# SPI_Test.net
KiCad netlist of a schematic drawn in EAGLE
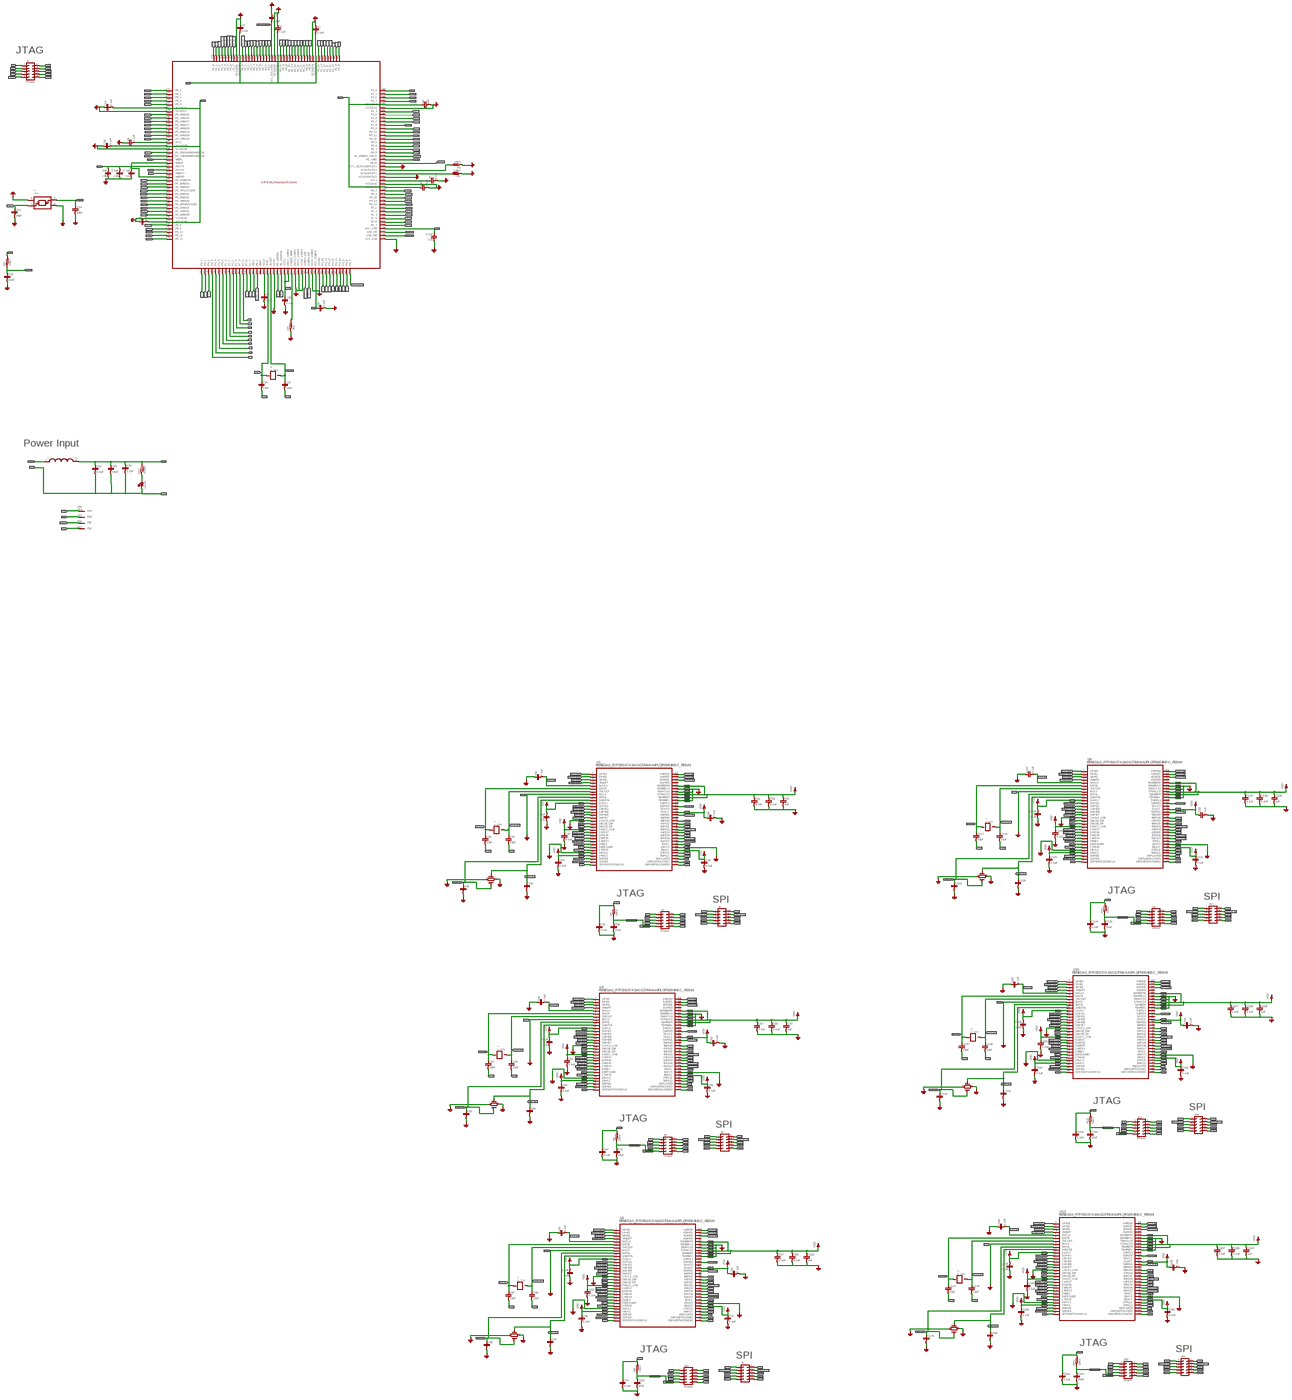
[diagram p0: schematic, sheet 1, overview]
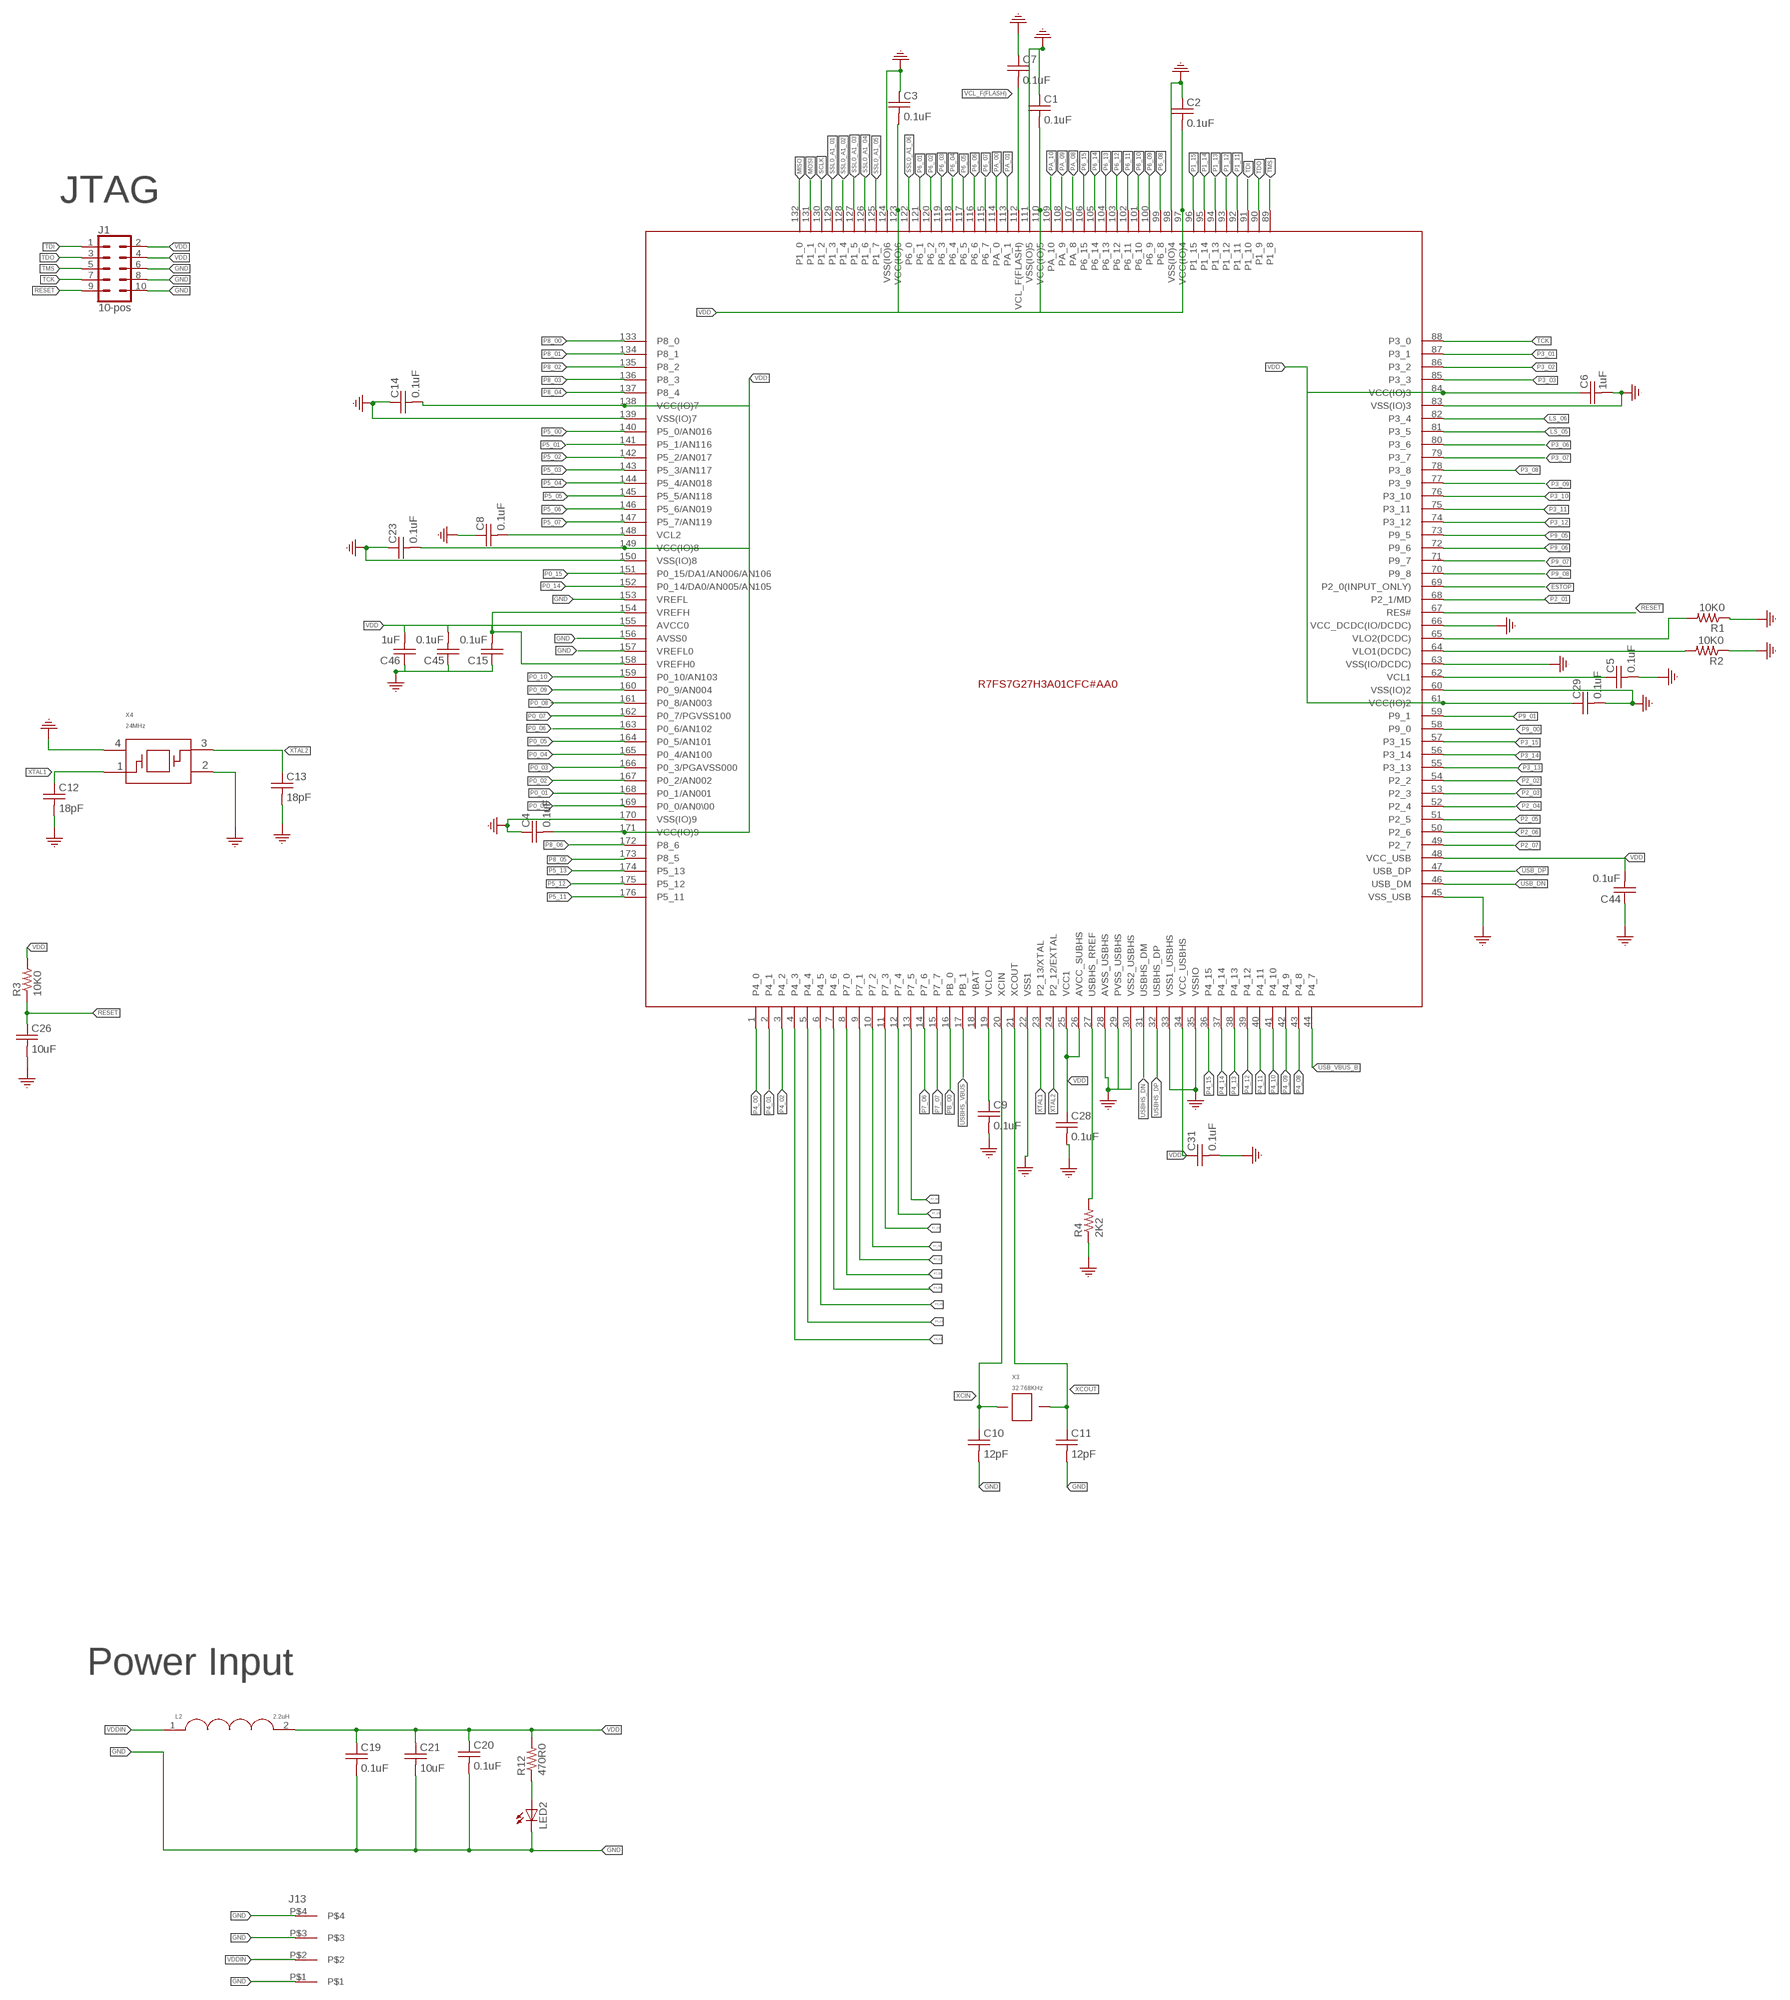
[diagram p1: schematic, sheet 1, part 1 of 5]
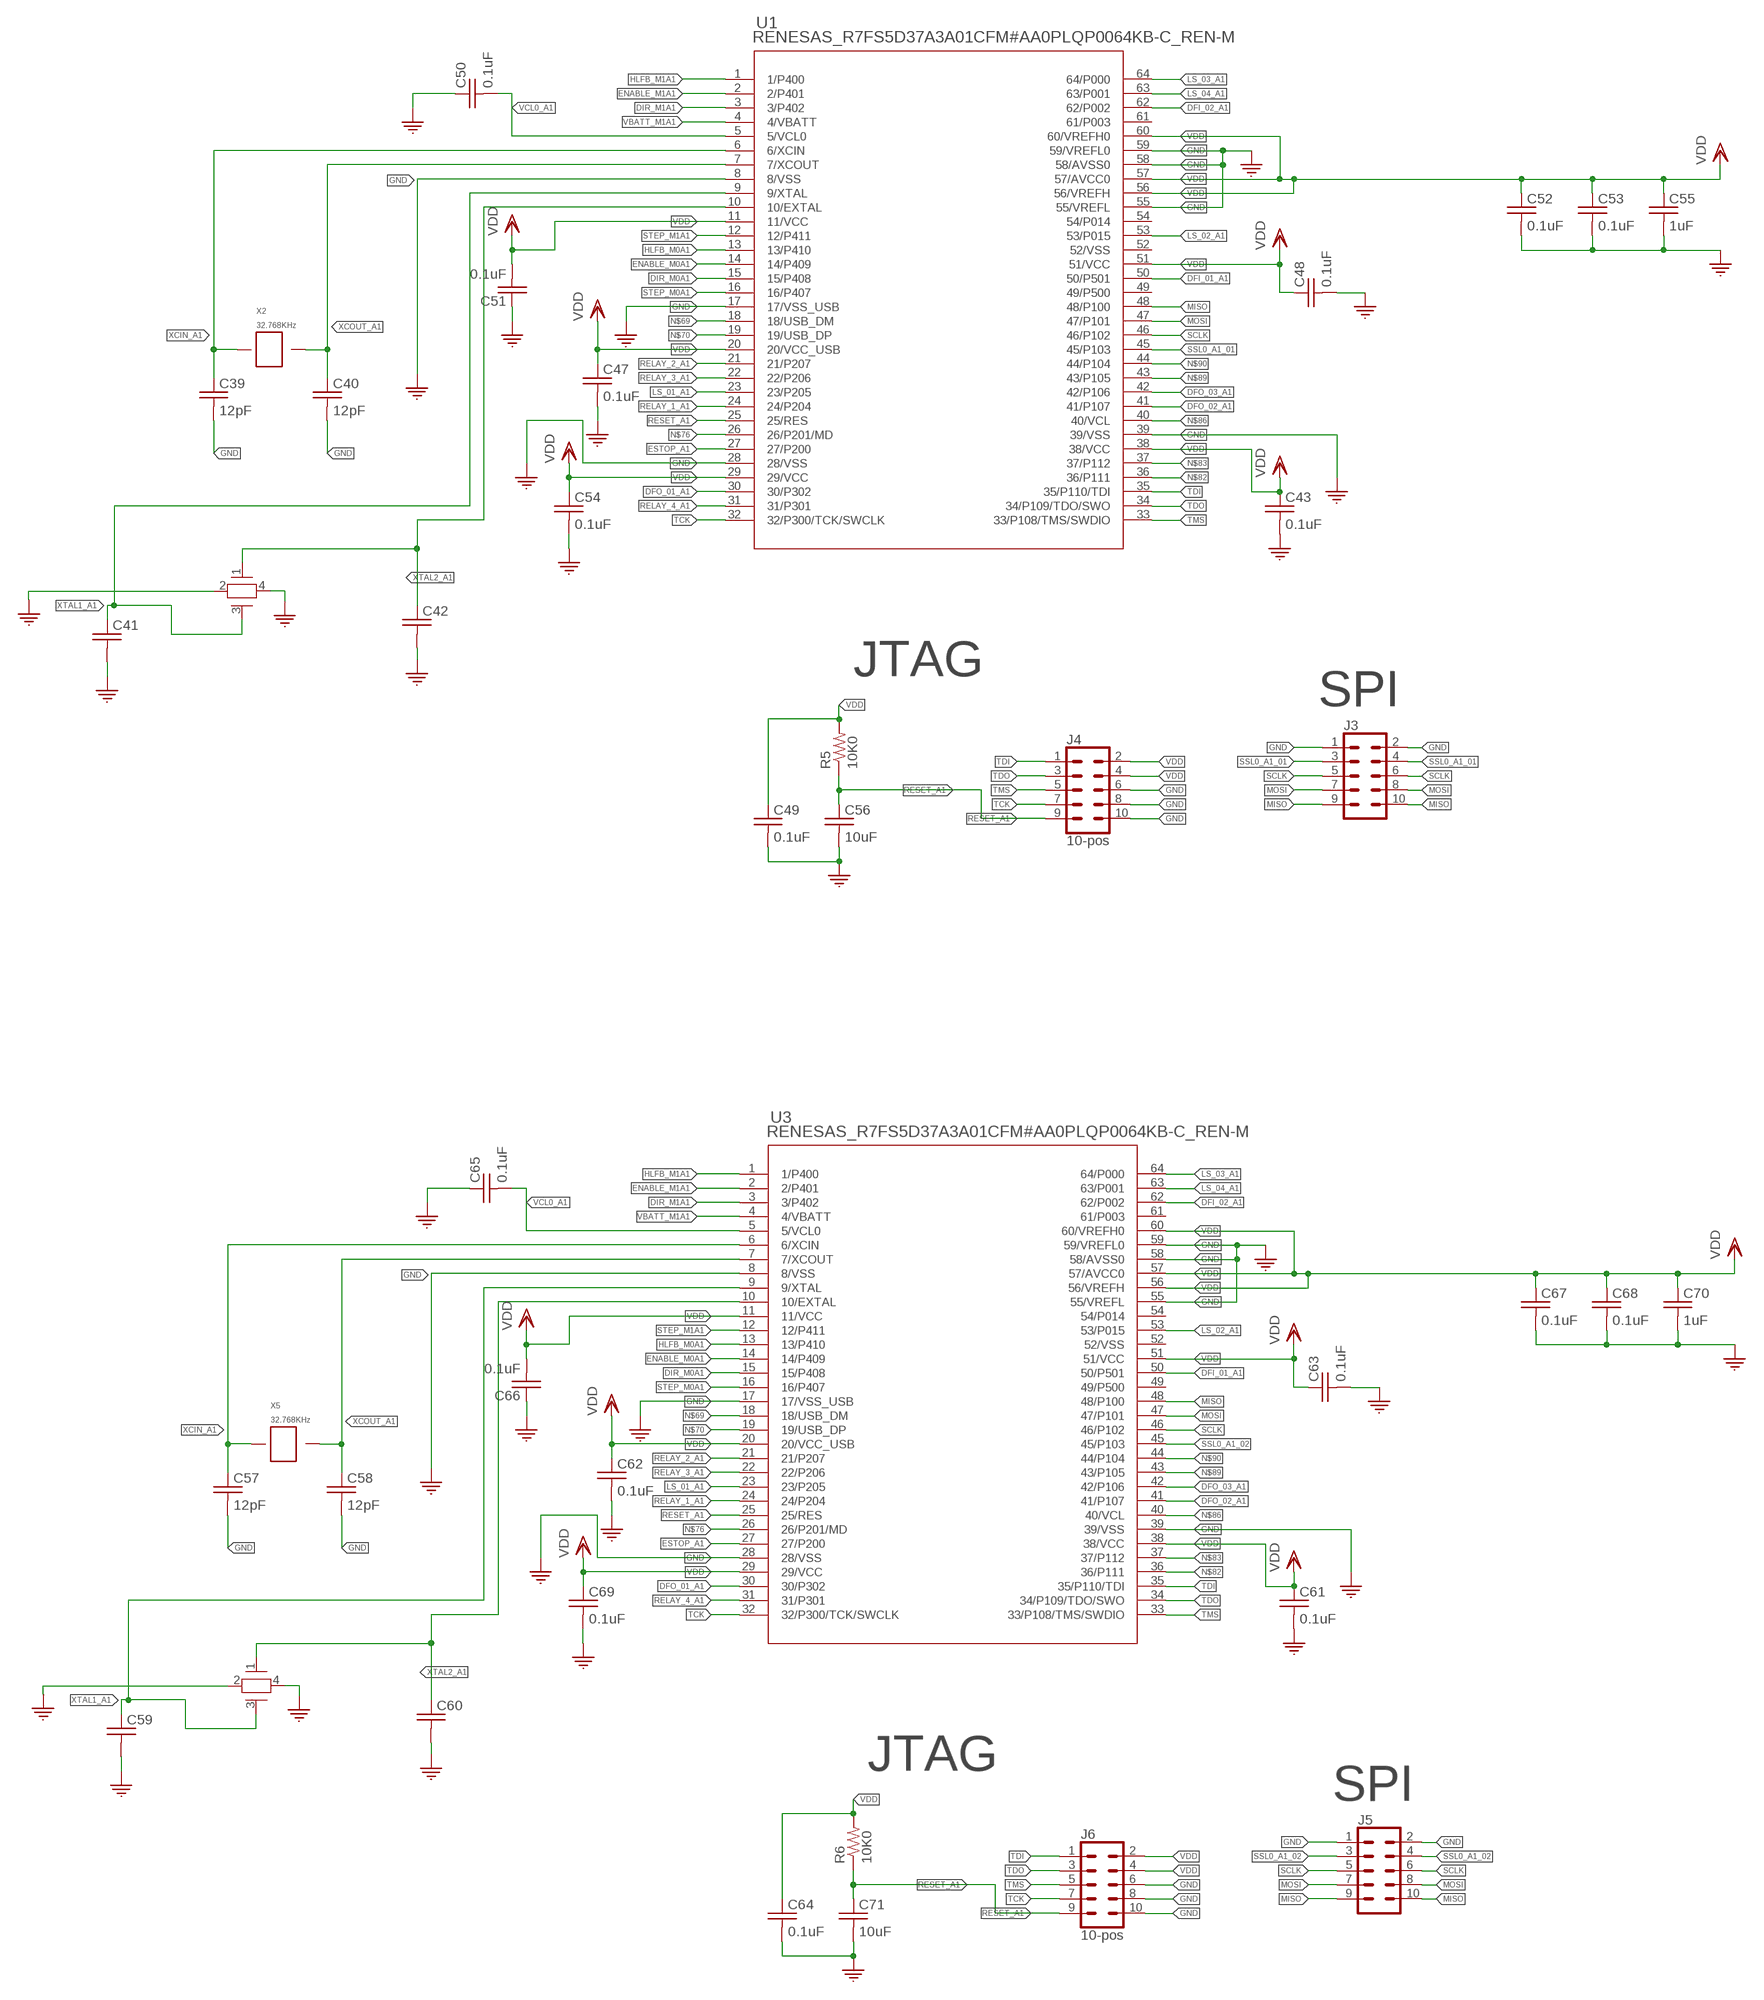
[diagram p2: schematic, sheet 1, part 2 of 5]
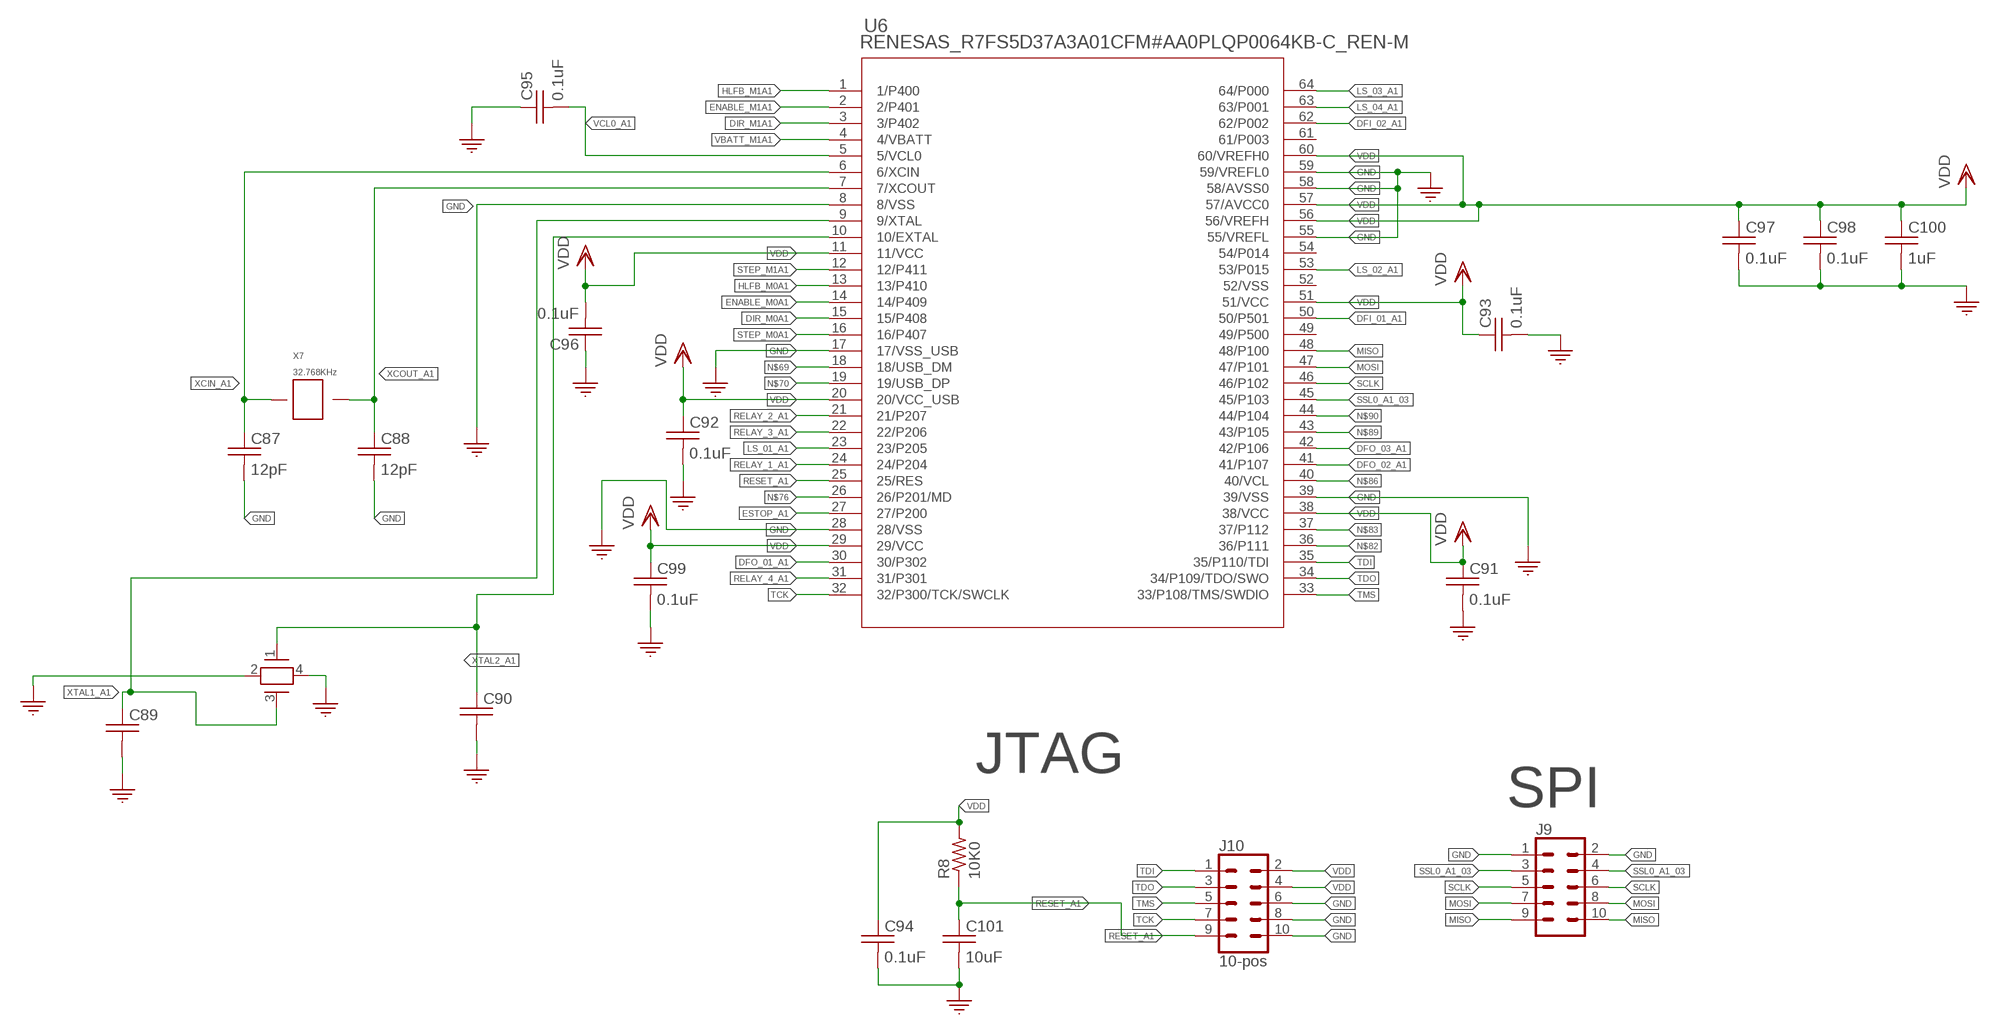
[diagram p3: schematic, sheet 1, part 3 of 5]
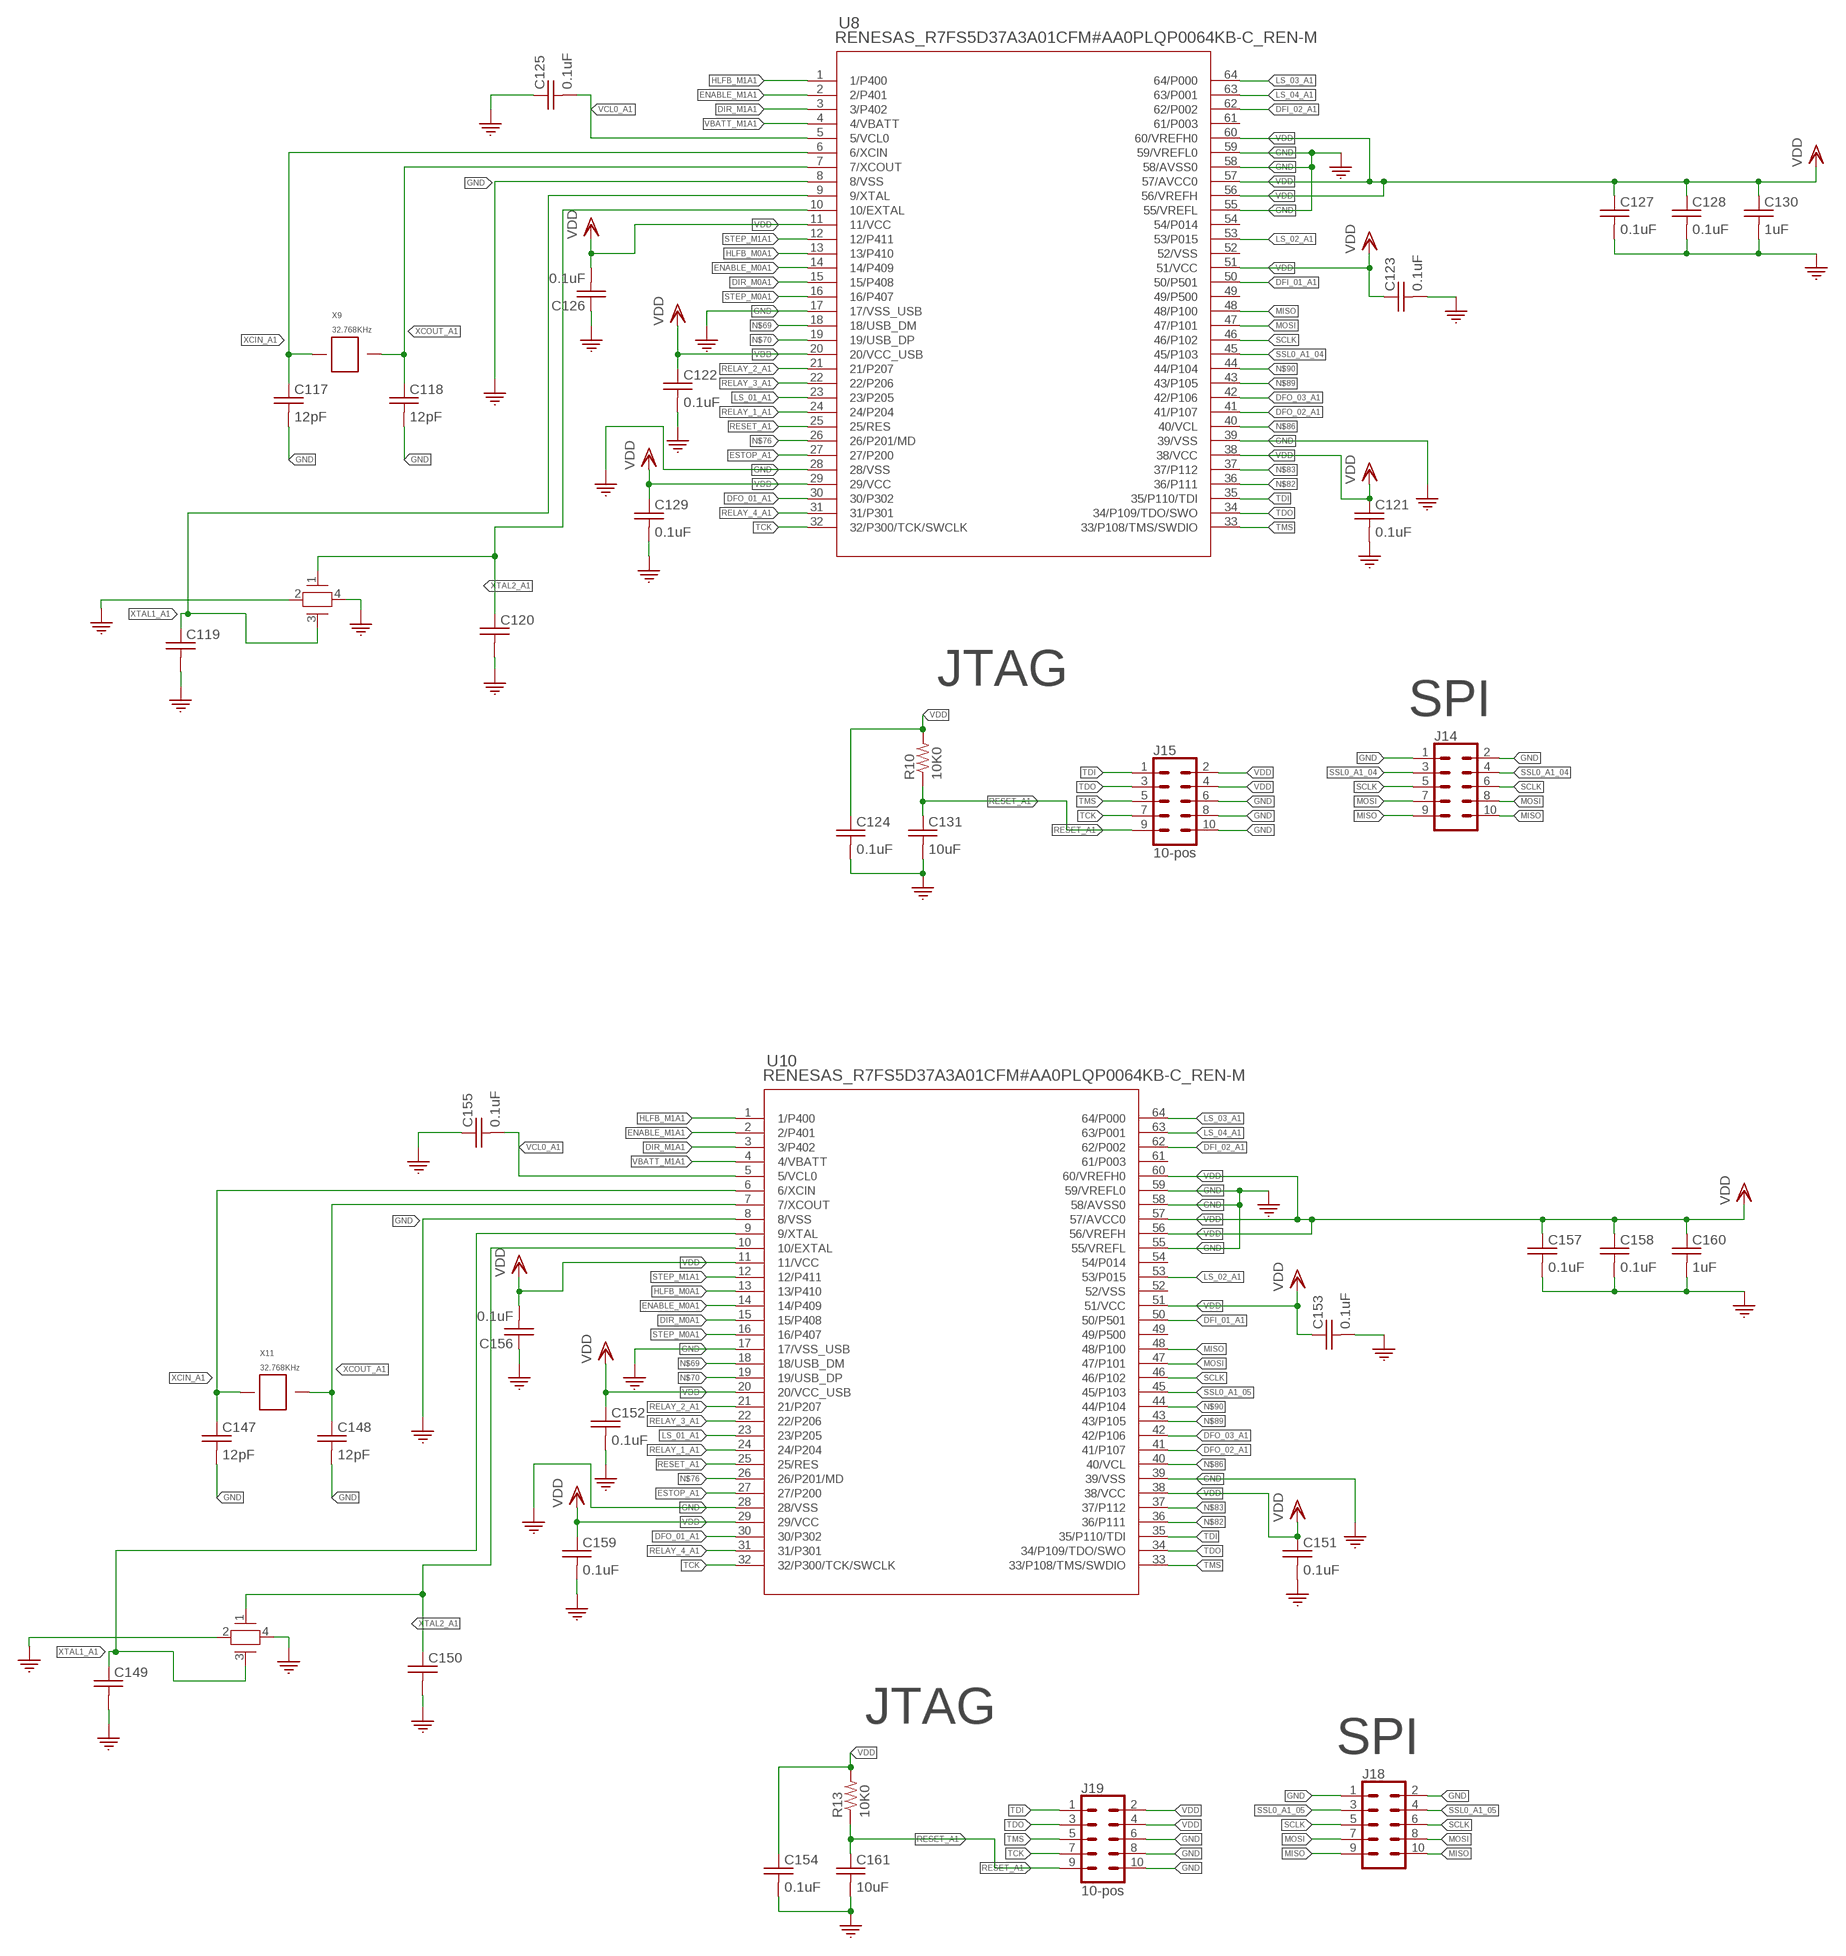
[diagram p4: schematic, sheet 1, part 4 of 5]
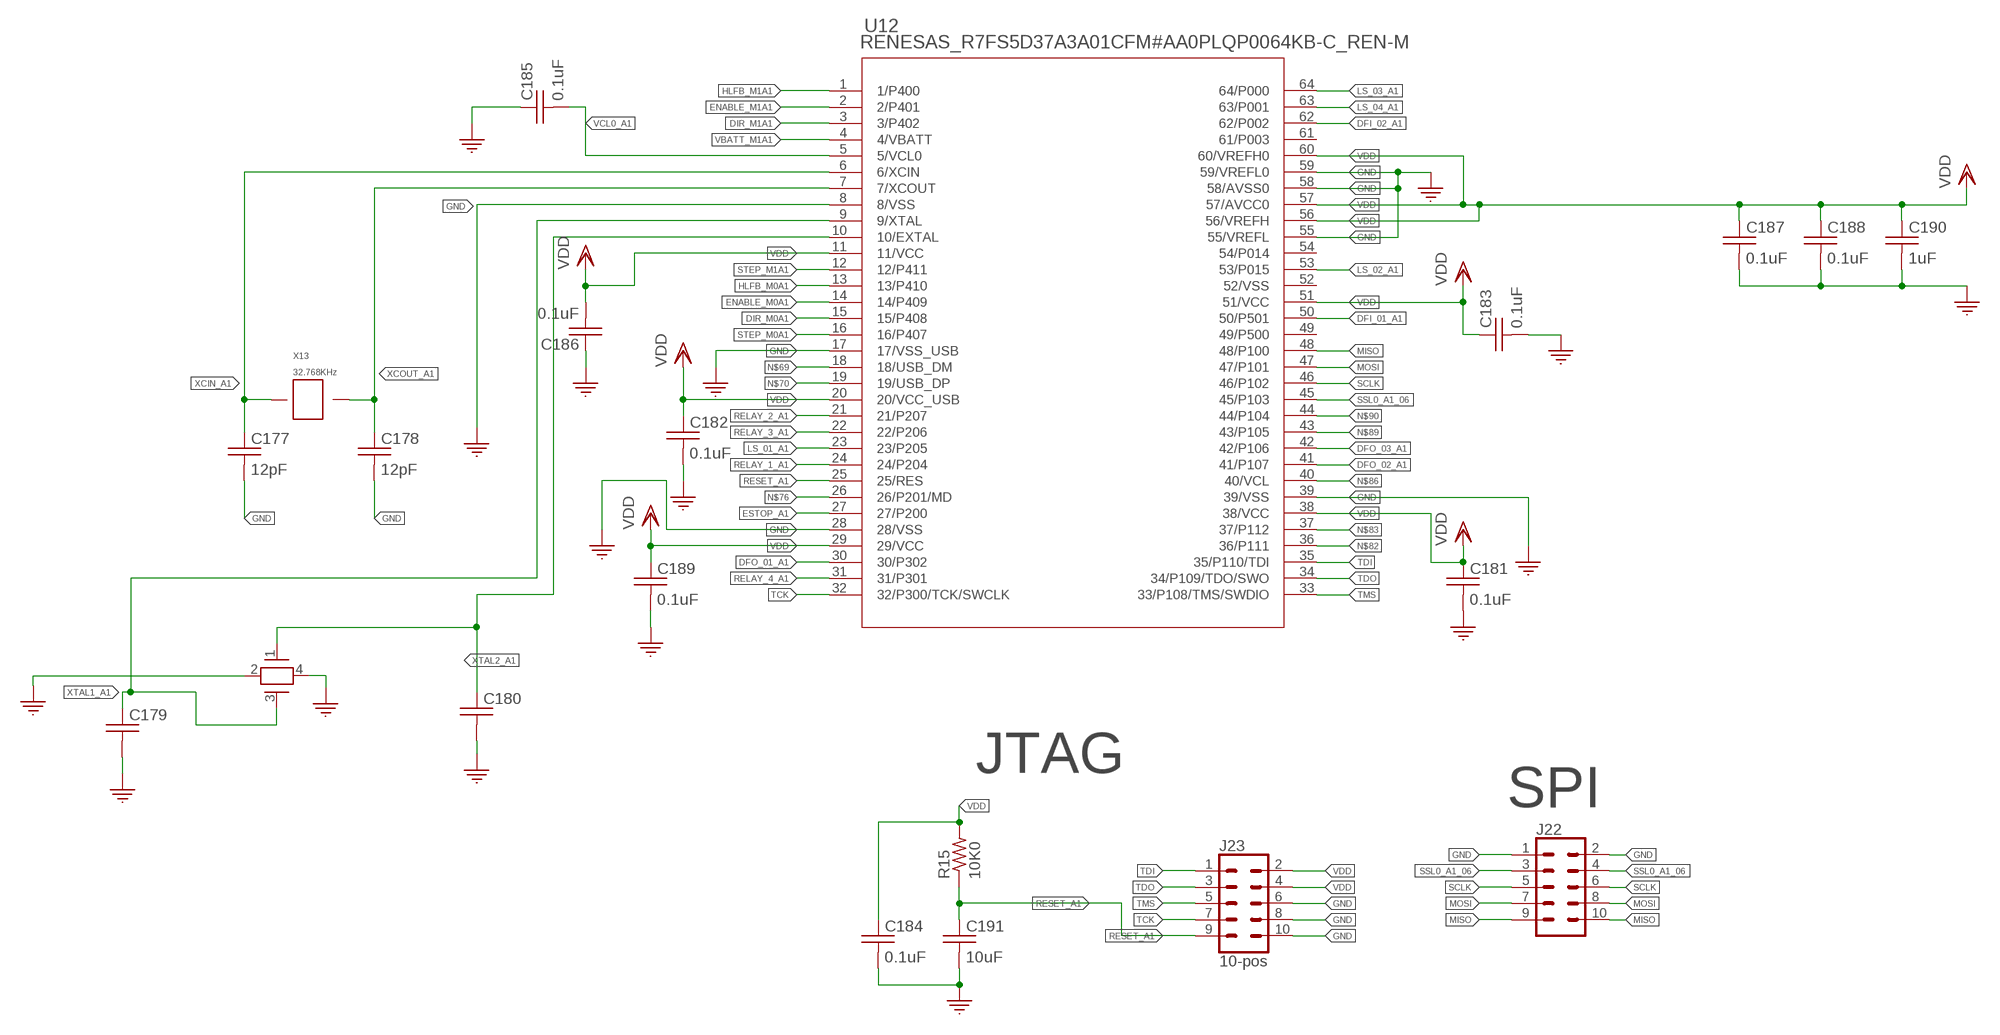
[diagram p5: schematic, sheet 1, part 5 of 5]

(export (version "E")
  (design (tool "Eeschema 10.0.6"))
  (components
    (comp (ref "C1")
      (value "0.1uF")
      (footprint "eagle-import:0402")
      (fields (field (name "PARTNO") "CL05F104ZO5NNNC"))
      (libsource (lib "eagle-import") (part "C_0402_0.1UF"))
    )
    (comp (ref "C2")
      (value "0.1uF")
      (footprint "eagle-import:0402")
      (fields (field (name "PARTNO") "CL05F104ZO5NNNC"))
      (libsource (lib "eagle-import") (part "C_0402_0.1UF"))
    )
    (comp (ref "C3")
      (value "0.1uF")
      (footprint "eagle-import:0402")
      (fields (field (name "PARTNO") "CL05F104ZO5NNNC"))
      (libsource (lib "eagle-import") (part "C_0402_0.1UF"))
    )
    (comp (ref "C4")
      (value "0.1uF")
      (footprint "eagle-import:0402")
      (fields (field (name "PARTNO") "CL05F104ZO5NNNC"))
      (libsource (lib "eagle-import") (part "C_0402_0.1UF"))
    )
    (comp (ref "C5")
      (value "0.1uF")
      (footprint "eagle-import:0402")
      (fields (field (name "PARTNO") "CL05F104ZO5NNNC"))
      (libsource (lib "eagle-import") (part "C_0402_0.1UF"))
    )
    (comp (ref "C6")
      (value "1uF")
      (footprint "eagle-import:0402")
      (fields (field (name "PARTNO") "CL05A105KO5NNNC"))
      (libsource (lib "eagle-import") (part "C_0402_1UF"))
    )
    (comp (ref "C7")
      (value "0.1uF")
      (footprint "eagle-import:0402")
      (fields (field (name "PARTNO") "CL05F104ZO5NNNC"))
      (libsource (lib "eagle-import") (part "C_0402_0.1UF"))
    )
    (comp (ref "C8")
      (value "0.1uF")
      (footprint "eagle-import:0402")
      (fields (field (name "PARTNO") "CL05F104ZO5NNNC"))
      (libsource (lib "eagle-import") (part "C_0402_0.1UF"))
    )
    (comp (ref "C9")
      (value "0.1uF")
      (footprint "eagle-import:0402")
      (fields (field (name "PARTNO") "CL05F104ZO5NNNC"))
      (libsource (lib "eagle-import") (part "C_0402_0.1UF"))
    )
    (comp (ref "C10")
      (value "12pF")
      (footprint "eagle-import:0402")
      (fields (field (name "PARTNO") "CL05C120JB5NNNC"))
      (libsource (lib "eagle-import") (part "C_0402_12PF"))
    )
    (comp (ref "C11")
      (value "12pF")
      (footprint "eagle-import:0402")
      (fields (field (name "PARTNO") "CL05C120JB5NNNC"))
      (libsource (lib "eagle-import") (part "C_0402_12PF"))
    )
    (comp (ref "C12")
      (value "18pF")
      (footprint "eagle-import:0402")
      (fields (field (name "PARTNO") "UMK105CG180JV-F"))
      (libsource (lib "eagle-import") (part "C_0402_18PF"))
    )
    (comp (ref "C13")
      (value "18pF")
      (footprint "eagle-import:0402")
      (fields (field (name "PARTNO") "UMK105CG180JV-F"))
      (libsource (lib "eagle-import") (part "C_0402_18PF"))
    )
    (comp (ref "C14")
      (value "0.1uF")
      (footprint "eagle-import:0402")
      (fields (field (name "PARTNO") "CL05F104ZO5NNNC"))
      (libsource (lib "eagle-import") (part "C_0402_0.1UF"))
    )
    (comp (ref "C15")
      (value "0.1uF")
      (footprint "eagle-import:0402")
      (fields (field (name "PARTNO") "CL05F104ZO5NNNC"))
      (libsource (lib "eagle-import") (part "C_0402_0.1UF"))
    )
    (comp (ref "C19")
      (value "0.1uF")
      (footprint "eagle-import:0402")
      (fields (field (name "PARTNO") "CL05F104ZO5NNNC"))
      (libsource (lib "eagle-import") (part "C_0402_0.1UF"))
    )
    (comp (ref "C20")
      (value "0.1uF")
      (footprint "eagle-import:0402")
      (fields (field (name "PARTNO") "CL05F104ZO5NNNC"))
      (libsource (lib "eagle-import") (part "C_0402_0.1UF"))
    )
    (comp (ref "C21")
      (value "10uF")
      (footprint "eagle-import:0402")
      (fields (field (name "PARTNO") "CL05A106MP8NUB8"))
      (libsource (lib "eagle-import") (part "C_0402_10UF"))
    )
    (comp (ref "C23")
      (value "0.1uF")
      (footprint "eagle-import:0402")
      (fields (field (name "PARTNO") "CL05F104ZO5NNNC"))
      (libsource (lib "eagle-import") (part "C_0402_0.1UF"))
    )
    (comp (ref "C26")
      (value "10uF")
      (footprint "eagle-import:0402")
      (fields (field (name "PARTNO") "CL05A106MP8NUB8"))
      (libsource (lib "eagle-import") (part "C_0402_10UF"))
    )
    (comp (ref "C28")
      (value "0.1uF")
      (footprint "eagle-import:0402")
      (fields (field (name "PARTNO") "CL05F104ZO5NNNC"))
      (libsource (lib "eagle-import") (part "C_0402_0.1UF"))
    )
    (comp (ref "C29")
      (value "0.1uF")
      (footprint "eagle-import:0402")
      (fields (field (name "PARTNO") "CL05F104ZO5NNNC"))
      (libsource (lib "eagle-import") (part "C_0402_0.1UF"))
    )
    (comp (ref "C31")
      (value "0.1uF")
      (footprint "eagle-import:0402")
      (fields (field (name "PARTNO") "CL05F104ZO5NNNC"))
      (libsource (lib "eagle-import") (part "C_0402_0.1UF"))
    )
    (comp (ref "C39")
      (value "12pF")
      (footprint "eagle-import:0402")
      (fields (field (name "PARTNO") "CL05C120JB5NNNC"))
      (libsource (lib "eagle-import") (part "C_0402_12PF"))
    )
    (comp (ref "C40")
      (value "12pF")
      (footprint "eagle-import:0402")
      (fields (field (name "PARTNO") "CL05C120JB5NNNC"))
      (libsource (lib "eagle-import") (part "C_0402_12PF"))
    )
    (comp (ref "C41")
      (value "10pF")
      (footprint "eagle-import:0402")
      (fields (field (name "PARTNO") "CC0402JRNPO9BN100"))
      (libsource (lib "eagle-import") (part "C_0402_10PF"))
    )
    (comp (ref "C42")
      (value "10pF")
      (footprint "eagle-import:0402")
      (fields (field (name "PARTNO") "CC0402JRNPO9BN100"))
      (libsource (lib "eagle-import") (part "C_0402_10PF"))
    )
    (comp (ref "C43")
      (value "0.1uF")
      (footprint "eagle-import:0402")
      (fields (field (name "PARTNO") "CL05F104ZO5NNNC"))
      (libsource (lib "eagle-import") (part "C_0402_0.1UF"))
    )
    (comp (ref "C44")
      (value "0.1uF")
      (footprint "eagle-import:0402")
      (fields (field (name "PARTNO") "CL05F104ZO5NNNC"))
      (libsource (lib "eagle-import") (part "C_0402_0.1UF"))
    )
    (comp (ref "C45")
      (value "0.1uF")
      (footprint "eagle-import:0402")
      (fields (field (name "PARTNO") "CL05F104ZO5NNNC"))
      (libsource (lib "eagle-import") (part "C_0402_0.1UF"))
    )
    (comp (ref "C46")
      (value "1uF")
      (footprint "eagle-import:0402")
      (fields (field (name "PARTNO") "CL05A105KO5NNNC"))
      (libsource (lib "eagle-import") (part "C_0402_1UF"))
    )
    (comp (ref "C47")
      (value "0.1uF")
      (footprint "eagle-import:0402")
      (fields (field (name "PARTNO") "CL05F104ZO5NNNC"))
      (libsource (lib "eagle-import") (part "C_0402_0.1UF"))
    )
    (comp (ref "C48")
      (value "0.1uF")
      (footprint "eagle-import:0402")
      (fields (field (name "PARTNO") "CL05F104ZO5NNNC"))
      (libsource (lib "eagle-import") (part "C_0402_0.1UF"))
    )
    (comp (ref "C49")
      (value "0.1uF")
      (footprint "eagle-import:0402")
      (fields (field (name "PARTNO") "CL05F104ZO5NNNC"))
      (libsource (lib "eagle-import") (part "C_0402_0.1UF"))
    )
    (comp (ref "C50")
      (value "0.1uF")
      (footprint "eagle-import:0402")
      (fields (field (name "PARTNO") "CL05F104ZO5NNNC"))
      (libsource (lib "eagle-import") (part "C_0402_0.1UF"))
    )
    (comp (ref "C51")
      (value "0.1uF")
      (footprint "eagle-import:0402")
      (fields (field (name "PARTNO") "CL05F104ZO5NNNC"))
      (libsource (lib "eagle-import") (part "C_0402_0.1UF"))
    )
    (comp (ref "C52")
      (value "0.1uF")
      (footprint "eagle-import:0402")
      (fields (field (name "PARTNO") "CL05F104ZO5NNNC"))
      (libsource (lib "eagle-import") (part "C_0402_0.1UF"))
    )
    (comp (ref "C53")
      (value "0.1uF")
      (footprint "eagle-import:0402")
      (fields (field (name "PARTNO") "CL05F104ZO5NNNC"))
      (libsource (lib "eagle-import") (part "C_0402_0.1UF"))
    )
    (comp (ref "C54")
      (value "0.1uF")
      (footprint "eagle-import:0402")
      (fields (field (name "PARTNO") "CL05F104ZO5NNNC"))
      (libsource (lib "eagle-import") (part "C_0402_0.1UF"))
    )
    (comp (ref "C55")
      (value "1uF")
      (footprint "eagle-import:0402")
      (fields (field (name "PARTNO") "CL05A105KO5NNNC"))
      (libsource (lib "eagle-import") (part "C_0402_1UF"))
    )
    (comp (ref "C56")
      (value "10uF")
      (footprint "eagle-import:0402")
      (fields (field (name "PARTNO") "CL05A106MP8NUB8"))
      (libsource (lib "eagle-import") (part "C_0402_10UF"))
    )
    (comp (ref "C57")
      (value "12pF")
      (footprint "eagle-import:0402")
      (fields (field (name "PARTNO") "CL05C120JB5NNNC"))
      (libsource (lib "eagle-import") (part "C_0402_12PF"))
    )
    (comp (ref "C58")
      (value "12pF")
      (footprint "eagle-import:0402")
      (fields (field (name "PARTNO") "CL05C120JB5NNNC"))
      (libsource (lib "eagle-import") (part "C_0402_12PF"))
    )
    (comp (ref "C59")
      (value "10pF")
      (footprint "eagle-import:0402")
      (fields (field (name "PARTNO") "CC0402JRNPO9BN100"))
      (libsource (lib "eagle-import") (part "C_0402_10PF"))
    )
    (comp (ref "C60")
      (value "10pF")
      (footprint "eagle-import:0402")
      (fields (field (name "PARTNO") "CC0402JRNPO9BN100"))
      (libsource (lib "eagle-import") (part "C_0402_10PF"))
    )
    (comp (ref "C61")
      (value "0.1uF")
      (footprint "eagle-import:0402")
      (fields (field (name "PARTNO") "CL05F104ZO5NNNC"))
      (libsource (lib "eagle-import") (part "C_0402_0.1UF"))
    )
    (comp (ref "C62")
      (value "0.1uF")
      (footprint "eagle-import:0402")
      (fields (field (name "PARTNO") "CL05F104ZO5NNNC"))
      (libsource (lib "eagle-import") (part "C_0402_0.1UF"))
    )
    (comp (ref "C63")
      (value "0.1uF")
      (footprint "eagle-import:0402")
      (fields (field (name "PARTNO") "CL05F104ZO5NNNC"))
      (libsource (lib "eagle-import") (part "C_0402_0.1UF"))
    )
    (comp (ref "C64")
      (value "0.1uF")
      (footprint "eagle-import:0402")
      (fields (field (name "PARTNO") "CL05F104ZO5NNNC"))
      (libsource (lib "eagle-import") (part "C_0402_0.1UF"))
    )
    (comp (ref "C65")
      (value "0.1uF")
      (footprint "eagle-import:0402")
      (fields (field (name "PARTNO") "CL05F104ZO5NNNC"))
      (libsource (lib "eagle-import") (part "C_0402_0.1UF"))
    )
    (comp (ref "C66")
      (value "0.1uF")
      (footprint "eagle-import:0402")
      (fields (field (name "PARTNO") "CL05F104ZO5NNNC"))
      (libsource (lib "eagle-import") (part "C_0402_0.1UF"))
    )
    (comp (ref "C67")
      (value "0.1uF")
      (footprint "eagle-import:0402")
      (fields (field (name "PARTNO") "CL05F104ZO5NNNC"))
      (libsource (lib "eagle-import") (part "C_0402_0.1UF"))
    )
    (comp (ref "C68")
      (value "0.1uF")
      (footprint "eagle-import:0402")
      (fields (field (name "PARTNO") "CL05F104ZO5NNNC"))
      (libsource (lib "eagle-import") (part "C_0402_0.1UF"))
    )
    (comp (ref "C69")
      (value "0.1uF")
      (footprint "eagle-import:0402")
      (fields (field (name "PARTNO") "CL05F104ZO5NNNC"))
      (libsource (lib "eagle-import") (part "C_0402_0.1UF"))
    )
    (comp (ref "C70")
      (value "1uF")
      (footprint "eagle-import:0402")
      (fields (field (name "PARTNO") "CL05A105KO5NNNC"))
      (libsource (lib "eagle-import") (part "C_0402_1UF"))
    )
    (comp (ref "C71")
      (value "10uF")
      (footprint "eagle-import:0402")
      (fields (field (name "PARTNO") "CL05A106MP8NUB8"))
      (libsource (lib "eagle-import") (part "C_0402_10UF"))
    )
    (comp (ref "C87")
      (value "12pF")
      (footprint "eagle-import:0402")
      (fields (field (name "PARTNO") "CL05C120JB5NNNC"))
      (libsource (lib "eagle-import") (part "C_0402_12PF"))
    )
    (comp (ref "C88")
      (value "12pF")
      (footprint "eagle-import:0402")
      (fields (field (name "PARTNO") "CL05C120JB5NNNC"))
      (libsource (lib "eagle-import") (part "C_0402_12PF"))
    )
    (comp (ref "C89")
      (value "10pF")
      (footprint "eagle-import:0402")
      (fields (field (name "PARTNO") "CC0402JRNPO9BN100"))
      (libsource (lib "eagle-import") (part "C_0402_10PF"))
    )
    (comp (ref "C90")
      (value "10pF")
      (footprint "eagle-import:0402")
      (fields (field (name "PARTNO") "CC0402JRNPO9BN100"))
      (libsource (lib "eagle-import") (part "C_0402_10PF"))
    )
    (comp (ref "C91")
      (value "0.1uF")
      (footprint "eagle-import:0402")
      (fields (field (name "PARTNO") "CL05F104ZO5NNNC"))
      (libsource (lib "eagle-import") (part "C_0402_0.1UF"))
    )
    (comp (ref "C92")
      (value "0.1uF")
      (footprint "eagle-import:0402")
      (fields (field (name "PARTNO") "CL05F104ZO5NNNC"))
      (libsource (lib "eagle-import") (part "C_0402_0.1UF"))
    )
    (comp (ref "C93")
      (value "0.1uF")
      (footprint "eagle-import:0402")
      (fields (field (name "PARTNO") "CL05F104ZO5NNNC"))
      (libsource (lib "eagle-import") (part "C_0402_0.1UF"))
    )
    (comp (ref "C94")
      (value "0.1uF")
      (footprint "eagle-import:0402")
      (fields (field (name "PARTNO") "CL05F104ZO5NNNC"))
      (libsource (lib "eagle-import") (part "C_0402_0.1UF"))
    )
    (comp (ref "C95")
      (value "0.1uF")
      (footprint "eagle-import:0402")
      (fields (field (name "PARTNO") "CL05F104ZO5NNNC"))
      (libsource (lib "eagle-import") (part "C_0402_0.1UF"))
    )
    (comp (ref "C96")
      (value "0.1uF")
      (footprint "eagle-import:0402")
      (fields (field (name "PARTNO") "CL05F104ZO5NNNC"))
      (libsource (lib "eagle-import") (part "C_0402_0.1UF"))
    )
    (comp (ref "C97")
      (value "0.1uF")
      (footprint "eagle-import:0402")
      (fields (field (name "PARTNO") "CL05F104ZO5NNNC"))
      (libsource (lib "eagle-import") (part "C_0402_0.1UF"))
    )
    (comp (ref "C98")
      (value "0.1uF")
      (footprint "eagle-import:0402")
      (fields (field (name "PARTNO") "CL05F104ZO5NNNC"))
      (libsource (lib "eagle-import") (part "C_0402_0.1UF"))
    )
    (comp (ref "C99")
      (value "0.1uF")
      (footprint "eagle-import:0402")
      (fields (field (name "PARTNO") "CL05F104ZO5NNNC"))
      (libsource (lib "eagle-import") (part "C_0402_0.1UF"))
    )
    (comp (ref "C100")
      (value "1uF")
      (footprint "eagle-import:0402")
      (fields (field (name "PARTNO") "CL05A105KO5NNNC"))
      (libsource (lib "eagle-import") (part "C_0402_1UF"))
    )
    (comp (ref "C101")
      (value "10uF")
      (footprint "eagle-import:0402")
      (fields (field (name "PARTNO") "CL05A106MP8NUB8"))
      (libsource (lib "eagle-import") (part "C_0402_10UF"))
    )
    (comp (ref "C117")
      (value "12pF")
      (footprint "eagle-import:0402")
      (fields (field (name "PARTNO") "CL05C120JB5NNNC"))
      (libsource (lib "eagle-import") (part "C_0402_12PF"))
    )
    (comp (ref "C118")
      (value "12pF")
      (footprint "eagle-import:0402")
      (fields (field (name "PARTNO") "CL05C120JB5NNNC"))
      (libsource (lib "eagle-import") (part "C_0402_12PF"))
    )
    (comp (ref "C119")
      (value "10pF")
      (footprint "eagle-import:0402")
      (fields (field (name "PARTNO") "CC0402JRNPO9BN100"))
      (libsource (lib "eagle-import") (part "C_0402_10PF"))
    )
    (comp (ref "C120")
      (value "10pF")
      (footprint "eagle-import:0402")
      (fields (field (name "PARTNO") "CC0402JRNPO9BN100"))
      (libsource (lib "eagle-import") (part "C_0402_10PF"))
    )
    (comp (ref "C121")
      (value "0.1uF")
      (footprint "eagle-import:0402")
      (fields (field (name "PARTNO") "CL05F104ZO5NNNC"))
      (libsource (lib "eagle-import") (part "C_0402_0.1UF"))
    )
    (comp (ref "C122")
      (value "0.1uF")
      (footprint "eagle-import:0402")
      (fields (field (name "PARTNO") "CL05F104ZO5NNNC"))
      (libsource (lib "eagle-import") (part "C_0402_0.1UF"))
    )
    (comp (ref "C123")
      (value "0.1uF")
      (footprint "eagle-import:0402")
      (fields (field (name "PARTNO") "CL05F104ZO5NNNC"))
      (libsource (lib "eagle-import") (part "C_0402_0.1UF"))
    )
    (comp (ref "C124")
      (value "0.1uF")
      (footprint "eagle-import:0402")
      (fields (field (name "PARTNO") "CL05F104ZO5NNNC"))
      (libsource (lib "eagle-import") (part "C_0402_0.1UF"))
    )
    (comp (ref "C125")
      (value "0.1uF")
      (footprint "eagle-import:0402")
      (fields (field (name "PARTNO") "CL05F104ZO5NNNC"))
      (libsource (lib "eagle-import") (part "C_0402_0.1UF"))
    )
    (comp (ref "C126")
      (value "0.1uF")
      (footprint "eagle-import:0402")
      (fields (field (name "PARTNO") "CL05F104ZO5NNNC"))
      (libsource (lib "eagle-import") (part "C_0402_0.1UF"))
    )
    (comp (ref "C127")
      (value "0.1uF")
      (footprint "eagle-import:0402")
      (fields (field (name "PARTNO") "CL05F104ZO5NNNC"))
      (libsource (lib "eagle-import") (part "C_0402_0.1UF"))
    )
    (comp (ref "C128")
      (value "0.1uF")
      (footprint "eagle-import:0402")
      (fields (field (name "PARTNO") "CL05F104ZO5NNNC"))
      (libsource (lib "eagle-import") (part "C_0402_0.1UF"))
    )
    (comp (ref "C129")
      (value "0.1uF")
      (footprint "eagle-import:0402")
      (fields (field (name "PARTNO") "CL05F104ZO5NNNC"))
      (libsource (lib "eagle-import") (part "C_0402_0.1UF"))
    )
    (comp (ref "C130")
      (value "1uF")
      (footprint "eagle-import:0402")
      (fields (field (name "PARTNO") "CL05A105KO5NNNC"))
      (libsource (lib "eagle-import") (part "C_0402_1UF"))
    )
    (comp (ref "C131")
      (value "10uF")
      (footprint "eagle-import:0402")
      (fields (field (name "PARTNO") "CL05A106MP8NUB8"))
      (libsource (lib "eagle-import") (part "C_0402_10UF"))
    )
    (comp (ref "C147")
      (value "12pF")
      (footprint "eagle-import:0402")
      (fields (field (name "PARTNO") "CL05C120JB5NNNC"))
      (libsource (lib "eagle-import") (part "C_0402_12PF"))
    )
    (comp (ref "C148")
      (value "12pF")
      (footprint "eagle-import:0402")
      (fields (field (name "PARTNO") "CL05C120JB5NNNC"))
      (libsource (lib "eagle-import") (part "C_0402_12PF"))
    )
    (comp (ref "C149")
      (value "10pF")
      (footprint "eagle-import:0402")
      (fields (field (name "PARTNO") "CC0402JRNPO9BN100"))
      (libsource (lib "eagle-import") (part "C_0402_10PF"))
    )
    (comp (ref "C150")
      (value "10pF")
      (footprint "eagle-import:0402")
      (fields (field (name "PARTNO") "CC0402JRNPO9BN100"))
      (libsource (lib "eagle-import") (part "C_0402_10PF"))
    )
    (comp (ref "C151")
      (value "0.1uF")
      (footprint "eagle-import:0402")
      (fields (field (name "PARTNO") "CL05F104ZO5NNNC"))
      (libsource (lib "eagle-import") (part "C_0402_0.1UF"))
    )
    (comp (ref "C152")
      (value "0.1uF")
      (footprint "eagle-import:0402")
      (fields (field (name "PARTNO") "CL05F104ZO5NNNC"))
      (libsource (lib "eagle-import") (part "C_0402_0.1UF"))
    )
    (comp (ref "C153")
      (value "0.1uF")
      (footprint "eagle-import:0402")
      (fields (field (name "PARTNO") "CL05F104ZO5NNNC"))
      (libsource (lib "eagle-import") (part "C_0402_0.1UF"))
    )
    (comp (ref "C154")
      (value "0.1uF")
      (footprint "eagle-import:0402")
      (fields (field (name "PARTNO") "CL05F104ZO5NNNC"))
      (libsource (lib "eagle-import") (part "C_0402_0.1UF"))
    )
    (comp (ref "C155")
      (value "0.1uF")
      (footprint "eagle-import:0402")
      (fields (field (name "PARTNO") "CL05F104ZO5NNNC"))
      (libsource (lib "eagle-import") (part "C_0402_0.1UF"))
    )
    (comp (ref "C156")
      (value "0.1uF")
      (footprint "eagle-import:0402")
      (fields (field (name "PARTNO") "CL05F104ZO5NNNC"))
      (libsource (lib "eagle-import") (part "C_0402_0.1UF"))
    )
    (comp (ref "C157")
      (value "0.1uF")
      (footprint "eagle-import:0402")
      (fields (field (name "PARTNO") "CL05F104ZO5NNNC"))
      (libsource (lib "eagle-import") (part "C_0402_0.1UF"))
    )
    (comp (ref "C158")
      (value "0.1uF")
      (footprint "eagle-import:0402")
      (fields (field (name "PARTNO") "CL05F104ZO5NNNC"))
      (libsource (lib "eagle-import") (part "C_0402_0.1UF"))
    )
    (comp (ref "C159")
      (value "0.1uF")
      (footprint "eagle-import:0402")
      (fields (field (name "PARTNO") "CL05F104ZO5NNNC"))
      (libsource (lib "eagle-import") (part "C_0402_0.1UF"))
    )
    (comp (ref "C160")
      (value "1uF")
      (footprint "eagle-import:0402")
      (fields (field (name "PARTNO") "CL05A105KO5NNNC"))
      (libsource (lib "eagle-import") (part "C_0402_1UF"))
    )
    (comp (ref "C161")
      (value "10uF")
      (footprint "eagle-import:0402")
      (fields (field (name "PARTNO") "CL05A106MP8NUB8"))
      (libsource (lib "eagle-import") (part "C_0402_10UF"))
    )
    (comp (ref "C177")
      (value "12pF")
      (footprint "eagle-import:0402")
      (fields (field (name "PARTNO") "CL05C120JB5NNNC"))
      (libsource (lib "eagle-import") (part "C_0402_12PF"))
    )
    (comp (ref "C178")
      (value "12pF")
      (footprint "eagle-import:0402")
      (fields (field (name "PARTNO") "CL05C120JB5NNNC"))
      (libsource (lib "eagle-import") (part "C_0402_12PF"))
    )
    (comp (ref "C179")
      (value "10pF")
      (footprint "eagle-import:0402")
      (fields (field (name "PARTNO") "CC0402JRNPO9BN100"))
      (libsource (lib "eagle-import") (part "C_0402_10PF"))
    )
    (comp (ref "C180")
      (value "10pF")
      (footprint "eagle-import:0402")
      (fields (field (name "PARTNO") "CC0402JRNPO9BN100"))
      (libsource (lib "eagle-import") (part "C_0402_10PF"))
    )
    (comp (ref "C181")
      (value "0.1uF")
      (footprint "eagle-import:0402")
      (fields (field (name "PARTNO") "CL05F104ZO5NNNC"))
      (libsource (lib "eagle-import") (part "C_0402_0.1UF"))
    )
    (comp (ref "C182")
      (value "0.1uF")
      (footprint "eagle-import:0402")
      (fields (field (name "PARTNO") "CL05F104ZO5NNNC"))
      (libsource (lib "eagle-import") (part "C_0402_0.1UF"))
    )
    (comp (ref "C183")
      (value "0.1uF")
      (footprint "eagle-import:0402")
      (fields (field (name "PARTNO") "CL05F104ZO5NNNC"))
      (libsource (lib "eagle-import") (part "C_0402_0.1UF"))
    )
    (comp (ref "C184")
      (value "0.1uF")
      (footprint "eagle-import:0402")
      (fields (field (name "PARTNO") "CL05F104ZO5NNNC"))
      (libsource (lib "eagle-import") (part "C_0402_0.1UF"))
    )
    (comp (ref "C185")
      (value "0.1uF")
      (footprint "eagle-import:0402")
      (fields (field (name "PARTNO") "CL05F104ZO5NNNC"))
      (libsource (lib "eagle-import") (part "C_0402_0.1UF"))
    )
    (comp (ref "C186")
      (value "0.1uF")
      (footprint "eagle-import:0402")
      (fields (field (name "PARTNO") "CL05F104ZO5NNNC"))
      (libsource (lib "eagle-import") (part "C_0402_0.1UF"))
    )
    (comp (ref "C187")
      (value "0.1uF")
      (footprint "eagle-import:0402")
      (fields (field (name "PARTNO") "CL05F104ZO5NNNC"))
      (libsource (lib "eagle-import") (part "C_0402_0.1UF"))
    )
    (comp (ref "C188")
      (value "0.1uF")
      (footprint "eagle-import:0402")
      (fields (field (name "PARTNO") "CL05F104ZO5NNNC"))
      (libsource (lib "eagle-import") (part "C_0402_0.1UF"))
    )
    (comp (ref "C189")
      (value "0.1uF")
      (footprint "eagle-import:0402")
      (fields (field (name "PARTNO") "CL05F104ZO5NNNC"))
      (libsource (lib "eagle-import") (part "C_0402_0.1UF"))
    )
    (comp (ref "C190")
      (value "1uF")
      (footprint "eagle-import:0402")
      (fields (field (name "PARTNO") "CL05A105KO5NNNC"))
      (libsource (lib "eagle-import") (part "C_0402_1UF"))
    )
    (comp (ref "C191")
      (value "10uF")
      (footprint "eagle-import:0402")
      (fields (field (name "PARTNO") "CL05A106MP8NUB8"))
      (libsource (lib "eagle-import") (part "C_0402_10UF"))
    )
    (comp (ref "J1")
      (value "10-pos")
      (footprint "eagle-import:2X5")
      (fields (field (name "PARTNO") "PH2RA-10-UA"))
      (libsource (lib "eagle-import") (part "CONN_05X2_RAPTH"))
    )
    (comp (ref "J3")
      (value "CONN_05X2PTH")
      (footprint "eagle-import:2X5")
      (libsource (lib "eagle-import") (part "CONN_05X2PTH"))
    )
    (comp (ref "J4")
      (value "10-pos")
      (footprint "eagle-import:2X5")
      (fields (field (name "PARTNO") "PH2RA-10-UA"))
      (libsource (lib "eagle-import") (part "CONN_05X2_RAPTH"))
    )
    (comp (ref "J5")
      (value "CONN_05X2PTH")
      (footprint "eagle-import:2X5")
      (libsource (lib "eagle-import") (part "CONN_05X2PTH"))
    )
    (comp (ref "J6")
      (value "10-pos")
      (footprint "eagle-import:2X5")
      (fields (field (name "PARTNO") "PH2RA-10-UA"))
      (libsource (lib "eagle-import") (part "CONN_05X2_RAPTH"))
    )
    (comp (ref "J9")
      (value "CONN_05X2PTH")
      (footprint "eagle-import:2X5")
      (libsource (lib "eagle-import") (part "CONN_05X2PTH"))
    )
    (comp (ref "J10")
      (value "10-pos")
      (footprint "eagle-import:2X5")
      (fields (field (name "PARTNO") "PH2RA-10-UA"))
      (libsource (lib "eagle-import") (part "CONN_05X2_RAPTH"))
    )
    (comp (ref "J13")
      (value "4-pos")
      (footprint "eagle-import:1X4_3.81MM_PITCH")
      (fields (field (name "PARTNO") "691322310004"))
      (libsource (lib "eagle-import") (part "3.81MM_1_X_4_RT_ANGLE_PLUG_HEADER"))
    )
    (comp (ref "J14")
      (value "CONN_05X2PTH")
      (footprint "eagle-import:2X5")
      (libsource (lib "eagle-import") (part "CONN_05X2PTH"))
    )
    (comp (ref "J15")
      (value "10-pos")
      (footprint "eagle-import:2X5")
      (fields (field (name "PARTNO") "PH2RA-10-UA"))
      (libsource (lib "eagle-import") (part "CONN_05X2_RAPTH"))
    )
    (comp (ref "J18")
      (value "CONN_05X2PTH")
      (footprint "eagle-import:2X5")
      (libsource (lib "eagle-import") (part "CONN_05X2PTH"))
    )
    (comp (ref "J19")
      (value "10-pos")
      (footprint "eagle-import:2X5")
      (fields (field (name "PARTNO") "PH2RA-10-UA"))
      (libsource (lib "eagle-import") (part "CONN_05X2_RAPTH"))
    )
    (comp (ref "J22")
      (value "CONN_05X2PTH")
      (footprint "eagle-import:2X5")
      (libsource (lib "eagle-import") (part "CONN_05X2PTH"))
    )
    (comp (ref "J23")
      (value "10-pos")
      (footprint "eagle-import:2X5")
      (fields (field (name "PARTNO") "PH2RA-10-UA"))
      (libsource (lib "eagle-import") (part "CONN_05X2_RAPTH"))
    )
    (comp (ref "L2")
      (value "2.2uH")
      (footprint "eagle-import:1008")
      (fields (field (name "PARTNO") "LQM2HPN2R2MG0L"))
      (libsource (lib "eagle-import") (part "INDUCTOR_1008_2.2_MH_1.3A"))
    )
    (comp (ref "LED2")
      (value "Green")
      (footprint "eagle-import:0805")
      (fields (field (name "PARTNO") "LG R971-KN-1"))
      (libsource (lib "eagle-import") (part "LED_0805_GREEN"))
    )
    (comp (ref "R1")
      (value "10K0")
      (footprint "eagle-import:0402")
      (fields (field (name "PARTNO") "RMCF0402JT10K0"))
      (libsource (lib "eagle-import") (part "R_0402_10K0"))
    )
    (comp (ref "R2")
      (value "10K0")
      (footprint "eagle-import:0402")
      (fields (field (name "PARTNO") "RMCF0402JT10K0"))
      (libsource (lib "eagle-import") (part "R_0402_10K0"))
    )
    (comp (ref "R3")
      (value "10K0")
      (footprint "eagle-import:0402")
      (fields (field (name "PARTNO") "RMCF0402JT10K0"))
      (libsource (lib "eagle-import") (part "R_0402_10K0"))
    )
    (comp (ref "R4")
      (value "2K2")
      (footprint "eagle-import:0402")
      (fields (field (name "PARTNO") "RMCF0402JT2K20"))
      (libsource (lib "eagle-import") (part "R_0402_2K2"))
    )
    (comp (ref "R5")
      (value "10K0")
      (footprint "eagle-import:0402")
      (fields (field (name "PARTNO") "RMCF0402JT10K0"))
      (libsource (lib "eagle-import") (part "R_0402_10K0"))
    )
    (comp (ref "R6")
      (value "10K0")
      (footprint "eagle-import:0402")
      (fields (field (name "PARTNO") "RMCF0402JT10K0"))
      (libsource (lib "eagle-import") (part "R_0402_10K0"))
    )
    (comp (ref "R8")
      (value "10K0")
      (footprint "eagle-import:0402")
      (fields (field (name "PARTNO") "RMCF0402JT10K0"))
      (libsource (lib "eagle-import") (part "R_0402_10K0"))
    )
    (comp (ref "R10")
      (value "10K0")
      (footprint "eagle-import:0402")
      (fields (field (name "PARTNO") "RMCF0402JT10K0"))
      (libsource (lib "eagle-import") (part "R_0402_10K0"))
    )
    (comp (ref "R12")
      (value "470R0")
      (footprint "eagle-import:0402")
      (fields (field (name "PARTNO") "RMCF0402JT470R"))
      (libsource (lib "eagle-import") (part "R_0402_470R0"))
    )
    (comp (ref "R13")
      (value "10K0")
      (footprint "eagle-import:0402")
      (fields (field (name "PARTNO") "RMCF0402JT10K0"))
      (libsource (lib "eagle-import") (part "R_0402_10K0"))
    )
    (comp (ref "R15")
      (value "10K0")
      (footprint "eagle-import:0402")
      (fields (field (name "PARTNO") "RMCF0402JT10K0"))
      (libsource (lib "eagle-import") (part "R_0402_10K0"))
    )
    (comp (ref "U1")
      (value "RENESAS_R7FS5D37A3A01CFM#AA0PLQP0064KB-C_REN-M")
      (footprint "eagle-import:PLQP0064KB-C_REN-M")
      (fields
        (field (name "PARTNO") "R7FS3A37A3A01CFM#AA0")
        (field (name "COPYRIGHT") "Copyright (C) 2023 Ultra Librarian. All rights reserved.")
      )
      (libsource (lib "eagle-import") (part "RENESAS_R7FS5D37A3A01CFM#AA0PLQP0064KB-C_REN-M"))
    )
    (comp (ref "U2")
      (value "S7G2LQFP176")
      (footprint "eagle-import:LQFP176_24X24")
      (fields (field (name "PARTNO") "R7FS7G27H3A01CFC#AA0"))
      (libsource (lib "eagle-import") (part "RENESAS_S7G2_X_176"))
    )
    (comp (ref "U3")
      (value "RENESAS_R7FS5D37A3A01CFM#AA0PLQP0064KB-C_REN-M")
      (footprint "eagle-import:PLQP0064KB-C_REN-M")
      (fields
        (field (name "PARTNO") "R7FS3A37A3A01CFM#AA0")
        (field (name "COPYRIGHT") "Copyright (C) 2023 Ultra Librarian. All rights reserved.")
      )
      (libsource (lib "eagle-import") (part "RENESAS_R7FS5D37A3A01CFM#AA0PLQP0064KB-C_REN-M"))
    )
    (comp (ref "U6")
      (value "RENESAS_R7FS5D37A3A01CFM#AA0PLQP0064KB-C_REN-M")
      (footprint "eagle-import:PLQP0064KB-C_REN-M")
      (fields
        (field (name "PARTNO") "R7FS3A37A3A01CFM#AA0")
        (field (name "COPYRIGHT") "Copyright (C) 2023 Ultra Librarian. All rights reserved.")
      )
      (libsource (lib "eagle-import") (part "RENESAS_R7FS5D37A3A01CFM#AA0PLQP0064KB-C_REN-M"))
    )
    (comp (ref "U8")
      (value "RENESAS_R7FS5D37A3A01CFM#AA0PLQP0064KB-C_REN-M")
      (footprint "eagle-import:PLQP0064KB-C_REN-M")
      (fields
        (field (name "PARTNO") "R7FS3A37A3A01CFM#AA0")
        (field (name "COPYRIGHT") "Copyright (C) 2023 Ultra Librarian. All rights reserved.")
      )
      (libsource (lib "eagle-import") (part "RENESAS_R7FS5D37A3A01CFM#AA0PLQP0064KB-C_REN-M"))
    )
    (comp (ref "U10")
      (value "RENESAS_R7FS5D37A3A01CFM#AA0PLQP0064KB-C_REN-M")
      (footprint "eagle-import:PLQP0064KB-C_REN-M")
      (fields
        (field (name "PARTNO") "R7FS3A37A3A01CFM#AA0")
        (field (name "COPYRIGHT") "Copyright (C) 2023 Ultra Librarian. All rights reserved.")
      )
      (libsource (lib "eagle-import") (part "RENESAS_R7FS5D37A3A01CFM#AA0PLQP0064KB-C_REN-M"))
    )
    (comp (ref "U12")
      (value "RENESAS_R7FS5D37A3A01CFM#AA0PLQP0064KB-C_REN-M")
      (footprint "eagle-import:PLQP0064KB-C_REN-M")
      (fields
        (field (name "PARTNO") "R7FS3A37A3A01CFM#AA0")
        (field (name "COPYRIGHT") "Copyright (C) 2023 Ultra Librarian. All rights reserved.")
      )
      (libsource (lib "eagle-import") (part "RENESAS_R7FS5D37A3A01CFM#AA0PLQP0064KB-C_REN-M"))
    )
    (comp (ref "X2")
      (value "32.768KHz")
      (footprint "eagle-import:SMD_X_2_PADS")
      (fields (field (name "PARTNO") "ABS07-32.768KHZ-T"))
      (libsource (lib "eagle-import") (part "XTAL_32.768KHZ"))
    )
    (comp (ref "X3")
      (value "32.768KHz")
      (footprint "eagle-import:SMD_X_2_PADS")
      (fields (field (name "PARTNO") "ABS07-32.768KHZ-T"))
      (libsource (lib "eagle-import") (part "XTAL_32.768KHZ"))
    )
    (comp (ref "X4")
      (value "24MHz")
      (footprint "eagle-import:SMD_3225")
      (fields (field (name "PARTNO") "FA-238 24.0000MB-C3 "))
      (libsource (lib "eagle-import") (part "XTAL_24_MHZ"))
    )
    (comp (ref "X5")
      (value "32.768KHz")
      (footprint "eagle-import:SMD_X_2_PADS")
      (fields (field (name "PARTNO") "ABS07-32.768KHZ-T"))
      (libsource (lib "eagle-import") (part "XTAL_32.768KHZ"))
    )
    (comp (ref "X7")
      (value "32.768KHz")
      (footprint "eagle-import:SMD_X_2_PADS")
      (fields (field (name "PARTNO") "ABS07-32.768KHZ-T"))
      (libsource (lib "eagle-import") (part "XTAL_32.768KHZ"))
    )
    (comp (ref "X9")
      (value "32.768KHz")
      (footprint "eagle-import:SMD_X_2_PADS")
      (fields (field (name "PARTNO") "ABS07-32.768KHZ-T"))
      (libsource (lib "eagle-import") (part "XTAL_32.768KHZ"))
    )
    (comp (ref "X11")
      (value "32.768KHz")
      (footprint "eagle-import:SMD_X_2_PADS")
      (fields (field (name "PARTNO") "ABS07-32.768KHZ-T"))
      (libsource (lib "eagle-import") (part "XTAL_32.768KHZ"))
    )
    (comp (ref "X13")
      (value "32.768KHz")
      (footprint "eagle-import:SMD_X_2_PADS")
      (fields (field (name "PARTNO") "ABS07-32.768KHZ-T"))
      (libsource (lib "eagle-import") (part "XTAL_32.768KHZ"))
    )
    (comp (ref "Y1")
      (value "XTAL_12MHZ_ABM8G-12.000MHZ-B4Y-T")
      (footprint "eagle-import:CRYSTAL_ABM8G_ABR")
      (fields
        (field (name "PARTNO") "ABM8G-12.000MHZ-B4Y-T")
        (field (name "COPYRIGHT") "Copyright (C) 2023 Ultra Librarian. All rights reserved.")
      )
      (libsource (lib "eagle-import") (part "XTAL_12MHZ_ABM8G-12.000MHZ-B4Y-T"))
    )
    (comp (ref "Y3")
      (value "XTAL_12MHZ_ABM8G-12.000MHZ-B4Y-T")
      (footprint "eagle-import:CRYSTAL_ABM8G_ABR")
      (fields
        (field (name "PARTNO") "ABM8G-12.000MHZ-B4Y-T")
        (field (name "COPYRIGHT") "Copyright (C) 2023 Ultra Librarian. All rights reserved.")
      )
      (libsource (lib "eagle-import") (part "XTAL_12MHZ_ABM8G-12.000MHZ-B4Y-T"))
    )
    (comp (ref "Y5")
      (value "XTAL_12MHZ_ABM8G-12.000MHZ-B4Y-T")
      (footprint "eagle-import:CRYSTAL_ABM8G_ABR")
      (fields
        (field (name "PARTNO") "ABM8G-12.000MHZ-B4Y-T")
        (field (name "COPYRIGHT") "Copyright (C) 2023 Ultra Librarian. All rights reserved.")
      )
      (libsource (lib "eagle-import") (part "XTAL_12MHZ_ABM8G-12.000MHZ-B4Y-T"))
    )
    (comp (ref "Y7")
      (value "XTAL_12MHZ_ABM8G-12.000MHZ-B4Y-T")
      (footprint "eagle-import:CRYSTAL_ABM8G_ABR")
      (fields
        (field (name "PARTNO") "ABM8G-12.000MHZ-B4Y-T")
        (field (name "COPYRIGHT") "Copyright (C) 2023 Ultra Librarian. All rights reserved.")
      )
      (libsource (lib "eagle-import") (part "XTAL_12MHZ_ABM8G-12.000MHZ-B4Y-T"))
    )
    (comp (ref "Y9")
      (value "XTAL_12MHZ_ABM8G-12.000MHZ-B4Y-T")
      (footprint "eagle-import:CRYSTAL_ABM8G_ABR")
      (fields
        (field (name "PARTNO") "ABM8G-12.000MHZ-B4Y-T")
        (field (name "COPYRIGHT") "Copyright (C) 2023 Ultra Librarian. All rights reserved.")
      )
      (libsource (lib "eagle-import") (part "XTAL_12MHZ_ABM8G-12.000MHZ-B4Y-T"))
    )
    (comp (ref "Y11")
      (value "XTAL_12MHZ_ABM8G-12.000MHZ-B4Y-T")
      (footprint "eagle-import:CRYSTAL_ABM8G_ABR")
      (fields
        (field (name "PARTNO") "ABM8G-12.000MHZ-B4Y-T")
        (field (name "COPYRIGHT") "Copyright (C) 2023 Ultra Librarian. All rights reserved.")
      )
      (libsource (lib "eagle-import") (part "XTAL_12MHZ_ABM8G-12.000MHZ-B4Y-T"))
    )
  )
  (nets
    (net (code "1") (name "DFI_01_A1") (class "Default")
      (node (ref "U1") (pin "50") (pinfunction "50/P501_50") (pintype "bidirectional"))
      (node (ref "U10") (pin "50") (pinfunction "50/P501_50") (pintype "bidirectional"))
      (node (ref "U12") (pin "50") (pinfunction "50/P501_50") (pintype "bidirectional"))
      (node (ref "U3") (pin "50") (pinfunction "50/P501_50") (pintype "bidirectional"))
      (node (ref "U6") (pin "50") (pinfunction "50/P501_50") (pintype "bidirectional"))
      (node (ref "U8") (pin "50") (pinfunction "50/P501_50") (pintype "bidirectional"))
    )
    (net (code "2") (name "DFI_02_A1") (class "Default")
      (node (ref "U1") (pin "62") (pinfunction "62/P002_62") (pintype "bidirectional"))
      (node (ref "U10") (pin "62") (pinfunction "62/P002_62") (pintype "bidirectional"))
      (node (ref "U12") (pin "62") (pinfunction "62/P002_62") (pintype "bidirectional"))
      (node (ref "U3") (pin "62") (pinfunction "62/P002_62") (pintype "bidirectional"))
      (node (ref "U6") (pin "62") (pinfunction "62/P002_62") (pintype "bidirectional"))
      (node (ref "U8") (pin "62") (pinfunction "62/P002_62") (pintype "bidirectional"))
    )
    (net (code "3") (name "DFO_01_A1") (class "Default")
      (node (ref "U1") (pin "30") (pinfunction "30/P302_30") (pintype "bidirectional"))
      (node (ref "U10") (pin "30") (pinfunction "30/P302_30") (pintype "bidirectional"))
      (node (ref "U12") (pin "30") (pinfunction "30/P302_30") (pintype "bidirectional"))
      (node (ref "U3") (pin "30") (pinfunction "30/P302_30") (pintype "bidirectional"))
      (node (ref "U6") (pin "30") (pinfunction "30/P302_30") (pintype "bidirectional"))
      (node (ref "U8") (pin "30") (pinfunction "30/P302_30") (pintype "bidirectional"))
    )
    (net (code "4") (name "DFO_02_A1") (class "Default")
      (node (ref "U1") (pin "41") (pinfunction "41/P107_41") (pintype "bidirectional"))
      (node (ref "U10") (pin "41") (pinfunction "41/P107_41") (pintype "bidirectional"))
      (node (ref "U12") (pin "41") (pinfunction "41/P107_41") (pintype "bidirectional"))
      (node (ref "U3") (pin "41") (pinfunction "41/P107_41") (pintype "bidirectional"))
      (node (ref "U6") (pin "41") (pinfunction "41/P107_41") (pintype "bidirectional"))
      (node (ref "U8") (pin "41") (pinfunction "41/P107_41") (pintype "bidirectional"))
    )
    (net (code "5") (name "DFO_03_A1") (class "Default")
      (node (ref "U1") (pin "42") (pinfunction "42/P106_42") (pintype "bidirectional"))
      (node (ref "U10") (pin "42") (pinfunction "42/P106_42") (pintype "bidirectional"))
      (node (ref "U12") (pin "42") (pinfunction "42/P106_42") (pintype "bidirectional"))
      (node (ref "U3") (pin "42") (pinfunction "42/P106_42") (pintype "bidirectional"))
      (node (ref "U6") (pin "42") (pinfunction "42/P106_42") (pintype "bidirectional"))
      (node (ref "U8") (pin "42") (pinfunction "42/P106_42") (pintype "bidirectional"))
    )
    (net (code "6") (name "DIR_M0A1") (class "Default")
      (node (ref "U1") (pin "15") (pinfunction "15/P408_15") (pintype "bidirectional"))
      (node (ref "U10") (pin "15") (pinfunction "15/P408_15") (pintype "bidirectional"))
      (node (ref "U12") (pin "15") (pinfunction "15/P408_15") (pintype "bidirectional"))
      (node (ref "U3") (pin "15") (pinfunction "15/P408_15") (pintype "bidirectional"))
      (node (ref "U6") (pin "15") (pinfunction "15/P408_15") (pintype "bidirectional"))
      (node (ref "U8") (pin "15") (pinfunction "15/P408_15") (pintype "bidirectional"))
    )
    (net (code "7") (name "DIR_M1A1") (class "Default")
      (node (ref "U1") (pin "3") (pinfunction "3/P402_3") (pintype "bidirectional"))
      (node (ref "U10") (pin "3") (pinfunction "3/P402_3") (pintype "bidirectional"))
      (node (ref "U12") (pin "3") (pinfunction "3/P402_3") (pintype "bidirectional"))
      (node (ref "U3") (pin "3") (pinfunction "3/P402_3") (pintype "bidirectional"))
      (node (ref "U6") (pin "3") (pinfunction "3/P402_3") (pintype "bidirectional"))
      (node (ref "U8") (pin "3") (pinfunction "3/P402_3") (pintype "bidirectional"))
    )
    (net (code "8") (name "ENABLE_M0A1") (class "Default")
      (node (ref "U1") (pin "14") (pinfunction "14/P409_14") (pintype "bidirectional"))
      (node (ref "U10") (pin "14") (pinfunction "14/P409_14") (pintype "bidirectional"))
      (node (ref "U12") (pin "14") (pinfunction "14/P409_14") (pintype "bidirectional"))
      (node (ref "U3") (pin "14") (pinfunction "14/P409_14") (pintype "bidirectional"))
      (node (ref "U6") (pin "14") (pinfunction "14/P409_14") (pintype "bidirectional"))
      (node (ref "U8") (pin "14") (pinfunction "14/P409_14") (pintype "bidirectional"))
    )
    (net (code "9") (name "ENABLE_M1A1") (class "Default")
      (node (ref "U1") (pin "2") (pinfunction "2/P401_2") (pintype "bidirectional"))
      (node (ref "U10") (pin "2") (pinfunction "2/P401_2") (pintype "bidirectional"))
      (node (ref "U12") (pin "2") (pinfunction "2/P401_2") (pintype "bidirectional"))
      (node (ref "U3") (pin "2") (pinfunction "2/P401_2") (pintype "bidirectional"))
      (node (ref "U6") (pin "2") (pinfunction "2/P401_2") (pintype "bidirectional"))
      (node (ref "U8") (pin "2") (pinfunction "2/P401_2") (pintype "bidirectional"))
    )
    (net (code "10") (name "ESTOP") (class "Default")
      (node (ref "U2") (pin "69") (pinfunction "P2_0(INPUT_ONLY)_69") (pintype "bidirectional"))
    )
    (net (code "11") (name "ESTOP_A1") (class "Default")
      (node (ref "U1") (pin "27") (pinfunction "27/P200_27") (pintype "bidirectional"))
      (node (ref "U10") (pin "27") (pinfunction "27/P200_27") (pintype "bidirectional"))
      (node (ref "U12") (pin "27") (pinfunction "27/P200_27") (pintype "bidirectional"))
      (node (ref "U3") (pin "27") (pinfunction "27/P200_27") (pintype "bidirectional"))
      (node (ref "U6") (pin "27") (pinfunction "27/P200_27") (pintype "bidirectional"))
      (node (ref "U8") (pin "27") (pinfunction "27/P200_27") (pintype "bidirectional"))
    )
    (net (code "12") (name "GND") (class "Default")
      (node (ref "C1") (pin "P$1") (pinfunction "1_P$1") (pintype "passive"))
      (node (ref "C10") (pin "P$2") (pinfunction "2_P$2") (pintype "passive"))
      (node (ref "C100") (pin "P$2") (pinfunction "2_P$2") (pintype "passive"))
      (node (ref "C101") (pin "P$2") (pinfunction "2_P$2") (pintype "passive"))
      (node (ref "C11") (pin "P$2") (pinfunction "2_P$2") (pintype "passive"))
      (node (ref "C117") (pin "P$2") (pinfunction "2_P$2") (pintype "passive"))
      (node (ref "C118") (pin "P$2") (pinfunction "2_P$2") (pintype "passive"))
      (node (ref "C119") (pin "P$2") (pinfunction "2_P$2") (pintype "passive"))
      (node (ref "C12") (pin "P$2") (pinfunction "2_P$2") (pintype "passive"))
      (node (ref "C120") (pin "P$2") (pinfunction "2_P$2") (pintype "passive"))
      (node (ref "C121") (pin "P$2") (pinfunction "2_P$2") (pintype "passive"))
      (node (ref "C122") (pin "P$2") (pinfunction "2_P$2") (pintype "passive"))
      (node (ref "C123") (pin "P$2") (pinfunction "2_P$2") (pintype "passive"))
      (node (ref "C124") (pin "P$2") (pinfunction "2_P$2") (pintype "passive"))
      (node (ref "C125") (pin "P$1") (pinfunction "1_P$1") (pintype "passive"))
      (node (ref "C126") (pin "P$1") (pinfunction "1_P$1") (pintype "passive"))
      (node (ref "C127") (pin "P$2") (pinfunction "2_P$2") (pintype "passive"))
      (node (ref "C128") (pin "P$2") (pinfunction "2_P$2") (pintype "passive"))
      (node (ref "C129") (pin "P$2") (pinfunction "2_P$2") (pintype "passive"))
      (node (ref "C13") (pin "P$2") (pinfunction "2_P$2") (pintype "passive"))
      (node (ref "C130") (pin "P$2") (pinfunction "2_P$2") (pintype "passive"))
      (node (ref "C131") (pin "P$2") (pinfunction "2_P$2") (pintype "passive"))
      (node (ref "C14") (pin "P$1") (pinfunction "1_P$1") (pintype "passive"))
      (node (ref "C147") (pin "P$2") (pinfunction "2_P$2") (pintype "passive"))
      (node (ref "C148") (pin "P$2") (pinfunction "2_P$2") (pintype "passive"))
      (node (ref "C149") (pin "P$2") (pinfunction "2_P$2") (pintype "passive"))
      (node (ref "C15") (pin "P$1") (pinfunction "1_P$1") (pintype "passive"))
      (node (ref "C150") (pin "P$2") (pinfunction "2_P$2") (pintype "passive"))
      (node (ref "C151") (pin "P$2") (pinfunction "2_P$2") (pintype "passive"))
      (node (ref "C152") (pin "P$2") (pinfunction "2_P$2") (pintype "passive"))
      (node (ref "C153") (pin "P$2") (pinfunction "2_P$2") (pintype "passive"))
      (node (ref "C154") (pin "P$2") (pinfunction "2_P$2") (pintype "passive"))
      (node (ref "C155") (pin "P$1") (pinfunction "1_P$1") (pintype "passive"))
      (node (ref "C156") (pin "P$1") (pinfunction "1_P$1") (pintype "passive"))
      (node (ref "C157") (pin "P$2") (pinfunction "2_P$2") (pintype "passive"))
      (node (ref "C158") (pin "P$2") (pinfunction "2_P$2") (pintype "passive"))
      (node (ref "C159") (pin "P$2") (pinfunction "2_P$2") (pintype "passive"))
      (node (ref "C160") (pin "P$2") (pinfunction "2_P$2") (pintype "passive"))
      (node (ref "C161") (pin "P$2") (pinfunction "2_P$2") (pintype "passive"))
      (node (ref "C177") (pin "P$2") (pinfunction "2_P$2") (pintype "passive"))
      (node (ref "C178") (pin "P$2") (pinfunction "2_P$2") (pintype "passive"))
      (node (ref "C179") (pin "P$2") (pinfunction "2_P$2") (pintype "passive"))
      (node (ref "C180") (pin "P$2") (pinfunction "2_P$2") (pintype "passive"))
      (node (ref "C181") (pin "P$2") (pinfunction "2_P$2") (pintype "passive"))
      (node (ref "C182") (pin "P$2") (pinfunction "2_P$2") (pintype "passive"))
      (node (ref "C183") (pin "P$2") (pinfunction "2_P$2") (pintype "passive"))
      (node (ref "C184") (pin "P$2") (pinfunction "2_P$2") (pintype "passive"))
      (node (ref "C185") (pin "P$1") (pinfunction "1_P$1") (pintype "passive"))
      (node (ref "C186") (pin "P$1") (pinfunction "1_P$1") (pintype "passive"))
      (node (ref "C187") (pin "P$2") (pinfunction "2_P$2") (pintype "passive"))
      (node (ref "C188") (pin "P$2") (pinfunction "2_P$2") (pintype "passive"))
      (node (ref "C189") (pin "P$2") (pinfunction "2_P$2") (pintype "passive"))
      (node (ref "C19") (pin "P$2") (pinfunction "2_P$2") (pintype "passive"))
      (node (ref "C190") (pin "P$2") (pinfunction "2_P$2") (pintype "passive"))
      (node (ref "C191") (pin "P$2") (pinfunction "2_P$2") (pintype "passive"))
      (node (ref "C2") (pin "P$1") (pinfunction "1_P$1") (pintype "passive"))
      (node (ref "C20") (pin "P$2") (pinfunction "2_P$2") (pintype "passive"))
      (node (ref "C21") (pin "P$2") (pinfunction "2_P$2") (pintype "passive"))
      (node (ref "C23") (pin "P$1") (pinfunction "1_P$1") (pintype "passive"))
      (node (ref "C26") (pin "P$2") (pinfunction "2_P$2") (pintype "passive"))
      (node (ref "C28") (pin "P$2") (pinfunction "2_P$2") (pintype "passive"))
      (node (ref "C29") (pin "P$2") (pinfunction "2_P$2") (pintype "passive"))
      (node (ref "C3") (pin "P$1") (pinfunction "1_P$1") (pintype "passive"))
      (node (ref "C31") (pin "P$2") (pinfunction "2_P$2") (pintype "passive"))
      (node (ref "C39") (pin "P$2") (pinfunction "2_P$2") (pintype "passive"))
      (node (ref "C4") (pin "P$1") (pinfunction "1_P$1") (pintype "passive"))
      (node (ref "C40") (pin "P$2") (pinfunction "2_P$2") (pintype "passive"))
      (node (ref "C41") (pin "P$2") (pinfunction "2_P$2") (pintype "passive"))
      (node (ref "C42") (pin "P$2") (pinfunction "2_P$2") (pintype "passive"))
      (node (ref "C43") (pin "P$2") (pinfunction "2_P$2") (pintype "passive"))
      (node (ref "C44") (pin "P$1") (pinfunction "1_P$1") (pintype "passive"))
      (node (ref "C45") (pin "P$1") (pinfunction "1_P$1") (pintype "passive"))
      (node (ref "C46") (pin "P$1") (pinfunction "1_P$1") (pintype "passive"))
      (node (ref "C47") (pin "P$2") (pinfunction "2_P$2") (pintype "passive"))
      (node (ref "C48") (pin "P$2") (pinfunction "2_P$2") (pintype "passive"))
      (node (ref "C49") (pin "P$2") (pinfunction "2_P$2") (pintype "passive"))
      (node (ref "C5") (pin "P$2") (pinfunction "2_P$2") (pintype "passive"))
      (node (ref "C50") (pin "P$1") (pinfunction "1_P$1") (pintype "passive"))
      (node (ref "C51") (pin "P$1") (pinfunction "1_P$1") (pintype "passive"))
      (node (ref "C52") (pin "P$2") (pinfunction "2_P$2") (pintype "passive"))
      (node (ref "C53") (pin "P$2") (pinfunction "2_P$2") (pintype "passive"))
      (node (ref "C54") (pin "P$2") (pinfunction "2_P$2") (pintype "passive"))
      (node (ref "C55") (pin "P$2") (pinfunction "2_P$2") (pintype "passive"))
      (node (ref "C56") (pin "P$2") (pinfunction "2_P$2") (pintype "passive"))
      (node (ref "C57") (pin "P$2") (pinfunction "2_P$2") (pintype "passive"))
      (node (ref "C58") (pin "P$2") (pinfunction "2_P$2") (pintype "passive"))
      (node (ref "C59") (pin "P$2") (pinfunction "2_P$2") (pintype "passive"))
      (node (ref "C6") (pin "P$2") (pinfunction "2_P$2") (pintype "passive"))
      (node (ref "C60") (pin "P$2") (pinfunction "2_P$2") (pintype "passive"))
      (node (ref "C61") (pin "P$2") (pinfunction "2_P$2") (pintype "passive"))
      (node (ref "C62") (pin "P$2") (pinfunction "2_P$2") (pintype "passive"))
      (node (ref "C63") (pin "P$2") (pinfunction "2_P$2") (pintype "passive"))
      (node (ref "C64") (pin "P$2") (pinfunction "2_P$2") (pintype "passive"))
      (node (ref "C65") (pin "P$1") (pinfunction "1_P$1") (pintype "passive"))
      (node (ref "C66") (pin "P$1") (pinfunction "1_P$1") (pintype "passive"))
      (node (ref "C67") (pin "P$2") (pinfunction "2_P$2") (pintype "passive"))
      (node (ref "C68") (pin "P$2") (pinfunction "2_P$2") (pintype "passive"))
      (node (ref "C69") (pin "P$2") (pinfunction "2_P$2") (pintype "passive"))
      (node (ref "C7") (pin "P$1") (pinfunction "1_P$1") (pintype "passive"))
      (node (ref "C70") (pin "P$2") (pinfunction "2_P$2") (pintype "passive"))
      (node (ref "C71") (pin "P$2") (pinfunction "2_P$2") (pintype "passive"))
      (node (ref "C8") (pin "P$1") (pinfunction "1_P$1") (pintype "passive"))
      (node (ref "C87") (pin "P$2") (pinfunction "2_P$2") (pintype "passive"))
      (node (ref "C88") (pin "P$2") (pinfunction "2_P$2") (pintype "passive"))
      (node (ref "C89") (pin "P$2") (pinfunction "2_P$2") (pintype "passive"))
      (node (ref "C9") (pin "P$2") (pinfunction "2_P$2") (pintype "passive"))
      (node (ref "C90") (pin "P$2") (pinfunction "2_P$2") (pintype "passive"))
      (node (ref "C91") (pin "P$2") (pinfunction "2_P$2") (pintype "passive"))
      (node (ref "C92") (pin "P$2") (pinfunction "2_P$2") (pintype "passive"))
      (node (ref "C93") (pin "P$2") (pinfunction "2_P$2") (pintype "passive"))
      (node (ref "C94") (pin "P$2") (pinfunction "2_P$2") (pintype "passive"))
      (node (ref "C95") (pin "P$1") (pinfunction "1_P$1") (pintype "passive"))
      (node (ref "C96") (pin "P$1") (pinfunction "1_P$1") (pintype "passive"))
      (node (ref "C97") (pin "P$2") (pinfunction "2_P$2") (pintype "passive"))
      (node (ref "C98") (pin "P$2") (pinfunction "2_P$2") (pintype "passive"))
      (node (ref "C99") (pin "P$2") (pinfunction "2_P$2") (pintype "passive"))
      (node (ref "J1") (pin "10") (pinfunction "10_10") (pintype "passive"))
      (node (ref "J1") (pin "6") (pinfunction "6_6") (pintype "passive"))
      (node (ref "J1") (pin "8") (pinfunction "8_8") (pintype "passive"))
      (node (ref "J10") (pin "10") (pinfunction "10_10") (pintype "passive"))
      (node (ref "J10") (pin "6") (pinfunction "6_6") (pintype "passive"))
      (node (ref "J10") (pin "8") (pinfunction "8_8") (pintype "passive"))
      (node (ref "J13") (pin "P$1") (pinfunction "P$1_P$1") (pintype "bidirectional"))
      (node (ref "J13") (pin "P$3") (pinfunction "P$3_P$3") (pintype "bidirectional"))
      (node (ref "J13") (pin "P$4") (pinfunction "P$4_P$4") (pintype "bidirectional"))
      (node (ref "J14") (pin "1") (pinfunction "1_1") (pintype "passive"))
      (node (ref "J14") (pin "2") (pinfunction "2_2") (pintype "passive"))
      (node (ref "J15") (pin "10") (pinfunction "10_10") (pintype "passive"))
      (node (ref "J15") (pin "6") (pinfunction "6_6") (pintype "passive"))
      (node (ref "J15") (pin "8") (pinfunction "8_8") (pintype "passive"))
      (node (ref "J18") (pin "1") (pinfunction "1_1") (pintype "passive"))
      (node (ref "J18") (pin "2") (pinfunction "2_2") (pintype "passive"))
      (node (ref "J19") (pin "10") (pinfunction "10_10") (pintype "passive"))
      (node (ref "J19") (pin "6") (pinfunction "6_6") (pintype "passive"))
      (node (ref "J19") (pin "8") (pinfunction "8_8") (pintype "passive"))
      (node (ref "J22") (pin "1") (pinfunction "1_1") (pintype "passive"))
      (node (ref "J22") (pin "2") (pinfunction "2_2") (pintype "passive"))
      (node (ref "J23") (pin "10") (pinfunction "10_10") (pintype "passive"))
      (node (ref "J23") (pin "6") (pinfunction "6_6") (pintype "passive"))
      (node (ref "J23") (pin "8") (pinfunction "8_8") (pintype "passive"))
      (node (ref "J3") (pin "1") (pinfunction "1_1") (pintype "passive"))
      (node (ref "J3") (pin "2") (pinfunction "2_2") (pintype "passive"))
      (node (ref "J4") (pin "10") (pinfunction "10_10") (pintype "passive"))
      (node (ref "J4") (pin "6") (pinfunction "6_6") (pintype "passive"))
      (node (ref "J4") (pin "8") (pinfunction "8_8") (pintype "passive"))
      (node (ref "J5") (pin "1") (pinfunction "1_1") (pintype "passive"))
      (node (ref "J5") (pin "2") (pinfunction "2_2") (pintype "passive"))
      (node (ref "J6") (pin "10") (pinfunction "10_10") (pintype "passive"))
      (node (ref "J6") (pin "6") (pinfunction "6_6") (pintype "passive"))
      (node (ref "J6") (pin "8") (pinfunction "8_8") (pintype "passive"))
      (node (ref "J9") (pin "1") (pinfunction "1_1") (pintype "passive"))
      (node (ref "J9") (pin "2") (pinfunction "2_2") (pintype "passive"))
      (node (ref "LED2") (pin "2") (pinfunction "C_2") (pintype "passive"))
      (node (ref "R1") (pin "P$1") (pinfunction "1_P$1") (pintype "passive"))
      (node (ref "R2") (pin "P$1") (pinfunction "1_P$1") (pintype "passive"))
      (node (ref "R4") (pin "P$1") (pinfunction "1_P$1") (pintype "passive"))
      (node (ref "U1") (pin "17") (pinfunction "17/VSS_USB_17") (pintype "power_in"))
      (node (ref "U1") (pin "28") (pinfunction "28/VSS_28") (pintype "bidirectional"))
      (node (ref "U1") (pin "39") (pinfunction "39/VSS_39") (pintype "power_in"))
      (node (ref "U1") (pin "55") (pinfunction "55/VREFL_55") (pintype "bidirectional"))
      (node (ref "U1") (pin "58") (pinfunction "58/AVSS0_58") (pintype "bidirectional"))
      (node (ref "U1") (pin "59") (pinfunction "59/VREFL0_59") (pintype "bidirectional"))
      (node (ref "U1") (pin "8") (pinfunction "8/VSS_8") (pintype "power_in"))
      (node (ref "U10") (pin "17") (pinfunction "17/VSS_USB_17") (pintype "power_in"))
      (node (ref "U10") (pin "28") (pinfunction "28/VSS_28") (pintype "bidirectional"))
      (node (ref "U10") (pin "39") (pinfunction "39/VSS_39") (pintype "power_in"))
      (node (ref "U10") (pin "55") (pinfunction "55/VREFL_55") (pintype "bidirectional"))
      (node (ref "U10") (pin "58") (pinfunction "58/AVSS0_58") (pintype "bidirectional"))
      (node (ref "U10") (pin "59") (pinfunction "59/VREFL0_59") (pintype "bidirectional"))
      (node (ref "U10") (pin "8") (pinfunction "8/VSS_8") (pintype "power_in"))
      (node (ref "U12") (pin "17") (pinfunction "17/VSS_USB_17") (pintype "power_in"))
      (node (ref "U12") (pin "28") (pinfunction "28/VSS_28") (pintype "bidirectional"))
      (node (ref "U12") (pin "39") (pinfunction "39/VSS_39") (pintype "power_in"))
      (node (ref "U12") (pin "55") (pinfunction "55/VREFL_55") (pintype "bidirectional"))
      (node (ref "U12") (pin "58") (pinfunction "58/AVSS0_58") (pintype "bidirectional"))
      (node (ref "U12") (pin "59") (pinfunction "59/VREFL0_59") (pintype "bidirectional"))
      (node (ref "U12") (pin "8") (pinfunction "8/VSS_8") (pintype "power_in"))
      (node (ref "U2") (pin "111") (pinfunction "VSS(IO)5_111") (pintype "bidirectional"))
      (node (ref "U2") (pin "124") (pinfunction "VSS(IO)6_124") (pintype "bidirectional"))
      (node (ref "U2") (pin "139") (pinfunction "VSS(IO)7_139") (pintype "bidirectional"))
      (node (ref "U2") (pin "150") (pinfunction "VSS(IO)8_150") (pintype "bidirectional"))
      (node (ref "U2") (pin "153") (pinfunction "VREFL_153") (pintype "bidirectional"))
      (node (ref "U2") (pin "156") (pinfunction "AVSS0_156") (pintype "bidirectional"))
      (node (ref "U2") (pin "157") (pinfunction "VREFL0_157") (pintype "bidirectional"))
      (node (ref "U2") (pin "170") (pinfunction "VSS(IO)9_170") (pintype "bidirectional"))
      (node (ref "U2") (pin "22") (pinfunction "VSS1_22") (pintype "bidirectional"))
      (node (ref "U2") (pin "28") (pinfunction "AVSS_USBHS_28") (pintype "bidirectional"))
      (node (ref "U2") (pin "29") (pinfunction "PVSS_USBHS_29") (pintype "bidirectional"))
      (node (ref "U2") (pin "30") (pinfunction "VSS2_USBHS_30") (pintype "bidirectional"))
      (node (ref "U2") (pin "33") (pinfunction "VSS1_USBHS_33") (pintype "bidirectional"))
      (node (ref "U2") (pin "35") (pinfunction "VSSIO_35") (pintype "bidirectional"))
      (node (ref "U2") (pin "45") (pinfunction "VSS_USB_45") (pintype "bidirectional"))
      (node (ref "U2") (pin "60") (pinfunction "VSS(IO)2_60") (pintype "bidirectional"))
      (node (ref "U2") (pin "63") (pinfunction "VSS(IO/DCDC)_63") (pintype "bidirectional"))
      (node (ref "U2") (pin "66") (pinfunction "VCC_DCDC(IO/DCDC)_66") (pintype "bidirectional"))
      (node (ref "U2") (pin "83") (pinfunction "VSS(IO)3_83") (pintype "bidirectional"))
      (node (ref "U2") (pin "98") (pinfunction "VSS(IO)4_98") (pintype "bidirectional"))
      (node (ref "U3") (pin "17") (pinfunction "17/VSS_USB_17") (pintype "power_in"))
      (node (ref "U3") (pin "28") (pinfunction "28/VSS_28") (pintype "bidirectional"))
      (node (ref "U3") (pin "39") (pinfunction "39/VSS_39") (pintype "power_in"))
      (node (ref "U3") (pin "55") (pinfunction "55/VREFL_55") (pintype "bidirectional"))
      (node (ref "U3") (pin "58") (pinfunction "58/AVSS0_58") (pintype "bidirectional"))
      (node (ref "U3") (pin "59") (pinfunction "59/VREFL0_59") (pintype "bidirectional"))
      (node (ref "U3") (pin "8") (pinfunction "8/VSS_8") (pintype "power_in"))
      (node (ref "U6") (pin "17") (pinfunction "17/VSS_USB_17") (pintype "power_in"))
      (node (ref "U6") (pin "28") (pinfunction "28/VSS_28") (pintype "bidirectional"))
      (node (ref "U6") (pin "39") (pinfunction "39/VSS_39") (pintype "power_in"))
      (node (ref "U6") (pin "55") (pinfunction "55/VREFL_55") (pintype "bidirectional"))
      (node (ref "U6") (pin "58") (pinfunction "58/AVSS0_58") (pintype "bidirectional"))
      (node (ref "U6") (pin "59") (pinfunction "59/VREFL0_59") (pintype "bidirectional"))
      (node (ref "U6") (pin "8") (pinfunction "8/VSS_8") (pintype "power_in"))
      (node (ref "U8") (pin "17") (pinfunction "17/VSS_USB_17") (pintype "power_in"))
      (node (ref "U8") (pin "28") (pinfunction "28/VSS_28") (pintype "bidirectional"))
      (node (ref "U8") (pin "39") (pinfunction "39/VSS_39") (pintype "power_in"))
      (node (ref "U8") (pin "55") (pinfunction "55/VREFL_55") (pintype "bidirectional"))
      (node (ref "U8") (pin "58") (pinfunction "58/AVSS0_58") (pintype "bidirectional"))
      (node (ref "U8") (pin "59") (pinfunction "59/VREFL0_59") (pintype "bidirectional"))
      (node (ref "U8") (pin "8") (pinfunction "8/VSS_8") (pintype "power_in"))
      (node (ref "X4") (pin "2") (pinfunction "2_2") (pintype "bidirectional"))
      (node (ref "X4") (pin "4") (pinfunction "4_4") (pintype "bidirectional"))
      (node (ref "Y1") (pin "2") (pinfunction "2_2") (pintype "passive"))
      (node (ref "Y1") (pin "4") (pinfunction "4_4") (pintype "passive"))
      (node (ref "Y11") (pin "2") (pinfunction "2_2") (pintype "passive"))
      (node (ref "Y11") (pin "4") (pinfunction "4_4") (pintype "passive"))
      (node (ref "Y3") (pin "2") (pinfunction "2_2") (pintype "passive"))
      (node (ref "Y3") (pin "4") (pinfunction "4_4") (pintype "passive"))
      (node (ref "Y5") (pin "2") (pinfunction "2_2") (pintype "passive"))
      (node (ref "Y5") (pin "4") (pinfunction "4_4") (pintype "passive"))
      (node (ref "Y7") (pin "2") (pinfunction "2_2") (pintype "passive"))
      (node (ref "Y7") (pin "4") (pinfunction "4_4") (pintype "passive"))
      (node (ref "Y9") (pin "2") (pinfunction "2_2") (pintype "passive"))
      (node (ref "Y9") (pin "4") (pinfunction "4_4") (pintype "passive"))
    )
    (net (code "13") (name "HLFB_M0A1") (class "Default")
      (node (ref "U1") (pin "13") (pinfunction "13/P410_13") (pintype "bidirectional"))
      (node (ref "U10") (pin "13") (pinfunction "13/P410_13") (pintype "bidirectional"))
      (node (ref "U12") (pin "13") (pinfunction "13/P410_13") (pintype "bidirectional"))
      (node (ref "U3") (pin "13") (pinfunction "13/P410_13") (pintype "bidirectional"))
      (node (ref "U6") (pin "13") (pinfunction "13/P410_13") (pintype "bidirectional"))
      (node (ref "U8") (pin "13") (pinfunction "13/P410_13") (pintype "bidirectional"))
    )
    (net (code "14") (name "HLFB_M1A1") (class "Default")
      (node (ref "U1") (pin "1") (pinfunction "1/P400_1") (pintype "bidirectional"))
      (node (ref "U10") (pin "1") (pinfunction "1/P400_1") (pintype "bidirectional"))
      (node (ref "U12") (pin "1") (pinfunction "1/P400_1") (pintype "bidirectional"))
      (node (ref "U3") (pin "1") (pinfunction "1/P400_1") (pintype "bidirectional"))
      (node (ref "U6") (pin "1") (pinfunction "1/P400_1") (pintype "bidirectional"))
      (node (ref "U8") (pin "1") (pinfunction "1/P400_1") (pintype "bidirectional"))
    )
    (net (code "15") (name "LS_01_A1") (class "Default")
      (node (ref "U1") (pin "23") (pinfunction "23/P205_23") (pintype "bidirectional"))
      (node (ref "U10") (pin "23") (pinfunction "23/P205_23") (pintype "bidirectional"))
      (node (ref "U12") (pin "23") (pinfunction "23/P205_23") (pintype "bidirectional"))
      (node (ref "U3") (pin "23") (pinfunction "23/P205_23") (pintype "bidirectional"))
      (node (ref "U6") (pin "23") (pinfunction "23/P205_23") (pintype "bidirectional"))
      (node (ref "U8") (pin "23") (pinfunction "23/P205_23") (pintype "bidirectional"))
    )
    (net (code "16") (name "LS_02_A1") (class "Default")
      (node (ref "U1") (pin "53") (pinfunction "53/P015_53") (pintype "bidirectional"))
      (node (ref "U10") (pin "53") (pinfunction "53/P015_53") (pintype "bidirectional"))
      (node (ref "U12") (pin "53") (pinfunction "53/P015_53") (pintype "bidirectional"))
      (node (ref "U3") (pin "53") (pinfunction "53/P015_53") (pintype "bidirectional"))
      (node (ref "U6") (pin "53") (pinfunction "53/P015_53") (pintype "bidirectional"))
      (node (ref "U8") (pin "53") (pinfunction "53/P015_53") (pintype "bidirectional"))
    )
    (net (code "17") (name "LS_03_A1") (class "Default")
      (node (ref "U1") (pin "64") (pinfunction "64/P000_64") (pintype "bidirectional"))
      (node (ref "U10") (pin "64") (pinfunction "64/P000_64") (pintype "bidirectional"))
      (node (ref "U12") (pin "64") (pinfunction "64/P000_64") (pintype "bidirectional"))
      (node (ref "U3") (pin "64") (pinfunction "64/P000_64") (pintype "bidirectional"))
      (node (ref "U6") (pin "64") (pinfunction "64/P000_64") (pintype "bidirectional"))
      (node (ref "U8") (pin "64") (pinfunction "64/P000_64") (pintype "bidirectional"))
    )
    (net (code "18") (name "LS_04_A1") (class "Default")
      (node (ref "U1") (pin "63") (pinfunction "63/P001_63") (pintype "bidirectional"))
      (node (ref "U10") (pin "63") (pinfunction "63/P001_63") (pintype "bidirectional"))
      (node (ref "U12") (pin "63") (pinfunction "63/P001_63") (pintype "bidirectional"))
      (node (ref "U3") (pin "63") (pinfunction "63/P001_63") (pintype "bidirectional"))
      (node (ref "U6") (pin "63") (pinfunction "63/P001_63") (pintype "bidirectional"))
      (node (ref "U8") (pin "63") (pinfunction "63/P001_63") (pintype "bidirectional"))
    )
    (net (code "19") (name "LS_05") (class "Default")
      (node (ref "U2") (pin "81") (pinfunction "P3_5_81") (pintype "bidirectional"))
    )
    (net (code "20") (name "LS_06") (class "Default")
      (node (ref "U2") (pin "82") (pinfunction "P3_4_82") (pintype "bidirectional"))
    )
    (net (code "21") (name "MISO") (class "Default")
      (node (ref "J14") (pin "10") (pinfunction "10_10") (pintype "passive"))
      (node (ref "J14") (pin "9") (pinfunction "9_9") (pintype "passive"))
      (node (ref "J18") (pin "10") (pinfunction "10_10") (pintype "passive"))
      (node (ref "J18") (pin "9") (pinfunction "9_9") (pintype "passive"))
      (node (ref "J22") (pin "10") (pinfunction "10_10") (pintype "passive"))
      (node (ref "J22") (pin "9") (pinfunction "9_9") (pintype "passive"))
      (node (ref "J3") (pin "10") (pinfunction "10_10") (pintype "passive"))
      (node (ref "J3") (pin "9") (pinfunction "9_9") (pintype "passive"))
      (node (ref "J5") (pin "10") (pinfunction "10_10") (pintype "passive"))
      (node (ref "J5") (pin "9") (pinfunction "9_9") (pintype "passive"))
      (node (ref "J9") (pin "10") (pinfunction "10_10") (pintype "passive"))
      (node (ref "J9") (pin "9") (pinfunction "9_9") (pintype "passive"))
      (node (ref "U1") (pin "48") (pinfunction "48/P100_48") (pintype "bidirectional"))
      (node (ref "U10") (pin "48") (pinfunction "48/P100_48") (pintype "bidirectional"))
      (node (ref "U12") (pin "48") (pinfunction "48/P100_48") (pintype "bidirectional"))
      (node (ref "U2") (pin "132") (pinfunction "P1_0_132") (pintype "bidirectional"))
      (node (ref "U3") (pin "48") (pinfunction "48/P100_48") (pintype "bidirectional"))
      (node (ref "U6") (pin "48") (pinfunction "48/P100_48") (pintype "bidirectional"))
      (node (ref "U8") (pin "48") (pinfunction "48/P100_48") (pintype "bidirectional"))
    )
    (net (code "22") (name "MOSI") (class "Default")
      (node (ref "J14") (pin "7") (pinfunction "7_7") (pintype "passive"))
      (node (ref "J14") (pin "8") (pinfunction "8_8") (pintype "passive"))
      (node (ref "J18") (pin "7") (pinfunction "7_7") (pintype "passive"))
      (node (ref "J18") (pin "8") (pinfunction "8_8") (pintype "passive"))
      (node (ref "J22") (pin "7") (pinfunction "7_7") (pintype "passive"))
      (node (ref "J22") (pin "8") (pinfunction "8_8") (pintype "passive"))
      (node (ref "J3") (pin "7") (pinfunction "7_7") (pintype "passive"))
      (node (ref "J3") (pin "8") (pinfunction "8_8") (pintype "passive"))
      (node (ref "J5") (pin "7") (pinfunction "7_7") (pintype "passive"))
      (node (ref "J5") (pin "8") (pinfunction "8_8") (pintype "passive"))
      (node (ref "J9") (pin "7") (pinfunction "7_7") (pintype "passive"))
      (node (ref "J9") (pin "8") (pinfunction "8_8") (pintype "passive"))
      (node (ref "U1") (pin "47") (pinfunction "47/P101_47") (pintype "bidirectional"))
      (node (ref "U10") (pin "47") (pinfunction "47/P101_47") (pintype "bidirectional"))
      (node (ref "U12") (pin "47") (pinfunction "47/P101_47") (pintype "bidirectional"))
      (node (ref "U2") (pin "131") (pinfunction "P1_1_131") (pintype "bidirectional"))
      (node (ref "U3") (pin "47") (pinfunction "47/P101_47") (pintype "bidirectional"))
      (node (ref "U6") (pin "47") (pinfunction "47/P101_47") (pintype "bidirectional"))
      (node (ref "U8") (pin "47") (pinfunction "47/P101_47") (pintype "bidirectional"))
    )
    (net (code "23") (name "N$69") (class "Default")
      (node (ref "U1") (pin "18") (pinfunction "18/USB_DM_18") (pintype "bidirectional"))
      (node (ref "U10") (pin "18") (pinfunction "18/USB_DM_18") (pintype "bidirectional"))
      (node (ref "U12") (pin "18") (pinfunction "18/USB_DM_18") (pintype "bidirectional"))
      (node (ref "U3") (pin "18") (pinfunction "18/USB_DM_18") (pintype "bidirectional"))
      (node (ref "U6") (pin "18") (pinfunction "18/USB_DM_18") (pintype "bidirectional"))
      (node (ref "U8") (pin "18") (pinfunction "18/USB_DM_18") (pintype "bidirectional"))
    )
    (net (code "24") (name "N$70") (class "Default")
      (node (ref "U1") (pin "19") (pinfunction "19/USB_DP_19") (pintype "bidirectional"))
      (node (ref "U10") (pin "19") (pinfunction "19/USB_DP_19") (pintype "bidirectional"))
      (node (ref "U12") (pin "19") (pinfunction "19/USB_DP_19") (pintype "bidirectional"))
      (node (ref "U3") (pin "19") (pinfunction "19/USB_DP_19") (pintype "bidirectional"))
      (node (ref "U6") (pin "19") (pinfunction "19/USB_DP_19") (pintype "bidirectional"))
      (node (ref "U8") (pin "19") (pinfunction "19/USB_DP_19") (pintype "bidirectional"))
    )
    (net (code "25") (name "N$76") (class "Default")
      (node (ref "U1") (pin "26") (pinfunction "26/P201/MD_26") (pintype "bidirectional"))
      (node (ref "U10") (pin "26") (pinfunction "26/P201/MD_26") (pintype "bidirectional"))
      (node (ref "U12") (pin "26") (pinfunction "26/P201/MD_26") (pintype "bidirectional"))
      (node (ref "U3") (pin "26") (pinfunction "26/P201/MD_26") (pintype "bidirectional"))
      (node (ref "U6") (pin "26") (pinfunction "26/P201/MD_26") (pintype "bidirectional"))
      (node (ref "U8") (pin "26") (pinfunction "26/P201/MD_26") (pintype "bidirectional"))
    )
    (net (code "26") (name "N$82") (class "Default")
      (node (ref "U1") (pin "36") (pinfunction "36/P111_36") (pintype "bidirectional"))
      (node (ref "U10") (pin "36") (pinfunction "36/P111_36") (pintype "bidirectional"))
      (node (ref "U12") (pin "36") (pinfunction "36/P111_36") (pintype "bidirectional"))
      (node (ref "U3") (pin "36") (pinfunction "36/P111_36") (pintype "bidirectional"))
      (node (ref "U6") (pin "36") (pinfunction "36/P111_36") (pintype "bidirectional"))
      (node (ref "U8") (pin "36") (pinfunction "36/P111_36") (pintype "bidirectional"))
    )
    (net (code "27") (name "N$83") (class "Default")
      (node (ref "U1") (pin "37") (pinfunction "37/P112_37") (pintype "bidirectional"))
      (node (ref "U10") (pin "37") (pinfunction "37/P112_37") (pintype "bidirectional"))
      (node (ref "U12") (pin "37") (pinfunction "37/P112_37") (pintype "bidirectional"))
      (node (ref "U3") (pin "37") (pinfunction "37/P112_37") (pintype "bidirectional"))
      (node (ref "U6") (pin "37") (pinfunction "37/P112_37") (pintype "bidirectional"))
      (node (ref "U8") (pin "37") (pinfunction "37/P112_37") (pintype "bidirectional"))
    )
    (net (code "28") (name "N$86") (class "Default")
      (node (ref "U1") (pin "40") (pinfunction "40/VCL_40") (pintype "power_in"))
      (node (ref "U10") (pin "40") (pinfunction "40/VCL_40") (pintype "power_in"))
      (node (ref "U12") (pin "40") (pinfunction "40/VCL_40") (pintype "power_in"))
      (node (ref "U3") (pin "40") (pinfunction "40/VCL_40") (pintype "power_in"))
      (node (ref "U6") (pin "40") (pinfunction "40/VCL_40") (pintype "power_in"))
      (node (ref "U8") (pin "40") (pinfunction "40/VCL_40") (pintype "power_in"))
    )
    (net (code "29") (name "N$89") (class "Default")
      (node (ref "U1") (pin "43") (pinfunction "43/P105_43") (pintype "bidirectional"))
      (node (ref "U10") (pin "43") (pinfunction "43/P105_43") (pintype "bidirectional"))
      (node (ref "U12") (pin "43") (pinfunction "43/P105_43") (pintype "bidirectional"))
      (node (ref "U3") (pin "43") (pinfunction "43/P105_43") (pintype "bidirectional"))
      (node (ref "U6") (pin "43") (pinfunction "43/P105_43") (pintype "bidirectional"))
      (node (ref "U8") (pin "43") (pinfunction "43/P105_43") (pintype "bidirectional"))
    )
    (net (code "30") (name "N$90") (class "Default")
      (node (ref "U1") (pin "44") (pinfunction "44/P104_44") (pintype "bidirectional"))
      (node (ref "U10") (pin "44") (pinfunction "44/P104_44") (pintype "bidirectional"))
      (node (ref "U12") (pin "44") (pinfunction "44/P104_44") (pintype "bidirectional"))
      (node (ref "U3") (pin "44") (pinfunction "44/P104_44") (pintype "bidirectional"))
      (node (ref "U6") (pin "44") (pinfunction "44/P104_44") (pintype "bidirectional"))
      (node (ref "U8") (pin "44") (pinfunction "44/P104_44") (pintype "bidirectional"))
    )
    (net (code "31") (name "Net-(C5-1)") (class "Default")
      (node (ref "C5") (pin "P$1") (pinfunction "1_P$1") (pintype "passive"))
      (node (ref "U2") (pin "62") (pinfunction "VCL1_62") (pintype "bidirectional"))
    )
    (net (code "32") (name "Net-(C8-2)") (class "Default")
      (node (ref "C8") (pin "P$2") (pinfunction "2_P$2") (pintype "passive"))
      (node (ref "U2") (pin "148") (pinfunction "VCL2_148") (pintype "bidirectional"))
    )
    (net (code "33") (name "Net-(C9-1)") (class "Default")
      (node (ref "C9") (pin "P$1") (pinfunction "1_P$1") (pintype "passive"))
      (node (ref "U2") (pin "19") (pinfunction "VCLO_19") (pintype "bidirectional"))
    )
    (net (code "34") (name "Net-(LED2-A)") (class "Default")
      (node (ref "LED2") (pin "1") (pinfunction "A_1") (pintype "passive"))
      (node (ref "R12") (pin "P$1") (pinfunction "1_P$1") (pintype "passive"))
    )
    (net (code "35") (name "Net-(R1-2)") (class "Default")
      (node (ref "R1") (pin "P$2") (pinfunction "2_P$2") (pintype "passive"))
      (node (ref "U2") (pin "65") (pinfunction "VLO2(DCDC)_65") (pintype "bidirectional"))
    )
    (net (code "36") (name "Net-(R2-2)") (class "Default")
      (node (ref "R2") (pin "P$2") (pinfunction "2_P$2") (pintype "passive"))
      (node (ref "U2") (pin "64") (pinfunction "VLO1(DCDC)_64") (pintype "bidirectional"))
    )
    (net (code "37") (name "Net-(R4-2)") (class "Default")
      (node (ref "R4") (pin "P$2") (pinfunction "2_P$2") (pintype "passive"))
      (node (ref "U2") (pin "27") (pinfunction "USBHS_RREF_27") (pintype "bidirectional"))
    )
    (net (code "38") (name "P0_00") (class "Default")
      (node (ref "U2") (pin "169") (pinfunction "P0_0/AN0\\00_169") (pintype "bidirectional"))
    )
    (net (code "39") (name "P0_01") (class "Default")
      (node (ref "U2") (pin "168") (pinfunction "P0_1/AN001_168") (pintype "bidirectional"))
    )
    (net (code "40") (name "P0_02") (class "Default")
      (node (ref "U2") (pin "167") (pinfunction "P0_2/AN002_167") (pintype "bidirectional"))
    )
    (net (code "41") (name "P0_03") (class "Default")
      (node (ref "U2") (pin "166") (pinfunction "P0_3/PGAVSS000_166") (pintype "bidirectional"))
    )
    (net (code "42") (name "P0_04") (class "Default")
      (node (ref "U2") (pin "165") (pinfunction "P0_4/AN100_165") (pintype "bidirectional"))
    )
    (net (code "43") (name "P0_05") (class "Default")
      (node (ref "U2") (pin "164") (pinfunction "P0_5/AN101_164") (pintype "bidirectional"))
    )
    (net (code "44") (name "P0_06") (class "Default")
      (node (ref "U2") (pin "163") (pinfunction "P0_6/AN102_163") (pintype "bidirectional"))
    )
    (net (code "45") (name "P0_07") (class "Default")
      (node (ref "U2") (pin "162") (pinfunction "P0_7/PGVSS100_162") (pintype "bidirectional"))
    )
    (net (code "46") (name "P0_08") (class "Default")
      (node (ref "U2") (pin "161") (pinfunction "P0_8/AN003_161") (pintype "bidirectional"))
    )
    (net (code "47") (name "P0_09") (class "Default")
      (node (ref "U2") (pin "160") (pinfunction "P0_9/AN004_160") (pintype "bidirectional"))
    )
    (net (code "48") (name "P0_10") (class "Default")
      (node (ref "U2") (pin "159") (pinfunction "P0_10/AN103_159") (pintype "bidirectional"))
    )
    (net (code "49") (name "P0_14") (class "Default")
      (node (ref "U2") (pin "152") (pinfunction "P0_14/DA0/AN005/AN105_152") (pintype "bidirectional"))
    )
    (net (code "50") (name "P0_15") (class "Default")
      (node (ref "U2") (pin "151") (pinfunction "P0_15/DA1/AN006/AN106_151") (pintype "bidirectional"))
    )
    (net (code "51") (name "P1_11") (class "Default")
      (node (ref "U2") (pin "92") (pinfunction "P1_11_92") (pintype "bidirectional"))
    )
    (net (code "52") (name "P1_12") (class "Default")
      (node (ref "U2") (pin "93") (pinfunction "P1_12_93") (pintype "bidirectional"))
    )
    (net (code "53") (name "P1_13") (class "Default")
      (node (ref "U2") (pin "94") (pinfunction "P1_13_94") (pintype "bidirectional"))
    )
    (net (code "54") (name "P1_14") (class "Default")
      (node (ref "U2") (pin "95") (pinfunction "P1_14_95") (pintype "bidirectional"))
    )
    (net (code "55") (name "P1_15") (class "Default")
      (node (ref "U2") (pin "96") (pinfunction "P1_15_96") (pintype "bidirectional"))
    )
    (net (code "56") (name "P2_01") (class "Default")
      (node (ref "U2") (pin "68") (pinfunction "P2_1/MD_68") (pintype "bidirectional"))
    )
    (net (code "57") (name "P2_02") (class "Default")
      (node (ref "U2") (pin "54") (pinfunction "P2_2_54") (pintype "bidirectional"))
    )
    (net (code "58") (name "P2_03") (class "Default")
      (node (ref "U2") (pin "53") (pinfunction "P2_3_53") (pintype "bidirectional"))
    )
    (net (code "59") (name "P2_04") (class "Default")
      (node (ref "U2") (pin "52") (pinfunction "P2_4_52") (pintype "bidirectional"))
    )
    (net (code "60") (name "P2_05") (class "Default")
      (node (ref "U2") (pin "51") (pinfunction "P2_5_51") (pintype "bidirectional"))
    )
    (net (code "61") (name "P2_06") (class "Default")
      (node (ref "U2") (pin "50") (pinfunction "P2_6_50") (pintype "bidirectional"))
    )
    (net (code "62") (name "P2_07") (class "Default")
      (node (ref "U2") (pin "49") (pinfunction "P2_7_49") (pintype "bidirectional"))
    )
    (net (code "63") (name "P3_01") (class "Default")
      (node (ref "U2") (pin "87") (pinfunction "P3_1_87") (pintype "bidirectional"))
    )
    (net (code "64") (name "P3_02") (class "Default")
      (node (ref "U2") (pin "86") (pinfunction "P3_2_86") (pintype "bidirectional"))
    )
    (net (code "65") (name "P3_03") (class "Default")
      (node (ref "U2") (pin "85") (pinfunction "P3_3_85") (pintype "bidirectional"))
    )
    (net (code "66") (name "P3_06") (class "Default")
      (node (ref "U2") (pin "80") (pinfunction "P3_6_80") (pintype "bidirectional"))
    )
    (net (code "67") (name "P3_07") (class "Default")
      (node (ref "U2") (pin "79") (pinfunction "P3_7_79") (pintype "bidirectional"))
    )
    (net (code "68") (name "P3_08") (class "Default")
      (node (ref "U2") (pin "78") (pinfunction "P3_8_78") (pintype "bidirectional"))
    )
    (net (code "69") (name "P3_09") (class "Default")
      (node (ref "U2") (pin "77") (pinfunction "P3_9_77") (pintype "bidirectional"))
    )
    (net (code "70") (name "P3_10") (class "Default")
      (node (ref "U2") (pin "76") (pinfunction "P3_10_76") (pintype "bidirectional"))
    )
    (net (code "71") (name "P3_11") (class "Default")
      (node (ref "U2") (pin "75") (pinfunction "P3_11_75") (pintype "bidirectional"))
    )
    (net (code "72") (name "P3_12") (class "Default")
      (node (ref "U2") (pin "74") (pinfunction "P3_12_74") (pintype "bidirectional"))
    )
    (net (code "73") (name "P3_13") (class "Default")
      (node (ref "U2") (pin "55") (pinfunction "P3_13_55") (pintype "bidirectional"))
    )
    (net (code "74") (name "P3_14") (class "Default")
      (node (ref "U2") (pin "56") (pinfunction "P3_14_56") (pintype "bidirectional"))
    )
    (net (code "75") (name "P3_15") (class "Default")
      (node (ref "U2") (pin "57") (pinfunction "P3_15_57") (pintype "bidirectional"))
    )
    (net (code "76") (name "P4_00") (class "Default")
      (node (ref "U2") (pin "1") (pinfunction "P4_0_1") (pintype "bidirectional"))
    )
    (net (code "77") (name "P4_01") (class "Default")
      (node (ref "U2") (pin "2") (pinfunction "P4_1_2") (pintype "bidirectional"))
    )
    (net (code "78") (name "P4_02") (class "Default")
      (node (ref "U2") (pin "3") (pinfunction "P4_2_3") (pintype "bidirectional"))
    )
    (net (code "79") (name "P4_03") (class "Default")
      (node (ref "U2") (pin "4") (pinfunction "P4_3_4") (pintype "bidirectional"))
    )
    (net (code "80") (name "P4_04") (class "Default")
      (node (ref "U2") (pin "5") (pinfunction "P4_4_5") (pintype "bidirectional"))
    )
    (net (code "81") (name "P4_05") (class "Default")
      (node (ref "U2") (pin "6") (pinfunction "P4_5_6") (pintype "bidirectional"))
    )
    (net (code "82") (name "P4_06") (class "Default")
      (node (ref "U2") (pin "7") (pinfunction "P4_6_7") (pintype "bidirectional"))
    )
    (net (code "83") (name "P4_08") (class "Default")
      (node (ref "U2") (pin "43") (pinfunction "P4_8_43") (pintype "bidirectional"))
    )
    (net (code "84") (name "P4_09") (class "Default")
      (node (ref "U2") (pin "42") (pinfunction "P4_9_42") (pintype "bidirectional"))
    )
    (net (code "85") (name "P4_10") (class "Default")
      (node (ref "U2") (pin "41") (pinfunction "P4_10_41") (pintype "bidirectional"))
    )
    (net (code "86") (name "P4_11") (class "Default")
      (node (ref "U2") (pin "40") (pinfunction "P4_11_40") (pintype "bidirectional"))
    )
    (net (code "87") (name "P4_12") (class "Default")
      (node (ref "U2") (pin "39") (pinfunction "P4_12_39") (pintype "bidirectional"))
    )
    (net (code "88") (name "P4_13") (class "Default")
      (node (ref "U2") (pin "38") (pinfunction "P4_13_38") (pintype "bidirectional"))
    )
    (net (code "89") (name "P4_14") (class "Default")
      (node (ref "U2") (pin "37") (pinfunction "P4_14_37") (pintype "bidirectional"))
    )
    (net (code "90") (name "P4_15") (class "Default")
      (node (ref "U2") (pin "36") (pinfunction "P4_15_36") (pintype "bidirectional"))
    )
    (net (code "91") (name "P5_00") (class "Default")
      (node (ref "U2") (pin "140") (pinfunction "P5_0/AN016_140") (pintype "bidirectional"))
    )
    (net (code "92") (name "P5_01") (class "Default")
      (node (ref "U2") (pin "141") (pinfunction "P5_1/AN116_141") (pintype "bidirectional"))
    )
    (net (code "93") (name "P5_02") (class "Default")
      (node (ref "U2") (pin "142") (pinfunction "P5_2/AN017_142") (pintype "bidirectional"))
    )
    (net (code "94") (name "P5_03") (class "Default")
      (node (ref "U2") (pin "143") (pinfunction "P5_3/AN117_143") (pintype "bidirectional"))
    )
    (net (code "95") (name "P5_04") (class "Default")
      (node (ref "U2") (pin "144") (pinfunction "P5_4/AN018_144") (pintype "bidirectional"))
    )
    (net (code "96") (name "P5_05") (class "Default")
      (node (ref "U2") (pin "145") (pinfunction "P5_5/AN118_145") (pintype "bidirectional"))
    )
    (net (code "97") (name "P5_06") (class "Default")
      (node (ref "U2") (pin "146") (pinfunction "P5_6/AN019_146") (pintype "bidirectional"))
    )
    (net (code "98") (name "P5_07") (class "Default")
      (node (ref "U2") (pin "147") (pinfunction "P5_7/AN119_147") (pintype "bidirectional"))
    )
    (net (code "99") (name "P5_11") (class "Default")
      (node (ref "U2") (pin "176") (pinfunction "P5_11_176") (pintype "bidirectional"))
    )
    (net (code "100") (name "P5_12") (class "Default")
      (node (ref "U2") (pin "175") (pinfunction "P5_12_175") (pintype "bidirectional"))
    )
    (net (code "101") (name "P5_13") (class "Default")
      (node (ref "U2") (pin "174") (pinfunction "P5_13_174") (pintype "bidirectional"))
    )
    (net (code "102") (name "P6_01") (class "Default")
      (node (ref "U2") (pin "121") (pinfunction "P6_1_121") (pintype "bidirectional"))
    )
    (net (code "103") (name "P6_02") (class "Default")
      (node (ref "U2") (pin "120") (pinfunction "P6_2_120") (pintype "bidirectional"))
    )
    (net (code "104") (name "P6_03") (class "Default")
      (node (ref "U2") (pin "119") (pinfunction "P6_3_119") (pintype "bidirectional"))
    )
    (net (code "105") (name "P6_04") (class "Default")
      (node (ref "U2") (pin "118") (pinfunction "P6_4_118") (pintype "bidirectional"))
    )
    (net (code "106") (name "P6_05") (class "Default")
      (node (ref "U2") (pin "117") (pinfunction "P6_5_117") (pintype "bidirectional"))
    )
    (net (code "107") (name "P6_06") (class "Default")
      (node (ref "U2") (pin "116") (pinfunction "P6_6_116") (pintype "bidirectional"))
    )
    (net (code "108") (name "P6_07") (class "Default")
      (node (ref "U2") (pin "115") (pinfunction "P6_7_115") (pintype "bidirectional"))
    )
    (net (code "109") (name "P6_08") (class "Default")
      (node (ref "U2") (pin "99") (pinfunction "P6_8_99") (pintype "bidirectional"))
    )
    (net (code "110") (name "P6_09") (class "Default")
      (node (ref "U2") (pin "100") (pinfunction "P6_9_100") (pintype "bidirectional"))
    )
    (net (code "111") (name "P6_10") (class "Default")
      (node (ref "U2") (pin "101") (pinfunction "P6_10_101") (pintype "bidirectional"))
    )
    (net (code "112") (name "P6_11") (class "Default")
      (node (ref "U2") (pin "102") (pinfunction "P6_11_102") (pintype "bidirectional"))
    )
    (net (code "113") (name "P6_12") (class "Default")
      (node (ref "U2") (pin "103") (pinfunction "P6_12_103") (pintype "bidirectional"))
    )
    (net (code "114") (name "P6_13") (class "Default")
      (node (ref "U2") (pin "104") (pinfunction "P6_13_104") (pintype "bidirectional"))
    )
    (net (code "115") (name "P6_14") (class "Default")
      (node (ref "U2") (pin "105") (pinfunction "P6_14_105") (pintype "bidirectional"))
    )
    (net (code "116") (name "P6_15") (class "Default")
      (node (ref "U2") (pin "106") (pinfunction "P6_15_106") (pintype "bidirectional"))
    )
    (net (code "117") (name "P7_00") (class "Default")
      (node (ref "U2") (pin "8") (pinfunction "P7_0_8") (pintype "bidirectional"))
    )
    (net (code "118") (name "P7_01") (class "Default")
      (node (ref "U2") (pin "9") (pinfunction "P7_1_9") (pintype "bidirectional"))
    )
    (net (code "119") (name "P7_02") (class "Default")
      (node (ref "U2") (pin "10") (pinfunction "P7_2_10") (pintype "bidirectional"))
    )
    (net (code "120") (name "P7_03") (class "Default")
      (node (ref "U2") (pin "11") (pinfunction "P7_3_11") (pintype "bidirectional"))
    )
    (net (code "121") (name "P7_04") (class "Default")
      (node (ref "U2") (pin "12") (pinfunction "P7_4_12") (pintype "bidirectional"))
    )
    (net (code "122") (name "P7_05") (class "Default")
      (node (ref "U2") (pin "13") (pinfunction "P7_5_13") (pintype "bidirectional"))
    )
    (net (code "123") (name "P7_06") (class "Default")
      (node (ref "U2") (pin "14") (pinfunction "P7_6_14") (pintype "bidirectional"))
    )
    (net (code "124") (name "P7_07") (class "Default")
      (node (ref "U2") (pin "15") (pinfunction "P7_7_15") (pintype "bidirectional"))
    )
    (net (code "125") (name "P8_00") (class "Default")
      (node (ref "U2") (pin "133") (pinfunction "P8_0_133") (pintype "bidirectional"))
    )
    (net (code "126") (name "P8_01") (class "Default")
      (node (ref "U2") (pin "134") (pinfunction "P8_1_134") (pintype "bidirectional"))
    )
    (net (code "127") (name "P8_02") (class "Default")
      (node (ref "U2") (pin "135") (pinfunction "P8_2_135") (pintype "bidirectional"))
    )
    (net (code "128") (name "P8_03") (class "Default")
      (node (ref "U2") (pin "136") (pinfunction "P8_3_136") (pintype "bidirectional"))
    )
    (net (code "129") (name "P8_04") (class "Default")
      (node (ref "U2") (pin "137") (pinfunction "P8_4_137") (pintype "bidirectional"))
    )
    (net (code "130") (name "P8_05") (class "Default")
      (node (ref "U2") (pin "173") (pinfunction "P8_5_173") (pintype "bidirectional"))
    )
    (net (code "131") (name "P8_06") (class "Default")
      (node (ref "U2") (pin "172") (pinfunction "P8_6_172") (pintype "bidirectional"))
    )
    (net (code "132") (name "P9_00") (class "Default")
      (node (ref "U2") (pin "58") (pinfunction "P9_0_58") (pintype "bidirectional"))
    )
    (net (code "133") (name "P9_01") (class "Default")
      (node (ref "U2") (pin "59") (pinfunction "P9_1_59") (pintype "bidirectional"))
    )
    (net (code "134") (name "P9_05") (class "Default")
      (node (ref "U2") (pin "73") (pinfunction "P9_5_73") (pintype "bidirectional"))
    )
    (net (code "135") (name "P9_06") (class "Default")
      (node (ref "U2") (pin "72") (pinfunction "P9_6_72") (pintype "bidirectional"))
    )
    (net (code "136") (name "P9_07") (class "Default")
      (node (ref "U2") (pin "71") (pinfunction "P9_7_71") (pintype "bidirectional"))
    )
    (net (code "137") (name "P9_08") (class "Default")
      (node (ref "U2") (pin "70") (pinfunction "P9_8_70") (pintype "bidirectional"))
    )
    (net (code "138") (name "PA_00") (class "Default")
      (node (ref "U2") (pin "114") (pinfunction "PA_0_114") (pintype "bidirectional"))
    )
    (net (code "139") (name "PA_01") (class "Default")
      (node (ref "U2") (pin "113") (pinfunction "PA_1_113") (pintype "bidirectional"))
    )
    (net (code "140") (name "PA_08") (class "Default")
      (node (ref "U2") (pin "107") (pinfunction "PA_8_107") (pintype "bidirectional"))
    )
    (net (code "141") (name "PA_09") (class "Default")
      (node (ref "U2") (pin "108") (pinfunction "PA_9_108") (pintype "bidirectional"))
    )
    (net (code "142") (name "PA_10") (class "Default")
      (node (ref "U2") (pin "109") (pinfunction "PA_10_109") (pintype "bidirectional"))
    )
    (net (code "143") (name "PB_00") (class "Default")
      (node (ref "U2") (pin "16") (pinfunction "PB_0_16") (pintype "bidirectional"))
    )
    (net (code "144") (name "RELAY_1_A1") (class "Default")
      (node (ref "U1") (pin "24") (pinfunction "24/P204_24") (pintype "bidirectional"))
      (node (ref "U10") (pin "24") (pinfunction "24/P204_24") (pintype "bidirectional"))
      (node (ref "U12") (pin "24") (pinfunction "24/P204_24") (pintype "bidirectional"))
      (node (ref "U3") (pin "24") (pinfunction "24/P204_24") (pintype "bidirectional"))
      (node (ref "U6") (pin "24") (pinfunction "24/P204_24") (pintype "bidirectional"))
      (node (ref "U8") (pin "24") (pinfunction "24/P204_24") (pintype "bidirectional"))
    )
    (net (code "145") (name "RELAY_2_A1") (class "Default")
      (node (ref "U1") (pin "21") (pinfunction "21/P207_21") (pintype "power_in"))
      (node (ref "U10") (pin "21") (pinfunction "21/P207_21") (pintype "power_in"))
      (node (ref "U12") (pin "21") (pinfunction "21/P207_21") (pintype "power_in"))
      (node (ref "U3") (pin "21") (pinfunction "21/P207_21") (pintype "power_in"))
      (node (ref "U6") (pin "21") (pinfunction "21/P207_21") (pintype "power_in"))
      (node (ref "U8") (pin "21") (pinfunction "21/P207_21") (pintype "power_in"))
    )
    (net (code "146") (name "RELAY_3_A1") (class "Default")
      (node (ref "U1") (pin "22") (pinfunction "22/P206_22") (pintype "bidirectional"))
      (node (ref "U10") (pin "22") (pinfunction "22/P206_22") (pintype "bidirectional"))
      (node (ref "U12") (pin "22") (pinfunction "22/P206_22") (pintype "bidirectional"))
      (node (ref "U3") (pin "22") (pinfunction "22/P206_22") (pintype "bidirectional"))
      (node (ref "U6") (pin "22") (pinfunction "22/P206_22") (pintype "bidirectional"))
      (node (ref "U8") (pin "22") (pinfunction "22/P206_22") (pintype "bidirectional"))
    )
    (net (code "147") (name "RELAY_4_A1") (class "Default")
      (node (ref "U1") (pin "31") (pinfunction "31/P301_31") (pintype "bidirectional"))
      (node (ref "U10") (pin "31") (pinfunction "31/P301_31") (pintype "bidirectional"))
      (node (ref "U12") (pin "31") (pinfunction "31/P301_31") (pintype "bidirectional"))
      (node (ref "U3") (pin "31") (pinfunction "31/P301_31") (pintype "bidirectional"))
      (node (ref "U6") (pin "31") (pinfunction "31/P301_31") (pintype "bidirectional"))
      (node (ref "U8") (pin "31") (pinfunction "31/P301_31") (pintype "bidirectional"))
    )
    (net (code "148") (name "RESET") (class "Default")
      (node (ref "C26") (pin "P$1") (pinfunction "1_P$1") (pintype "passive"))
      (node (ref "J1") (pin "9") (pinfunction "9_9") (pintype "passive"))
      (node (ref "R3") (pin "P$1") (pinfunction "1_P$1") (pintype "passive"))
      (node (ref "U2") (pin "67") (pinfunction "RES#_67") (pintype "bidirectional"))
    )
    (net (code "149") (name "RESET_A1") (class "Default")
      (node (ref "C101") (pin "P$1") (pinfunction "1_P$1") (pintype "passive"))
      (node (ref "C131") (pin "P$1") (pinfunction "1_P$1") (pintype "passive"))
      (node (ref "C161") (pin "P$1") (pinfunction "1_P$1") (pintype "passive"))
      (node (ref "C191") (pin "P$1") (pinfunction "1_P$1") (pintype "passive"))
      (node (ref "C56") (pin "P$1") (pinfunction "1_P$1") (pintype "passive"))
      (node (ref "C71") (pin "P$1") (pinfunction "1_P$1") (pintype "passive"))
      (node (ref "J10") (pin "9") (pinfunction "9_9") (pintype "passive"))
      (node (ref "J15") (pin "9") (pinfunction "9_9") (pintype "passive"))
      (node (ref "J19") (pin "9") (pinfunction "9_9") (pintype "passive"))
      (node (ref "J23") (pin "9") (pinfunction "9_9") (pintype "passive"))
      (node (ref "J4") (pin "9") (pinfunction "9_9") (pintype "passive"))
      (node (ref "J6") (pin "9") (pinfunction "9_9") (pintype "passive"))
      (node (ref "R10") (pin "P$1") (pinfunction "1_P$1") (pintype "passive"))
      (node (ref "R13") (pin "P$1") (pinfunction "1_P$1") (pintype "passive"))
      (node (ref "R15") (pin "P$1") (pinfunction "1_P$1") (pintype "passive"))
      (node (ref "R5") (pin "P$1") (pinfunction "1_P$1") (pintype "passive"))
      (node (ref "R6") (pin "P$1") (pinfunction "1_P$1") (pintype "passive"))
      (node (ref "R8") (pin "P$1") (pinfunction "1_P$1") (pintype "passive"))
      (node (ref "U1") (pin "25") (pinfunction "25/RES_25") (pintype "input"))
      (node (ref "U10") (pin "25") (pinfunction "25/RES_25") (pintype "input"))
      (node (ref "U12") (pin "25") (pinfunction "25/RES_25") (pintype "input"))
      (node (ref "U3") (pin "25") (pinfunction "25/RES_25") (pintype "input"))
      (node (ref "U6") (pin "25") (pinfunction "25/RES_25") (pintype "input"))
      (node (ref "U8") (pin "25") (pinfunction "25/RES_25") (pintype "input"))
    )
    (net (code "150") (name "SCLK") (class "Default")
      (node (ref "J14") (pin "5") (pinfunction "5_5") (pintype "passive"))
      (node (ref "J14") (pin "6") (pinfunction "6_6") (pintype "passive"))
      (node (ref "J18") (pin "5") (pinfunction "5_5") (pintype "passive"))
      (node (ref "J18") (pin "6") (pinfunction "6_6") (pintype "passive"))
      (node (ref "J22") (pin "5") (pinfunction "5_5") (pintype "passive"))
      (node (ref "J22") (pin "6") (pinfunction "6_6") (pintype "passive"))
      (node (ref "J3") (pin "5") (pinfunction "5_5") (pintype "passive"))
      (node (ref "J3") (pin "6") (pinfunction "6_6") (pintype "passive"))
      (node (ref "J5") (pin "5") (pinfunction "5_5") (pintype "passive"))
      (node (ref "J5") (pin "6") (pinfunction "6_6") (pintype "passive"))
      (node (ref "J9") (pin "5") (pinfunction "5_5") (pintype "passive"))
      (node (ref "J9") (pin "6") (pinfunction "6_6") (pintype "passive"))
      (node (ref "U1") (pin "46") (pinfunction "46/P102_46") (pintype "bidirectional"))
      (node (ref "U10") (pin "46") (pinfunction "46/P102_46") (pintype "bidirectional"))
      (node (ref "U12") (pin "46") (pinfunction "46/P102_46") (pintype "bidirectional"))
      (node (ref "U2") (pin "130") (pinfunction "P1_2_130") (pintype "bidirectional"))
      (node (ref "U3") (pin "46") (pinfunction "46/P102_46") (pintype "bidirectional"))
      (node (ref "U6") (pin "46") (pinfunction "46/P102_46") (pintype "bidirectional"))
      (node (ref "U8") (pin "46") (pinfunction "46/P102_46") (pintype "bidirectional"))
    )
    (net (code "151") (name "SSL0_A1_01") (class "Default")
      (node (ref "J3") (pin "3") (pinfunction "3_3") (pintype "passive"))
      (node (ref "J3") (pin "4") (pinfunction "4_4") (pintype "passive"))
      (node (ref "U1") (pin "45") (pinfunction "45/P103_45") (pintype "bidirectional"))
      (node (ref "U2") (pin "129") (pinfunction "P1_3_129") (pintype "bidirectional"))
    )
    (net (code "152") (name "SSL0_A1_02") (class "Default")
      (node (ref "J5") (pin "3") (pinfunction "3_3") (pintype "passive"))
      (node (ref "J5") (pin "4") (pinfunction "4_4") (pintype "passive"))
      (node (ref "U2") (pin "128") (pinfunction "P1_4_128") (pintype "bidirectional"))
      (node (ref "U3") (pin "45") (pinfunction "45/P103_45") (pintype "bidirectional"))
    )
    (net (code "153") (name "SSL0_A1_03") (class "Default")
      (node (ref "J9") (pin "3") (pinfunction "3_3") (pintype "passive"))
      (node (ref "J9") (pin "4") (pinfunction "4_4") (pintype "passive"))
      (node (ref "U2") (pin "127") (pinfunction "P1_5_127") (pintype "bidirectional"))
      (node (ref "U6") (pin "45") (pinfunction "45/P103_45") (pintype "bidirectional"))
    )
    (net (code "154") (name "SSL0_A1_04") (class "Default")
      (node (ref "J14") (pin "3") (pinfunction "3_3") (pintype "passive"))
      (node (ref "J14") (pin "4") (pinfunction "4_4") (pintype "passive"))
      (node (ref "U2") (pin "126") (pinfunction "P1_6_126") (pintype "bidirectional"))
      (node (ref "U8") (pin "45") (pinfunction "45/P103_45") (pintype "bidirectional"))
    )
    (net (code "155") (name "SSL0_A1_05") (class "Default")
      (node (ref "J18") (pin "3") (pinfunction "3_3") (pintype "passive"))
      (node (ref "J18") (pin "4") (pinfunction "4_4") (pintype "passive"))
      (node (ref "U10") (pin "45") (pinfunction "45/P103_45") (pintype "bidirectional"))
      (node (ref "U2") (pin "125") (pinfunction "P1_7_125") (pintype "bidirectional"))
    )
    (net (code "156") (name "SSL0_A1_06") (class "Default")
      (node (ref "J22") (pin "3") (pinfunction "3_3") (pintype "passive"))
      (node (ref "J22") (pin "4") (pinfunction "4_4") (pintype "passive"))
      (node (ref "U12") (pin "45") (pinfunction "45/P103_45") (pintype "bidirectional"))
      (node (ref "U2") (pin "122") (pinfunction "P6_0_122") (pintype "bidirectional"))
    )
    (net (code "157") (name "STEP_M0A1") (class "Default")
      (node (ref "U1") (pin "16") (pinfunction "16/P407_16") (pintype "bidirectional"))
      (node (ref "U10") (pin "16") (pinfunction "16/P407_16") (pintype "bidirectional"))
      (node (ref "U12") (pin "16") (pinfunction "16/P407_16") (pintype "bidirectional"))
      (node (ref "U3") (pin "16") (pinfunction "16/P407_16") (pintype "bidirectional"))
      (node (ref "U6") (pin "16") (pinfunction "16/P407_16") (pintype "bidirectional"))
      (node (ref "U8") (pin "16") (pinfunction "16/P407_16") (pintype "bidirectional"))
    )
    (net (code "158") (name "STEP_M1A1") (class "Default")
      (node (ref "U1") (pin "12") (pinfunction "12/P411_12") (pintype "bidirectional"))
      (node (ref "U10") (pin "12") (pinfunction "12/P411_12") (pintype "bidirectional"))
      (node (ref "U12") (pin "12") (pinfunction "12/P411_12") (pintype "bidirectional"))
      (node (ref "U3") (pin "12") (pinfunction "12/P411_12") (pintype "bidirectional"))
      (node (ref "U6") (pin "12") (pinfunction "12/P411_12") (pintype "bidirectional"))
      (node (ref "U8") (pin "12") (pinfunction "12/P411_12") (pintype "bidirectional"))
    )
    (net (code "159") (name "TCK") (class "Default")
      (node (ref "J1") (pin "7") (pinfunction "7_7") (pintype "passive"))
      (node (ref "J10") (pin "7") (pinfunction "7_7") (pintype "passive"))
      (node (ref "J15") (pin "7") (pinfunction "7_7") (pintype "passive"))
      (node (ref "J19") (pin "7") (pinfunction "7_7") (pintype "passive"))
      (node (ref "J23") (pin "7") (pinfunction "7_7") (pintype "passive"))
      (node (ref "J4") (pin "7") (pinfunction "7_7") (pintype "passive"))
      (node (ref "J6") (pin "7") (pinfunction "7_7") (pintype "passive"))
      (node (ref "U1") (pin "32") (pinfunction "32/P300/TCK/SWCLK_32") (pintype "bidirectional"))
      (node (ref "U10") (pin "32") (pinfunction "32/P300/TCK/SWCLK_32") (pintype "bidirectional"))
      (node (ref "U12") (pin "32") (pinfunction "32/P300/TCK/SWCLK_32") (pintype "bidirectional"))
      (node (ref "U2") (pin "88") (pinfunction "P3_0_88") (pintype "bidirectional"))
      (node (ref "U3") (pin "32") (pinfunction "32/P300/TCK/SWCLK_32") (pintype "bidirectional"))
      (node (ref "U6") (pin "32") (pinfunction "32/P300/TCK/SWCLK_32") (pintype "bidirectional"))
      (node (ref "U8") (pin "32") (pinfunction "32/P300/TCK/SWCLK_32") (pintype "bidirectional"))
    )
    (net (code "160") (name "TDI") (class "Default")
      (node (ref "J1") (pin "1") (pinfunction "1_1") (pintype "passive"))
      (node (ref "J10") (pin "1") (pinfunction "1_1") (pintype "passive"))
      (node (ref "J15") (pin "1") (pinfunction "1_1") (pintype "passive"))
      (node (ref "J19") (pin "1") (pinfunction "1_1") (pintype "passive"))
      (node (ref "J23") (pin "1") (pinfunction "1_1") (pintype "passive"))
      (node (ref "J4") (pin "1") (pinfunction "1_1") (pintype "passive"))
      (node (ref "J6") (pin "1") (pinfunction "1_1") (pintype "passive"))
      (node (ref "U1") (pin "35") (pinfunction "35/P110/TDI_35") (pintype "bidirectional"))
      (node (ref "U10") (pin "35") (pinfunction "35/P110/TDI_35") (pintype "bidirectional"))
      (node (ref "U12") (pin "35") (pinfunction "35/P110/TDI_35") (pintype "bidirectional"))
      (node (ref "U2") (pin "91") (pinfunction "P1_10_91") (pintype "bidirectional"))
      (node (ref "U3") (pin "35") (pinfunction "35/P110/TDI_35") (pintype "bidirectional"))
      (node (ref "U6") (pin "35") (pinfunction "35/P110/TDI_35") (pintype "bidirectional"))
      (node (ref "U8") (pin "35") (pinfunction "35/P110/TDI_35") (pintype "bidirectional"))
    )
    (net (code "161") (name "TDO") (class "Default")
      (node (ref "J1") (pin "3") (pinfunction "3_3") (pintype "passive"))
      (node (ref "J10") (pin "3") (pinfunction "3_3") (pintype "passive"))
      (node (ref "J15") (pin "3") (pinfunction "3_3") (pintype "passive"))
      (node (ref "J19") (pin "3") (pinfunction "3_3") (pintype "passive"))
      (node (ref "J23") (pin "3") (pinfunction "3_3") (pintype "passive"))
      (node (ref "J4") (pin "3") (pinfunction "3_3") (pintype "passive"))
      (node (ref "J6") (pin "3") (pinfunction "3_3") (pintype "passive"))
      (node (ref "U1") (pin "34") (pinfunction "34/P109/TDO/SWO_34") (pintype "bidirectional"))
      (node (ref "U10") (pin "34") (pinfunction "34/P109/TDO/SWO_34") (pintype "bidirectional"))
      (node (ref "U12") (pin "34") (pinfunction "34/P109/TDO/SWO_34") (pintype "bidirectional"))
      (node (ref "U2") (pin "90") (pinfunction "P1_9_90") (pintype "bidirectional"))
      (node (ref "U3") (pin "34") (pinfunction "34/P109/TDO/SWO_34") (pintype "bidirectional"))
      (node (ref "U6") (pin "34") (pinfunction "34/P109/TDO/SWO_34") (pintype "bidirectional"))
      (node (ref "U8") (pin "34") (pinfunction "34/P109/TDO/SWO_34") (pintype "bidirectional"))
    )
    (net (code "162") (name "TMS") (class "Default")
      (node (ref "J1") (pin "5") (pinfunction "5_5") (pintype "passive"))
      (node (ref "J10") (pin "5") (pinfunction "5_5") (pintype "passive"))
      (node (ref "J15") (pin "5") (pinfunction "5_5") (pintype "passive"))
      (node (ref "J19") (pin "5") (pinfunction "5_5") (pintype "passive"))
      (node (ref "J23") (pin "5") (pinfunction "5_5") (pintype "passive"))
      (node (ref "J4") (pin "5") (pinfunction "5_5") (pintype "passive"))
      (node (ref "J6") (pin "5") (pinfunction "5_5") (pintype "passive"))
      (node (ref "U1") (pin "33") (pinfunction "33/P108/TMS/SWDIO_33") (pintype "bidirectional"))
      (node (ref "U10") (pin "33") (pinfunction "33/P108/TMS/SWDIO_33") (pintype "bidirectional"))
      (node (ref "U12") (pin "33") (pinfunction "33/P108/TMS/SWDIO_33") (pintype "bidirectional"))
      (node (ref "U2") (pin "89") (pinfunction "P1_8_89") (pintype "bidirectional"))
      (node (ref "U3") (pin "33") (pinfunction "33/P108/TMS/SWDIO_33") (pintype "bidirectional"))
      (node (ref "U6") (pin "33") (pinfunction "33/P108/TMS/SWDIO_33") (pintype "bidirectional"))
      (node (ref "U8") (pin "33") (pinfunction "33/P108/TMS/SWDIO_33") (pintype "bidirectional"))
    )
    (net (code "163") (name "USBHS_DN") (class "Default")
      (node (ref "U2") (pin "31") (pinfunction "USBHS_DM_31") (pintype "bidirectional"))
    )
    (net (code "164") (name "USBHS_DP") (class "Default")
      (node (ref "U2") (pin "32") (pinfunction "USBHS_DP_32") (pintype "bidirectional"))
    )
    (net (code "165") (name "USBHS_VBUS") (class "Default")
      (node (ref "U2") (pin "17") (pinfunction "PB_1_17") (pintype "bidirectional"))
    )
    (net (code "166") (name "USB_DN") (class "Default")
      (node (ref "U2") (pin "46") (pinfunction "USB_DM_46") (pintype "bidirectional"))
    )
    (net (code "167") (name "USB_DP") (class "Default")
      (node (ref "U2") (pin "47") (pinfunction "USB_DP_47") (pintype "bidirectional"))
    )
    (net (code "168") (name "USB_VBUS_B") (class "Default")
      (node (ref "U2") (pin "44") (pinfunction "P4_7_44") (pintype "bidirectional"))
    )
    (net (code "169") (name "VBATT_M1A1") (class "Default")
      (node (ref "U1") (pin "4") (pinfunction "4/VBATT_4") (pintype "power_in"))
      (node (ref "U10") (pin "4") (pinfunction "4/VBATT_4") (pintype "power_in"))
      (node (ref "U12") (pin "4") (pinfunction "4/VBATT_4") (pintype "power_in"))
      (node (ref "U3") (pin "4") (pinfunction "4/VBATT_4") (pintype "power_in"))
      (node (ref "U6") (pin "4") (pinfunction "4/VBATT_4") (pintype "power_in"))
      (node (ref "U8") (pin "4") (pinfunction "4/VBATT_4") (pintype "power_in"))
    )
    (net (code "170") (name "VCL0_A1") (class "Default")
      (node (ref "C125") (pin "P$2") (pinfunction "2_P$2") (pintype "passive"))
      (node (ref "C155") (pin "P$2") (pinfunction "2_P$2") (pintype "passive"))
      (node (ref "C185") (pin "P$2") (pinfunction "2_P$2") (pintype "passive"))
      (node (ref "C50") (pin "P$2") (pinfunction "2_P$2") (pintype "passive"))
      (node (ref "C65") (pin "P$2") (pinfunction "2_P$2") (pintype "passive"))
      (node (ref "C95") (pin "P$2") (pinfunction "2_P$2") (pintype "passive"))
      (node (ref "U1") (pin "5") (pinfunction "5/VCL0_5") (pintype "power_in"))
      (node (ref "U10") (pin "5") (pinfunction "5/VCL0_5") (pintype "power_in"))
      (node (ref "U12") (pin "5") (pinfunction "5/VCL0_5") (pintype "power_in"))
      (node (ref "U3") (pin "5") (pinfunction "5/VCL0_5") (pintype "power_in"))
      (node (ref "U6") (pin "5") (pinfunction "5/VCL0_5") (pintype "power_in"))
      (node (ref "U8") (pin "5") (pinfunction "5/VCL0_5") (pintype "power_in"))
    )
    (net (code "171") (name "VCL_F(FLASH)") (class "Default")
      (node (ref "C7") (pin "P$2") (pinfunction "2_P$2") (pintype "passive"))
      (node (ref "U2") (pin "112") (pinfunction "VCL_F(FLASH)_112") (pintype "bidirectional"))
    )
    (net (code "172") (name "VDD") (class "Default")
      (node (ref "C1") (pin "P$2") (pinfunction "2_P$2") (pintype "passive"))
      (node (ref "C100") (pin "P$1") (pinfunction "1_P$1") (pintype "passive"))
      (node (ref "C121") (pin "P$1") (pinfunction "1_P$1") (pintype "passive"))
      (node (ref "C122") (pin "P$1") (pinfunction "1_P$1") (pintype "passive"))
      (node (ref "C123") (pin "P$1") (pinfunction "1_P$1") (pintype "passive"))
      (node (ref "C124") (pin "P$1") (pinfunction "1_P$1") (pintype "passive"))
      (node (ref "C126") (pin "P$2") (pinfunction "2_P$2") (pintype "passive"))
      (node (ref "C127") (pin "P$1") (pinfunction "1_P$1") (pintype "passive"))
      (node (ref "C128") (pin "P$1") (pinfunction "1_P$1") (pintype "passive"))
      (node (ref "C129") (pin "P$1") (pinfunction "1_P$1") (pintype "passive"))
      (node (ref "C130") (pin "P$1") (pinfunction "1_P$1") (pintype "passive"))
      (node (ref "C14") (pin "P$2") (pinfunction "2_P$2") (pintype "passive"))
      (node (ref "C15") (pin "P$2") (pinfunction "2_P$2") (pintype "passive"))
      (node (ref "C151") (pin "P$1") (pinfunction "1_P$1") (pintype "passive"))
      (node (ref "C152") (pin "P$1") (pinfunction "1_P$1") (pintype "passive"))
      (node (ref "C153") (pin "P$1") (pinfunction "1_P$1") (pintype "passive"))
      (node (ref "C154") (pin "P$1") (pinfunction "1_P$1") (pintype "passive"))
      (node (ref "C156") (pin "P$2") (pinfunction "2_P$2") (pintype "passive"))
      (node (ref "C157") (pin "P$1") (pinfunction "1_P$1") (pintype "passive"))
      (node (ref "C158") (pin "P$1") (pinfunction "1_P$1") (pintype "passive"))
      (node (ref "C159") (pin "P$1") (pinfunction "1_P$1") (pintype "passive"))
      (node (ref "C160") (pin "P$1") (pinfunction "1_P$1") (pintype "passive"))
      (node (ref "C181") (pin "P$1") (pinfunction "1_P$1") (pintype "passive"))
      (node (ref "C182") (pin "P$1") (pinfunction "1_P$1") (pintype "passive"))
      (node (ref "C183") (pin "P$1") (pinfunction "1_P$1") (pintype "passive"))
      (node (ref "C184") (pin "P$1") (pinfunction "1_P$1") (pintype "passive"))
      (node (ref "C186") (pin "P$2") (pinfunction "2_P$2") (pintype "passive"))
      (node (ref "C187") (pin "P$1") (pinfunction "1_P$1") (pintype "passive"))
      (node (ref "C188") (pin "P$1") (pinfunction "1_P$1") (pintype "passive"))
      (node (ref "C189") (pin "P$1") (pinfunction "1_P$1") (pintype "passive"))
      (node (ref "C19") (pin "P$1") (pinfunction "1_P$1") (pintype "passive"))
      (node (ref "C190") (pin "P$1") (pinfunction "1_P$1") (pintype "passive"))
      (node (ref "C2") (pin "P$2") (pinfunction "2_P$2") (pintype "passive"))
      (node (ref "C20") (pin "P$1") (pinfunction "1_P$1") (pintype "passive"))
      (node (ref "C21") (pin "P$1") (pinfunction "1_P$1") (pintype "passive"))
      (node (ref "C23") (pin "P$2") (pinfunction "2_P$2") (pintype "passive"))
      (node (ref "C28") (pin "P$1") (pinfunction "1_P$1") (pintype "passive"))
      (node (ref "C29") (pin "P$1") (pinfunction "1_P$1") (pintype "passive"))
      (node (ref "C3") (pin "P$2") (pinfunction "2_P$2") (pintype "passive"))
      (node (ref "C31") (pin "P$1") (pinfunction "1_P$1") (pintype "passive"))
      (node (ref "C4") (pin "P$2") (pinfunction "2_P$2") (pintype "passive"))
      (node (ref "C43") (pin "P$1") (pinfunction "1_P$1") (pintype "passive"))
      (node (ref "C44") (pin "P$2") (pinfunction "2_P$2") (pintype "passive"))
      (node (ref "C45") (pin "P$2") (pinfunction "2_P$2") (pintype "passive"))
      (node (ref "C46") (pin "P$2") (pinfunction "2_P$2") (pintype "passive"))
      (node (ref "C47") (pin "P$1") (pinfunction "1_P$1") (pintype "passive"))
      (node (ref "C48") (pin "P$1") (pinfunction "1_P$1") (pintype "passive"))
      (node (ref "C49") (pin "P$1") (pinfunction "1_P$1") (pintype "passive"))
      (node (ref "C51") (pin "P$2") (pinfunction "2_P$2") (pintype "passive"))
      (node (ref "C52") (pin "P$1") (pinfunction "1_P$1") (pintype "passive"))
      (node (ref "C53") (pin "P$1") (pinfunction "1_P$1") (pintype "passive"))
      (node (ref "C54") (pin "P$1") (pinfunction "1_P$1") (pintype "passive"))
      (node (ref "C55") (pin "P$1") (pinfunction "1_P$1") (pintype "passive"))
      (node (ref "C6") (pin "P$1") (pinfunction "1_P$1") (pintype "passive"))
      (node (ref "C61") (pin "P$1") (pinfunction "1_P$1") (pintype "passive"))
      (node (ref "C62") (pin "P$1") (pinfunction "1_P$1") (pintype "passive"))
      (node (ref "C63") (pin "P$1") (pinfunction "1_P$1") (pintype "passive"))
      (node (ref "C64") (pin "P$1") (pinfunction "1_P$1") (pintype "passive"))
      (node (ref "C66") (pin "P$2") (pinfunction "2_P$2") (pintype "passive"))
      (node (ref "C67") (pin "P$1") (pinfunction "1_P$1") (pintype "passive"))
      (node (ref "C68") (pin "P$1") (pinfunction "1_P$1") (pintype "passive"))
      (node (ref "C69") (pin "P$1") (pinfunction "1_P$1") (pintype "passive"))
      (node (ref "C70") (pin "P$1") (pinfunction "1_P$1") (pintype "passive"))
      (node (ref "C91") (pin "P$1") (pinfunction "1_P$1") (pintype "passive"))
      (node (ref "C92") (pin "P$1") (pinfunction "1_P$1") (pintype "passive"))
      (node (ref "C93") (pin "P$1") (pinfunction "1_P$1") (pintype "passive"))
      (node (ref "C94") (pin "P$1") (pinfunction "1_P$1") (pintype "passive"))
      (node (ref "C96") (pin "P$2") (pinfunction "2_P$2") (pintype "passive"))
      (node (ref "C97") (pin "P$1") (pinfunction "1_P$1") (pintype "passive"))
      (node (ref "C98") (pin "P$1") (pinfunction "1_P$1") (pintype "passive"))
      (node (ref "C99") (pin "P$1") (pinfunction "1_P$1") (pintype "passive"))
      (node (ref "J1") (pin "2") (pinfunction "2_2") (pintype "passive"))
      (node (ref "J1") (pin "4") (pinfunction "4_4") (pintype "passive"))
      (node (ref "J10") (pin "2") (pinfunction "2_2") (pintype "passive"))
      (node (ref "J10") (pin "4") (pinfunction "4_4") (pintype "passive"))
      (node (ref "J15") (pin "2") (pinfunction "2_2") (pintype "passive"))
      (node (ref "J15") (pin "4") (pinfunction "4_4") (pintype "passive"))
      (node (ref "J19") (pin "2") (pinfunction "2_2") (pintype "passive"))
      (node (ref "J19") (pin "4") (pinfunction "4_4") (pintype "passive"))
      (node (ref "J23") (pin "2") (pinfunction "2_2") (pintype "passive"))
      (node (ref "J23") (pin "4") (pinfunction "4_4") (pintype "passive"))
      (node (ref "J4") (pin "2") (pinfunction "2_2") (pintype "passive"))
      (node (ref "J4") (pin "4") (pinfunction "4_4") (pintype "passive"))
      (node (ref "J6") (pin "2") (pinfunction "2_2") (pintype "passive"))
      (node (ref "J6") (pin "4") (pinfunction "4_4") (pintype "passive"))
      (node (ref "L2") (pin "2") (pinfunction "P$2_2") (pintype "bidirectional"))
      (node (ref "R10") (pin "P$2") (pinfunction "2_P$2") (pintype "passive"))
      (node (ref "R12") (pin "P$2") (pinfunction "2_P$2") (pintype "passive"))
      (node (ref "R13") (pin "P$2") (pinfunction "2_P$2") (pintype "passive"))
      (node (ref "R15") (pin "P$2") (pinfunction "2_P$2") (pintype "passive"))
      (node (ref "R3") (pin "P$2") (pinfunction "2_P$2") (pintype "passive"))
      (node (ref "R5") (pin "P$2") (pinfunction "2_P$2") (pintype "passive"))
      (node (ref "R6") (pin "P$2") (pinfunction "2_P$2") (pintype "passive"))
      (node (ref "R8") (pin "P$2") (pinfunction "2_P$2") (pintype "passive"))
      (node (ref "U1") (pin "11") (pinfunction "11/VCC_11") (pintype "power_in"))
      (node (ref "U1") (pin "20") (pinfunction "20/VCC_USB_20") (pintype "power_in"))
      (node (ref "U1") (pin "29") (pinfunction "29/VCC_29") (pintype "bidirectional"))
      (node (ref "U1") (pin "38") (pinfunction "38/VCC_38") (pintype "bidirectional"))
      (node (ref "U1") (pin "51") (pinfunction "51/VCC_51") (pintype "bidirectional"))
      (node (ref "U1") (pin "56") (pinfunction "56/VREFH_56") (pintype "power_in"))
      (node (ref "U1") (pin "57") (pinfunction "57/AVCC0_57") (pintype "power_in"))
      (node (ref "U1") (pin "60") (pinfunction "60/VREFH0_60") (pintype "bidirectional"))
      (node (ref "U10") (pin "11") (pinfunction "11/VCC_11") (pintype "power_in"))
      (node (ref "U10") (pin "20") (pinfunction "20/VCC_USB_20") (pintype "power_in"))
      (node (ref "U10") (pin "29") (pinfunction "29/VCC_29") (pintype "bidirectional"))
      (node (ref "U10") (pin "38") (pinfunction "38/VCC_38") (pintype "bidirectional"))
      (node (ref "U10") (pin "51") (pinfunction "51/VCC_51") (pintype "bidirectional"))
      (node (ref "U10") (pin "56") (pinfunction "56/VREFH_56") (pintype "power_in"))
      (node (ref "U10") (pin "57") (pinfunction "57/AVCC0_57") (pintype "power_in"))
      (node (ref "U10") (pin "60") (pinfunction "60/VREFH0_60") (pintype "bidirectional"))
      (node (ref "U12") (pin "11") (pinfunction "11/VCC_11") (pintype "power_in"))
      (node (ref "U12") (pin "20") (pinfunction "20/VCC_USB_20") (pintype "power_in"))
      (node (ref "U12") (pin "29") (pinfunction "29/VCC_29") (pintype "bidirectional"))
      (node (ref "U12") (pin "38") (pinfunction "38/VCC_38") (pintype "bidirectional"))
      (node (ref "U12") (pin "51") (pinfunction "51/VCC_51") (pintype "bidirectional"))
      (node (ref "U12") (pin "56") (pinfunction "56/VREFH_56") (pintype "power_in"))
      (node (ref "U12") (pin "57") (pinfunction "57/AVCC0_57") (pintype "power_in"))
      (node (ref "U12") (pin "60") (pinfunction "60/VREFH0_60") (pintype "bidirectional"))
      (node (ref "U2") (pin "110") (pinfunction "VCC(IO)5_110") (pintype "bidirectional"))
      (node (ref "U2") (pin "123") (pinfunction "VCC(IO)6_123") (pintype "bidirectional"))
      (node (ref "U2") (pin "138") (pinfunction "VCC(IO)7_138") (pintype "bidirectional"))
      (node (ref "U2") (pin "149") (pinfunction "VCC(IO)8_149") (pintype "bidirectional"))
      (node (ref "U2") (pin "154") (pinfunction "VREFH_154") (pintype "bidirectional"))
      (node (ref "U2") (pin "155") (pinfunction "AVCC0_155") (pintype "bidirectional"))
      (node (ref "U2") (pin "158") (pinfunction "VREFH0_158") (pintype "bidirectional"))
      (node (ref "U2") (pin "171") (pinfunction "VCC(IO)9_171") (pintype "bidirectional"))
      (node (ref "U2") (pin "25") (pinfunction "VCC1_25") (pintype "bidirectional"))
      (node (ref "U2") (pin "26") (pinfunction "AVCC_SUBHS_26") (pintype "bidirectional"))
      (node (ref "U2") (pin "34") (pinfunction "VCC_USBHS_34") (pintype "bidirectional"))
      (node (ref "U2") (pin "48") (pinfunction "VCC_USB_48") (pintype "bidirectional"))
      (node (ref "U2") (pin "61") (pinfunction "VCC(IO)2_61") (pintype "bidirectional"))
      (node (ref "U2") (pin "84") (pinfunction "VCC(IO)3_84") (pintype "bidirectional"))
      (node (ref "U2") (pin "97") (pinfunction "VCC(IO)4_97") (pintype "bidirectional"))
      (node (ref "U3") (pin "11") (pinfunction "11/VCC_11") (pintype "power_in"))
      (node (ref "U3") (pin "20") (pinfunction "20/VCC_USB_20") (pintype "power_in"))
      (node (ref "U3") (pin "29") (pinfunction "29/VCC_29") (pintype "bidirectional"))
      (node (ref "U3") (pin "38") (pinfunction "38/VCC_38") (pintype "bidirectional"))
      (node (ref "U3") (pin "51") (pinfunction "51/VCC_51") (pintype "bidirectional"))
      (node (ref "U3") (pin "56") (pinfunction "56/VREFH_56") (pintype "power_in"))
      (node (ref "U3") (pin "57") (pinfunction "57/AVCC0_57") (pintype "power_in"))
      (node (ref "U3") (pin "60") (pinfunction "60/VREFH0_60") (pintype "bidirectional"))
      (node (ref "U6") (pin "11") (pinfunction "11/VCC_11") (pintype "power_in"))
      (node (ref "U6") (pin "20") (pinfunction "20/VCC_USB_20") (pintype "power_in"))
      (node (ref "U6") (pin "29") (pinfunction "29/VCC_29") (pintype "bidirectional"))
      (node (ref "U6") (pin "38") (pinfunction "38/VCC_38") (pintype "bidirectional"))
      (node (ref "U6") (pin "51") (pinfunction "51/VCC_51") (pintype "bidirectional"))
      (node (ref "U6") (pin "56") (pinfunction "56/VREFH_56") (pintype "power_in"))
      (node (ref "U6") (pin "57") (pinfunction "57/AVCC0_57") (pintype "power_in"))
      (node (ref "U6") (pin "60") (pinfunction "60/VREFH0_60") (pintype "bidirectional"))
      (node (ref "U8") (pin "11") (pinfunction "11/VCC_11") (pintype "power_in"))
      (node (ref "U8") (pin "20") (pinfunction "20/VCC_USB_20") (pintype "power_in"))
      (node (ref "U8") (pin "29") (pinfunction "29/VCC_29") (pintype "bidirectional"))
      (node (ref "U8") (pin "38") (pinfunction "38/VCC_38") (pintype "bidirectional"))
      (node (ref "U8") (pin "51") (pinfunction "51/VCC_51") (pintype "bidirectional"))
      (node (ref "U8") (pin "56") (pinfunction "56/VREFH_56") (pintype "power_in"))
      (node (ref "U8") (pin "57") (pinfunction "57/AVCC0_57") (pintype "power_in"))
      (node (ref "U8") (pin "60") (pinfunction "60/VREFH0_60") (pintype "bidirectional"))
    )
    (net (code "173") (name "VDDIN") (class "Default")
      (node (ref "J13") (pin "P$2") (pinfunction "P$2_P$2") (pintype "bidirectional"))
      (node (ref "L2") (pin "1") (pinfunction "P$1_1") (pintype "bidirectional"))
    )
    (net (code "174") (name "XCIN") (class "Default")
      (node (ref "C10") (pin "P$1") (pinfunction "1_P$1") (pintype "passive"))
      (node (ref "U2") (pin "20") (pinfunction "XCIN_20") (pintype "bidirectional"))
      (node (ref "X3") (pin "P$1") (pinfunction "P$1_P$1") (pintype "bidirectional"))
    )
    (net (code "175") (name "XCIN_A1") (class "Default")
      (node (ref "C117") (pin "P$1") (pinfunction "1_P$1") (pintype "passive"))
      (node (ref "C147") (pin "P$1") (pinfunction "1_P$1") (pintype "passive"))
      (node (ref "C177") (pin "P$1") (pinfunction "1_P$1") (pintype "passive"))
      (node (ref "C39") (pin "P$1") (pinfunction "1_P$1") (pintype "passive"))
      (node (ref "C57") (pin "P$1") (pinfunction "1_P$1") (pintype "passive"))
      (node (ref "C87") (pin "P$1") (pinfunction "1_P$1") (pintype "passive"))
      (node (ref "U1") (pin "6") (pinfunction "6/XCIN_6") (pintype "bidirectional"))
      (node (ref "U10") (pin "6") (pinfunction "6/XCIN_6") (pintype "bidirectional"))
      (node (ref "U12") (pin "6") (pinfunction "6/XCIN_6") (pintype "bidirectional"))
      (node (ref "U3") (pin "6") (pinfunction "6/XCIN_6") (pintype "bidirectional"))
      (node (ref "U6") (pin "6") (pinfunction "6/XCIN_6") (pintype "bidirectional"))
      (node (ref "U8") (pin "6") (pinfunction "6/XCIN_6") (pintype "bidirectional"))
      (node (ref "X11") (pin "P$1") (pinfunction "P$1_P$1") (pintype "bidirectional"))
      (node (ref "X13") (pin "P$1") (pinfunction "P$1_P$1") (pintype "bidirectional"))
      (node (ref "X2") (pin "P$1") (pinfunction "P$1_P$1") (pintype "bidirectional"))
      (node (ref "X5") (pin "P$1") (pinfunction "P$1_P$1") (pintype "bidirectional"))
      (node (ref "X7") (pin "P$1") (pinfunction "P$1_P$1") (pintype "bidirectional"))
      (node (ref "X9") (pin "P$1") (pinfunction "P$1_P$1") (pintype "bidirectional"))
    )
    (net (code "176") (name "XCOUT") (class "Default")
      (node (ref "C11") (pin "P$1") (pinfunction "1_P$1") (pintype "passive"))
      (node (ref "U2") (pin "21") (pinfunction "XCOUT_21") (pintype "bidirectional"))
      (node (ref "X3") (pin "P$2") (pinfunction "P$2_P$2") (pintype "bidirectional"))
    )
    (net (code "177") (name "XCOUT_A1") (class "Default")
      (node (ref "C118") (pin "P$1") (pinfunction "1_P$1") (pintype "passive"))
      (node (ref "C148") (pin "P$1") (pinfunction "1_P$1") (pintype "passive"))
      (node (ref "C178") (pin "P$1") (pinfunction "1_P$1") (pintype "passive"))
      (node (ref "C40") (pin "P$1") (pinfunction "1_P$1") (pintype "passive"))
      (node (ref "C58") (pin "P$1") (pinfunction "1_P$1") (pintype "passive"))
      (node (ref "C88") (pin "P$1") (pinfunction "1_P$1") (pintype "passive"))
      (node (ref "U1") (pin "7") (pinfunction "7/XCOUT_7") (pintype "bidirectional"))
      (node (ref "U10") (pin "7") (pinfunction "7/XCOUT_7") (pintype "bidirectional"))
      (node (ref "U12") (pin "7") (pinfunction "7/XCOUT_7") (pintype "bidirectional"))
      (node (ref "U3") (pin "7") (pinfunction "7/XCOUT_7") (pintype "bidirectional"))
      (node (ref "U6") (pin "7") (pinfunction "7/XCOUT_7") (pintype "bidirectional"))
      (node (ref "U8") (pin "7") (pinfunction "7/XCOUT_7") (pintype "bidirectional"))
      (node (ref "X11") (pin "P$2") (pinfunction "P$2_P$2") (pintype "bidirectional"))
      (node (ref "X13") (pin "P$2") (pinfunction "P$2_P$2") (pintype "bidirectional"))
      (node (ref "X2") (pin "P$2") (pinfunction "P$2_P$2") (pintype "bidirectional"))
      (node (ref "X5") (pin "P$2") (pinfunction "P$2_P$2") (pintype "bidirectional"))
      (node (ref "X7") (pin "P$2") (pinfunction "P$2_P$2") (pintype "bidirectional"))
      (node (ref "X9") (pin "P$2") (pinfunction "P$2_P$2") (pintype "bidirectional"))
    )
    (net (code "178") (name "XTAL1") (class "Default")
      (node (ref "C12") (pin "P$1") (pinfunction "1_P$1") (pintype "passive"))
      (node (ref "U2") (pin "23") (pinfunction "P2_13/XTAL_23") (pintype "bidirectional"))
      (node (ref "X4") (pin "1") (pinfunction "1_1") (pintype "bidirectional"))
    )
    (net (code "179") (name "XTAL1_A1") (class "Default")
      (node (ref "C119") (pin "P$1") (pinfunction "1_P$1") (pintype "passive"))
      (node (ref "C149") (pin "P$1") (pinfunction "1_P$1") (pintype "passive"))
      (node (ref "C179") (pin "P$1") (pinfunction "1_P$1") (pintype "passive"))
      (node (ref "C41") (pin "P$1") (pinfunction "1_P$1") (pintype "passive"))
      (node (ref "C59") (pin "P$1") (pinfunction "1_P$1") (pintype "passive"))
      (node (ref "C89") (pin "P$1") (pinfunction "1_P$1") (pintype "passive"))
      (node (ref "U1") (pin "9") (pinfunction "9/XTAL_9") (pintype "bidirectional"))
      (node (ref "U10") (pin "9") (pinfunction "9/XTAL_9") (pintype "bidirectional"))
      (node (ref "U12") (pin "9") (pinfunction "9/XTAL_9") (pintype "bidirectional"))
      (node (ref "U3") (pin "9") (pinfunction "9/XTAL_9") (pintype "bidirectional"))
      (node (ref "U6") (pin "9") (pinfunction "9/XTAL_9") (pintype "bidirectional"))
      (node (ref "U8") (pin "9") (pinfunction "9/XTAL_9") (pintype "bidirectional"))
      (node (ref "Y1") (pin "3") (pinfunction "3_3") (pintype "passive"))
      (node (ref "Y11") (pin "3") (pinfunction "3_3") (pintype "passive"))
      (node (ref "Y3") (pin "3") (pinfunction "3_3") (pintype "passive"))
      (node (ref "Y5") (pin "3") (pinfunction "3_3") (pintype "passive"))
      (node (ref "Y7") (pin "3") (pinfunction "3_3") (pintype "passive"))
      (node (ref "Y9") (pin "3") (pinfunction "3_3") (pintype "passive"))
    )
    (net (code "180") (name "XTAL2") (class "Default")
      (node (ref "C13") (pin "P$1") (pinfunction "1_P$1") (pintype "passive"))
      (node (ref "U2") (pin "24") (pinfunction "P2_12/EXTAL_24") (pintype "bidirectional"))
      (node (ref "X4") (pin "3") (pinfunction "3_3") (pintype "bidirectional"))
    )
    (net (code "181") (name "XTAL2_A1") (class "Default")
      (node (ref "C120") (pin "P$1") (pinfunction "1_P$1") (pintype "passive"))
      (node (ref "C150") (pin "P$1") (pinfunction "1_P$1") (pintype "passive"))
      (node (ref "C180") (pin "P$1") (pinfunction "1_P$1") (pintype "passive"))
      (node (ref "C42") (pin "P$1") (pinfunction "1_P$1") (pintype "passive"))
      (node (ref "C60") (pin "P$1") (pinfunction "1_P$1") (pintype "passive"))
      (node (ref "C90") (pin "P$1") (pinfunction "1_P$1") (pintype "passive"))
      (node (ref "U1") (pin "10") (pinfunction "10/EXTAL_10") (pintype "bidirectional"))
      (node (ref "U10") (pin "10") (pinfunction "10/EXTAL_10") (pintype "bidirectional"))
      (node (ref "U12") (pin "10") (pinfunction "10/EXTAL_10") (pintype "bidirectional"))
      (node (ref "U3") (pin "10") (pinfunction "10/EXTAL_10") (pintype "bidirectional"))
      (node (ref "U6") (pin "10") (pinfunction "10/EXTAL_10") (pintype "bidirectional"))
      (node (ref "U8") (pin "10") (pinfunction "10/EXTAL_10") (pintype "bidirectional"))
      (node (ref "Y1") (pin "1") (pinfunction "1_1") (pintype "passive"))
      (node (ref "Y11") (pin "1") (pinfunction "1_1") (pintype "passive"))
      (node (ref "Y3") (pin "1") (pinfunction "1_1") (pintype "passive"))
      (node (ref "Y5") (pin "1") (pinfunction "1_1") (pintype "passive"))
      (node (ref "Y7") (pin "1") (pinfunction "1_1") (pintype "passive"))
      (node (ref "Y9") (pin "1") (pinfunction "1_1") (pintype "passive"))
    )
    (net (code "182") (name "unconnected-(U1-49{slash}P500-Pad49)") (class "Default")
      (node (ref "U1") (pin "49") (pinfunction "49/P500_49") (pintype "bidirectional"))
    )
    (net (code "183") (name "unconnected-(U1-52{slash}VSS-Pad52)") (class "Default")
      (node (ref "U1") (pin "52") (pinfunction "52/VSS_52") (pintype "bidirectional"))
    )
    (net (code "184") (name "unconnected-(U1-54{slash}P014-Pad54)") (class "Default")
      (node (ref "U1") (pin "54") (pinfunction "54/P014_54") (pintype "bidirectional"))
    )
    (net (code "185") (name "unconnected-(U1-61{slash}P003-Pad61)") (class "Default")
      (node (ref "U1") (pin "61") (pinfunction "61/P003_61") (pintype "bidirectional"))
    )
    (net (code "186") (name "unconnected-(U2-VBAT-Pad18)") (class "Default")
      (node (ref "U2") (pin "18") (pinfunction "VBAT_18") (pintype "bidirectional"))
    )
    (net (code "187") (name "unconnected-(U3-49{slash}P500-Pad49)") (class "Default")
      (node (ref "U3") (pin "49") (pinfunction "49/P500_49") (pintype "bidirectional"))
    )
    (net (code "188") (name "unconnected-(U3-52{slash}VSS-Pad52)") (class "Default")
      (node (ref "U3") (pin "52") (pinfunction "52/VSS_52") (pintype "bidirectional"))
    )
    (net (code "189") (name "unconnected-(U3-54{slash}P014-Pad54)") (class "Default")
      (node (ref "U3") (pin "54") (pinfunction "54/P014_54") (pintype "bidirectional"))
    )
    (net (code "190") (name "unconnected-(U3-61{slash}P003-Pad61)") (class "Default")
      (node (ref "U3") (pin "61") (pinfunction "61/P003_61") (pintype "bidirectional"))
    )
    (net (code "191") (name "unconnected-(U6-49{slash}P500-Pad49)") (class "Default")
      (node (ref "U6") (pin "49") (pinfunction "49/P500_49") (pintype "bidirectional"))
    )
    (net (code "192") (name "unconnected-(U6-52{slash}VSS-Pad52)") (class "Default")
      (node (ref "U6") (pin "52") (pinfunction "52/VSS_52") (pintype "bidirectional"))
    )
    (net (code "193") (name "unconnected-(U6-54{slash}P014-Pad54)") (class "Default")
      (node (ref "U6") (pin "54") (pinfunction "54/P014_54") (pintype "bidirectional"))
    )
    (net (code "194") (name "unconnected-(U6-61{slash}P003-Pad61)") (class "Default")
      (node (ref "U6") (pin "61") (pinfunction "61/P003_61") (pintype "bidirectional"))
    )
    (net (code "195") (name "unconnected-(U8-49{slash}P500-Pad49)") (class "Default")
      (node (ref "U8") (pin "49") (pinfunction "49/P500_49") (pintype "bidirectional"))
    )
    (net (code "196") (name "unconnected-(U8-52{slash}VSS-Pad52)") (class "Default")
      (node (ref "U8") (pin "52") (pinfunction "52/VSS_52") (pintype "bidirectional"))
    )
    (net (code "197") (name "unconnected-(U8-54{slash}P014-Pad54)") (class "Default")
      (node (ref "U8") (pin "54") (pinfunction "54/P014_54") (pintype "bidirectional"))
    )
    (net (code "198") (name "unconnected-(U8-61{slash}P003-Pad61)") (class "Default")
      (node (ref "U8") (pin "61") (pinfunction "61/P003_61") (pintype "bidirectional"))
    )
    (net (code "199") (name "unconnected-(U10-49{slash}P500-Pad49)") (class "Default")
      (node (ref "U10") (pin "49") (pinfunction "49/P500_49") (pintype "bidirectional"))
    )
    (net (code "200") (name "unconnected-(U10-52{slash}VSS-Pad52)") (class "Default")
      (node (ref "U10") (pin "52") (pinfunction "52/VSS_52") (pintype "bidirectional"))
    )
    (net (code "201") (name "unconnected-(U10-54{slash}P014-Pad54)") (class "Default")
      (node (ref "U10") (pin "54") (pinfunction "54/P014_54") (pintype "bidirectional"))
    )
    (net (code "202") (name "unconnected-(U10-61{slash}P003-Pad61)") (class "Default")
      (node (ref "U10") (pin "61") (pinfunction "61/P003_61") (pintype "bidirectional"))
    )
    (net (code "203") (name "unconnected-(U12-49{slash}P500-Pad49)") (class "Default")
      (node (ref "U12") (pin "49") (pinfunction "49/P500_49") (pintype "bidirectional"))
    )
    (net (code "204") (name "unconnected-(U12-52{slash}VSS-Pad52)") (class "Default")
      (node (ref "U12") (pin "52") (pinfunction "52/VSS_52") (pintype "bidirectional"))
    )
    (net (code "205") (name "unconnected-(U12-54{slash}P014-Pad54)") (class "Default")
      (node (ref "U12") (pin "54") (pinfunction "54/P014_54") (pintype "bidirectional"))
    )
    (net (code "206") (name "unconnected-(U12-61{slash}P003-Pad61)") (class "Default")
      (node (ref "U12") (pin "61") (pinfunction "61/P003_61") (pintype "bidirectional"))
    )
  )
)
